# button-wall.net
KiCad netlist of a schematic drawn in EAGLE
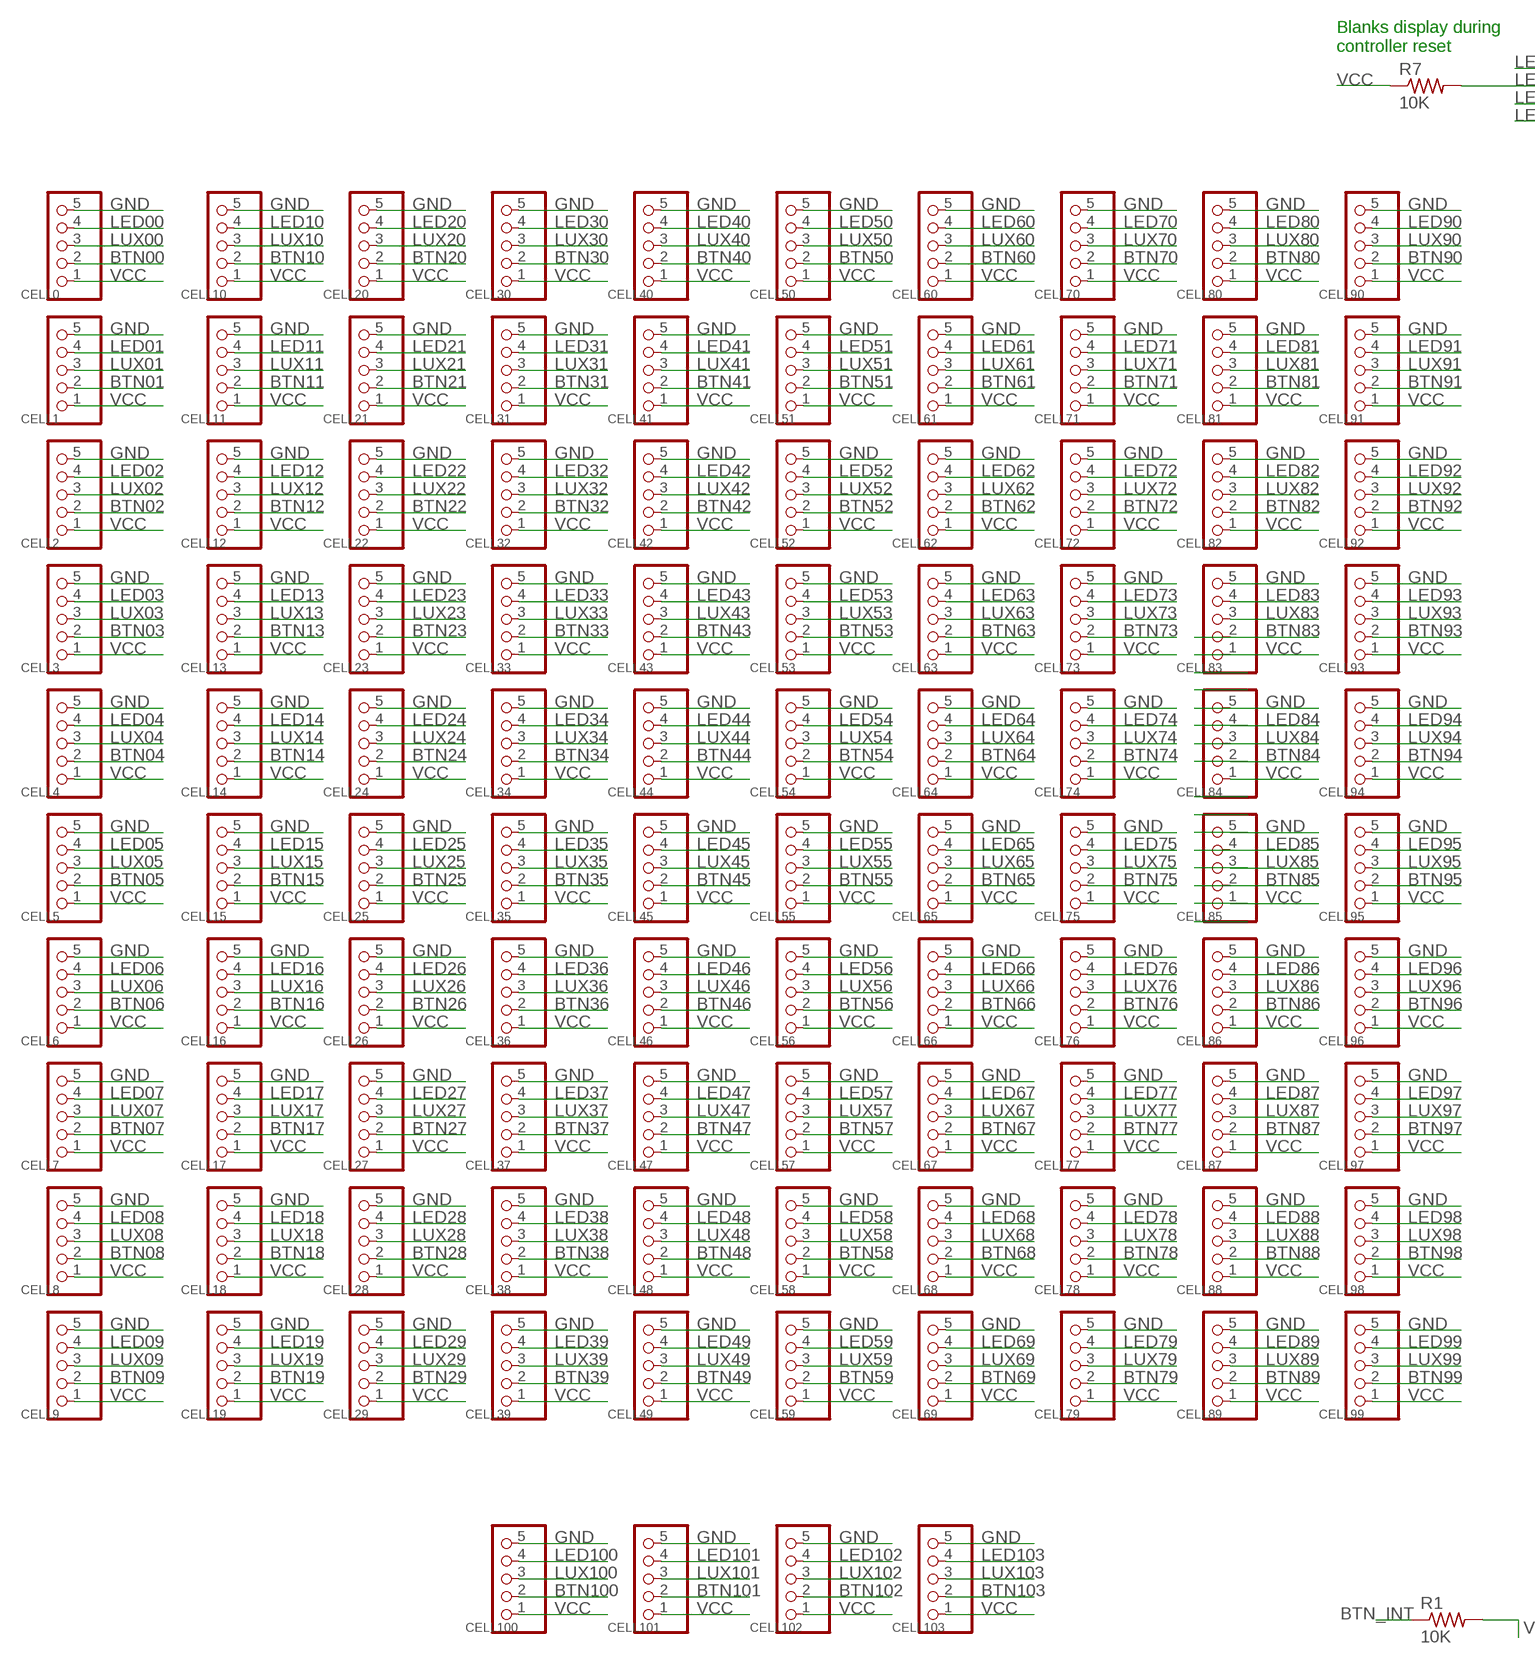
[diagram p0: schematic, sheet 1, part 1 of 2]
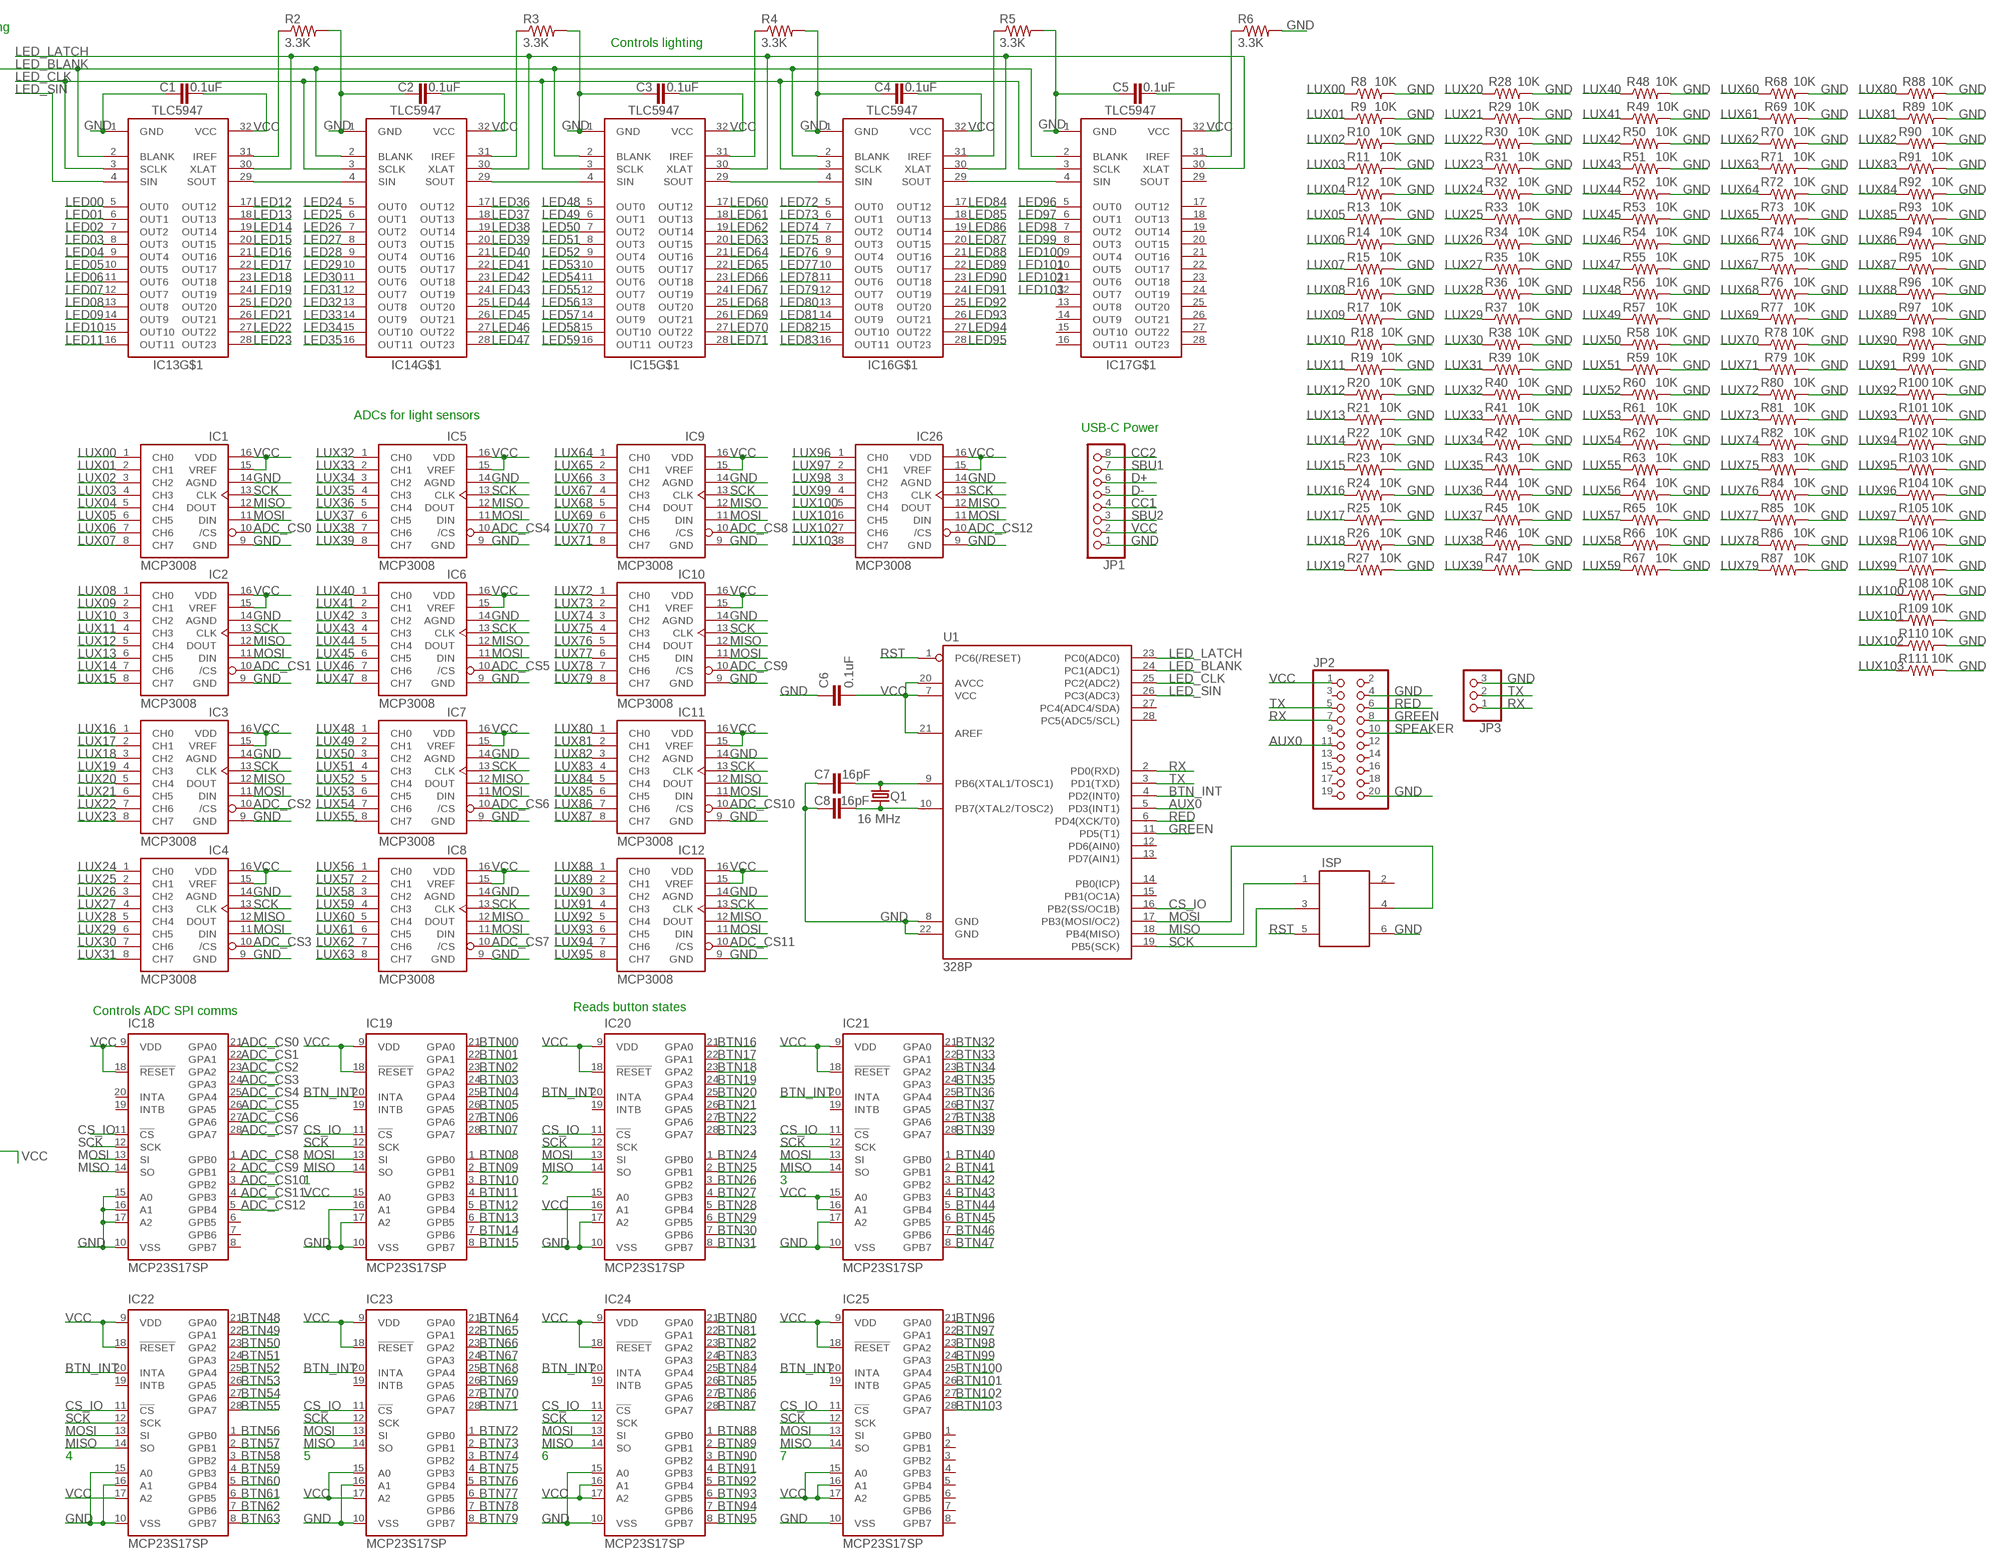
[diagram p1: schematic, sheet 1, part 2 of 2]

(export (version "E")
  (design (tool "Eeschema 10.0.6"))
  (components
    (comp (ref "C1")
      (value "0.1uF")
      (footprint "eagle-import:C1206")
      (libsource (lib "eagle-import") (part "C-EUC1206"))
    )
    (comp (ref "C2")
      (value "0.1uF")
      (footprint "eagle-import:C1206")
      (libsource (lib "eagle-import") (part "C-EUC1206"))
    )
    (comp (ref "C3")
      (value "0.1uF")
      (footprint "eagle-import:C1206")
      (libsource (lib "eagle-import") (part "C-EUC1206"))
    )
    (comp (ref "C4")
      (value "0.1uF")
      (footprint "eagle-import:C1206")
      (libsource (lib "eagle-import") (part "C-EUC1206"))
    )
    (comp (ref "C5")
      (value "0.1uF")
      (footprint "eagle-import:C1206")
      (libsource (lib "eagle-import") (part "C-EUC1206"))
    )
    (comp (ref "C6")
      (value "0.1uF")
      (footprint "eagle-import:C1206")
      (libsource (lib "eagle-import") (part "C-EUC1206"))
    )
    (comp (ref "C7")
      (value "16pF")
      (footprint "eagle-import:C0805")
      (libsource (lib "eagle-import") (part "C-EUC0805"))
    )
    (comp (ref "C8")
      (value "16pF")
      (footprint "eagle-import:C0805")
      (libsource (lib "eagle-import") (part "C-EUC0805"))
    )
    (comp (ref "CELL0")
      (value "PINHD-1X55X2MM")
      (footprint "eagle-import:1_05X2MM")
      (libsource (lib "eagle-import") (part "PINHD-1X55X2MM"))
    )
    (comp (ref "CELL1")
      (value "PINHD-1X55X2MM")
      (footprint "eagle-import:1_05X2MM")
      (libsource (lib "eagle-import") (part "PINHD-1X55X2MM"))
    )
    (comp (ref "CELL2")
      (value "PINHD-1X55X2MM")
      (footprint "eagle-import:1_05X2MM")
      (libsource (lib "eagle-import") (part "PINHD-1X55X2MM"))
    )
    (comp (ref "CELL3")
      (value "PINHD-1X55X2MM")
      (footprint "eagle-import:1_05X2MM")
      (libsource (lib "eagle-import") (part "PINHD-1X55X2MM"))
    )
    (comp (ref "CELL4")
      (value "PINHD-1X55X2MM")
      (footprint "eagle-import:1_05X2MM")
      (libsource (lib "eagle-import") (part "PINHD-1X55X2MM"))
    )
    (comp (ref "CELL5")
      (value "PINHD-1X55X2MM")
      (footprint "eagle-import:1_05X2MM")
      (libsource (lib "eagle-import") (part "PINHD-1X55X2MM"))
    )
    (comp (ref "CELL6")
      (value "PINHD-1X55X2MM")
      (footprint "eagle-import:1_05X2MM")
      (libsource (lib "eagle-import") (part "PINHD-1X55X2MM"))
    )
    (comp (ref "CELL7")
      (value "PINHD-1X55X2MM")
      (footprint "eagle-import:1_05X2MM")
      (libsource (lib "eagle-import") (part "PINHD-1X55X2MM"))
    )
    (comp (ref "CELL8")
      (value "PINHD-1X55X2MM")
      (footprint "eagle-import:1_05X2MM")
      (libsource (lib "eagle-import") (part "PINHD-1X55X2MM"))
    )
    (comp (ref "CELL9")
      (value "PINHD-1X55X2MM")
      (footprint "eagle-import:1_05X2MM")
      (libsource (lib "eagle-import") (part "PINHD-1X55X2MM"))
    )
    (comp (ref "CELL10")
      (value "PINHD-1X55X2MM")
      (footprint "eagle-import:1_05X2MM")
      (libsource (lib "eagle-import") (part "PINHD-1X55X2MM"))
    )
    (comp (ref "CELL11")
      (value "PINHD-1X55X2MM")
      (footprint "eagle-import:1_05X2MM")
      (libsource (lib "eagle-import") (part "PINHD-1X55X2MM"))
    )
    (comp (ref "CELL12")
      (value "PINHD-1X55X2MM")
      (footprint "eagle-import:1_05X2MM")
      (libsource (lib "eagle-import") (part "PINHD-1X55X2MM"))
    )
    (comp (ref "CELL13")
      (value "PINHD-1X55X2MM")
      (footprint "eagle-import:1_05X2MM")
      (libsource (lib "eagle-import") (part "PINHD-1X55X2MM"))
    )
    (comp (ref "CELL14")
      (value "PINHD-1X55X2MM")
      (footprint "eagle-import:1_05X2MM")
      (libsource (lib "eagle-import") (part "PINHD-1X55X2MM"))
    )
    (comp (ref "CELL15")
      (value "PINHD-1X55X2MM")
      (footprint "eagle-import:1_05X2MM")
      (libsource (lib "eagle-import") (part "PINHD-1X55X2MM"))
    )
    (comp (ref "CELL16")
      (value "PINHD-1X55X2MM")
      (footprint "eagle-import:1_05X2MM")
      (libsource (lib "eagle-import") (part "PINHD-1X55X2MM"))
    )
    (comp (ref "CELL17")
      (value "PINHD-1X55X2MM")
      (footprint "eagle-import:1_05X2MM")
      (libsource (lib "eagle-import") (part "PINHD-1X55X2MM"))
    )
    (comp (ref "CELL18")
      (value "PINHD-1X55X2MM")
      (footprint "eagle-import:1_05X2MM")
      (libsource (lib "eagle-import") (part "PINHD-1X55X2MM"))
    )
    (comp (ref "CELL19")
      (value "PINHD-1X55X2MM")
      (footprint "eagle-import:1_05X2MM")
      (libsource (lib "eagle-import") (part "PINHD-1X55X2MM"))
    )
    (comp (ref "CELL20")
      (value "PINHD-1X55X2MM")
      (footprint "eagle-import:1_05X2MM")
      (libsource (lib "eagle-import") (part "PINHD-1X55X2MM"))
    )
    (comp (ref "CELL21")
      (value "PINHD-1X55X2MM")
      (footprint "eagle-import:1_05X2MM")
      (libsource (lib "eagle-import") (part "PINHD-1X55X2MM"))
    )
    (comp (ref "CELL22")
      (value "PINHD-1X55X2MM")
      (footprint "eagle-import:1_05X2MM")
      (libsource (lib "eagle-import") (part "PINHD-1X55X2MM"))
    )
    (comp (ref "CELL23")
      (value "PINHD-1X55X2MM")
      (footprint "eagle-import:1_05X2MM")
      (libsource (lib "eagle-import") (part "PINHD-1X55X2MM"))
    )
    (comp (ref "CELL24")
      (value "PINHD-1X55X2MM")
      (footprint "eagle-import:1_05X2MM")
      (libsource (lib "eagle-import") (part "PINHD-1X55X2MM"))
    )
    (comp (ref "CELL25")
      (value "PINHD-1X55X2MM")
      (footprint "eagle-import:1_05X2MM")
      (libsource (lib "eagle-import") (part "PINHD-1X55X2MM"))
    )
    (comp (ref "CELL26")
      (value "PINHD-1X55X2MM")
      (footprint "eagle-import:1_05X2MM")
      (libsource (lib "eagle-import") (part "PINHD-1X55X2MM"))
    )
    (comp (ref "CELL27")
      (value "PINHD-1X55X2MM")
      (footprint "eagle-import:1_05X2MM")
      (libsource (lib "eagle-import") (part "PINHD-1X55X2MM"))
    )
    (comp (ref "CELL28")
      (value "PINHD-1X55X2MM")
      (footprint "eagle-import:1_05X2MM")
      (libsource (lib "eagle-import") (part "PINHD-1X55X2MM"))
    )
    (comp (ref "CELL29")
      (value "PINHD-1X55X2MM")
      (footprint "eagle-import:1_05X2MM")
      (libsource (lib "eagle-import") (part "PINHD-1X55X2MM"))
    )
    (comp (ref "CELL30")
      (value "PINHD-1X55X2MM")
      (footprint "eagle-import:1_05X2MM")
      (libsource (lib "eagle-import") (part "PINHD-1X55X2MM"))
    )
    (comp (ref "CELL31")
      (value "PINHD-1X55X2MM")
      (footprint "eagle-import:1_05X2MM")
      (libsource (lib "eagle-import") (part "PINHD-1X55X2MM"))
    )
    (comp (ref "CELL32")
      (value "PINHD-1X55X2MM")
      (footprint "eagle-import:1_05X2MM")
      (libsource (lib "eagle-import") (part "PINHD-1X55X2MM"))
    )
    (comp (ref "CELL33")
      (value "PINHD-1X55X2MM")
      (footprint "eagle-import:1_05X2MM")
      (libsource (lib "eagle-import") (part "PINHD-1X55X2MM"))
    )
    (comp (ref "CELL34")
      (value "PINHD-1X55X2MM")
      (footprint "eagle-import:1_05X2MM")
      (libsource (lib "eagle-import") (part "PINHD-1X55X2MM"))
    )
    (comp (ref "CELL35")
      (value "PINHD-1X55X2MM")
      (footprint "eagle-import:1_05X2MM")
      (libsource (lib "eagle-import") (part "PINHD-1X55X2MM"))
    )
    (comp (ref "CELL36")
      (value "PINHD-1X55X2MM")
      (footprint "eagle-import:1_05X2MM")
      (libsource (lib "eagle-import") (part "PINHD-1X55X2MM"))
    )
    (comp (ref "CELL37")
      (value "PINHD-1X55X2MM")
      (footprint "eagle-import:1_05X2MM")
      (libsource (lib "eagle-import") (part "PINHD-1X55X2MM"))
    )
    (comp (ref "CELL38")
      (value "PINHD-1X55X2MM")
      (footprint "eagle-import:1_05X2MM")
      (libsource (lib "eagle-import") (part "PINHD-1X55X2MM"))
    )
    (comp (ref "CELL39")
      (value "PINHD-1X55X2MM")
      (footprint "eagle-import:1_05X2MM")
      (libsource (lib "eagle-import") (part "PINHD-1X55X2MM"))
    )
    (comp (ref "CELL40")
      (value "PINHD-1X55X2MM")
      (footprint "eagle-import:1_05X2MM")
      (libsource (lib "eagle-import") (part "PINHD-1X55X2MM"))
    )
    (comp (ref "CELL41")
      (value "PINHD-1X55X2MM")
      (footprint "eagle-import:1_05X2MM")
      (libsource (lib "eagle-import") (part "PINHD-1X55X2MM"))
    )
    (comp (ref "CELL42")
      (value "PINHD-1X55X2MM")
      (footprint "eagle-import:1_05X2MM")
      (libsource (lib "eagle-import") (part "PINHD-1X55X2MM"))
    )
    (comp (ref "CELL43")
      (value "PINHD-1X55X2MM")
      (footprint "eagle-import:1_05X2MM")
      (libsource (lib "eagle-import") (part "PINHD-1X55X2MM"))
    )
    (comp (ref "CELL44")
      (value "PINHD-1X55X2MM")
      (footprint "eagle-import:1_05X2MM")
      (libsource (lib "eagle-import") (part "PINHD-1X55X2MM"))
    )
    (comp (ref "CELL45")
      (value "PINHD-1X55X2MM")
      (footprint "eagle-import:1_05X2MM")
      (libsource (lib "eagle-import") (part "PINHD-1X55X2MM"))
    )
    (comp (ref "CELL46")
      (value "PINHD-1X55X2MM")
      (footprint "eagle-import:1_05X2MM")
      (libsource (lib "eagle-import") (part "PINHD-1X55X2MM"))
    )
    (comp (ref "CELL47")
      (value "PINHD-1X55X2MM")
      (footprint "eagle-import:1_05X2MM")
      (libsource (lib "eagle-import") (part "PINHD-1X55X2MM"))
    )
    (comp (ref "CELL48")
      (value "PINHD-1X55X2MM")
      (footprint "eagle-import:1_05X2MM")
      (libsource (lib "eagle-import") (part "PINHD-1X55X2MM"))
    )
    (comp (ref "CELL49")
      (value "PINHD-1X55X2MM")
      (footprint "eagle-import:1_05X2MM")
      (libsource (lib "eagle-import") (part "PINHD-1X55X2MM"))
    )
    (comp (ref "CELL50")
      (value "PINHD-1X55X2MM")
      (footprint "eagle-import:1_05X2MM")
      (libsource (lib "eagle-import") (part "PINHD-1X55X2MM"))
    )
    (comp (ref "CELL51")
      (value "PINHD-1X55X2MM")
      (footprint "eagle-import:1_05X2MM")
      (libsource (lib "eagle-import") (part "PINHD-1X55X2MM"))
    )
    (comp (ref "CELL52")
      (value "PINHD-1X55X2MM")
      (footprint "eagle-import:1_05X2MM")
      (libsource (lib "eagle-import") (part "PINHD-1X55X2MM"))
    )
    (comp (ref "CELL53")
      (value "PINHD-1X55X2MM")
      (footprint "eagle-import:1_05X2MM")
      (libsource (lib "eagle-import") (part "PINHD-1X55X2MM"))
    )
    (comp (ref "CELL54")
      (value "PINHD-1X55X2MM")
      (footprint "eagle-import:1_05X2MM")
      (libsource (lib "eagle-import") (part "PINHD-1X55X2MM"))
    )
    (comp (ref "CELL55")
      (value "PINHD-1X55X2MM")
      (footprint "eagle-import:1_05X2MM")
      (libsource (lib "eagle-import") (part "PINHD-1X55X2MM"))
    )
    (comp (ref "CELL56")
      (value "PINHD-1X55X2MM")
      (footprint "eagle-import:1_05X2MM")
      (libsource (lib "eagle-import") (part "PINHD-1X55X2MM"))
    )
    (comp (ref "CELL57")
      (value "PINHD-1X55X2MM")
      (footprint "eagle-import:1_05X2MM")
      (libsource (lib "eagle-import") (part "PINHD-1X55X2MM"))
    )
    (comp (ref "CELL58")
      (value "PINHD-1X55X2MM")
      (footprint "eagle-import:1_05X2MM")
      (libsource (lib "eagle-import") (part "PINHD-1X55X2MM"))
    )
    (comp (ref "CELL59")
      (value "PINHD-1X55X2MM")
      (footprint "eagle-import:1_05X2MM")
      (libsource (lib "eagle-import") (part "PINHD-1X55X2MM"))
    )
    (comp (ref "CELL60")
      (value "PINHD-1X55X2MM")
      (footprint "eagle-import:1_05X2MM")
      (libsource (lib "eagle-import") (part "PINHD-1X55X2MM"))
    )
    (comp (ref "CELL61")
      (value "PINHD-1X55X2MM")
      (footprint "eagle-import:1_05X2MM")
      (libsource (lib "eagle-import") (part "PINHD-1X55X2MM"))
    )
    (comp (ref "CELL62")
      (value "PINHD-1X55X2MM")
      (footprint "eagle-import:1_05X2MM")
      (libsource (lib "eagle-import") (part "PINHD-1X55X2MM"))
    )
    (comp (ref "CELL63")
      (value "PINHD-1X55X2MM")
      (footprint "eagle-import:1_05X2MM")
      (libsource (lib "eagle-import") (part "PINHD-1X55X2MM"))
    )
    (comp (ref "CELL64")
      (value "PINHD-1X55X2MM")
      (footprint "eagle-import:1_05X2MM")
      (libsource (lib "eagle-import") (part "PINHD-1X55X2MM"))
    )
    (comp (ref "CELL65")
      (value "PINHD-1X55X2MM")
      (footprint "eagle-import:1_05X2MM")
      (libsource (lib "eagle-import") (part "PINHD-1X55X2MM"))
    )
    (comp (ref "CELL66")
      (value "PINHD-1X55X2MM")
      (footprint "eagle-import:1_05X2MM")
      (libsource (lib "eagle-import") (part "PINHD-1X55X2MM"))
    )
    (comp (ref "CELL67")
      (value "PINHD-1X55X2MM")
      (footprint "eagle-import:1_05X2MM")
      (libsource (lib "eagle-import") (part "PINHD-1X55X2MM"))
    )
    (comp (ref "CELL68")
      (value "PINHD-1X55X2MM")
      (footprint "eagle-import:1_05X2MM")
      (libsource (lib "eagle-import") (part "PINHD-1X55X2MM"))
    )
    (comp (ref "CELL69")
      (value "PINHD-1X55X2MM")
      (footprint "eagle-import:1_05X2MM")
      (libsource (lib "eagle-import") (part "PINHD-1X55X2MM"))
    )
    (comp (ref "CELL70")
      (value "PINHD-1X55X2MM")
      (footprint "eagle-import:1_05X2MM")
      (libsource (lib "eagle-import") (part "PINHD-1X55X2MM"))
    )
    (comp (ref "CELL71")
      (value "PINHD-1X55X2MM")
      (footprint "eagle-import:1_05X2MM")
      (libsource (lib "eagle-import") (part "PINHD-1X55X2MM"))
    )
    (comp (ref "CELL72")
      (value "PINHD-1X55X2MM")
      (footprint "eagle-import:1_05X2MM")
      (libsource (lib "eagle-import") (part "PINHD-1X55X2MM"))
    )
    (comp (ref "CELL73")
      (value "PINHD-1X55X2MM")
      (footprint "eagle-import:1_05X2MM")
      (libsource (lib "eagle-import") (part "PINHD-1X55X2MM"))
    )
    (comp (ref "CELL74")
      (value "PINHD-1X55X2MM")
      (footprint "eagle-import:1_05X2MM")
      (libsource (lib "eagle-import") (part "PINHD-1X55X2MM"))
    )
    (comp (ref "CELL75")
      (value "PINHD-1X55X2MM")
      (footprint "eagle-import:1_05X2MM")
      (libsource (lib "eagle-import") (part "PINHD-1X55X2MM"))
    )
    (comp (ref "CELL76")
      (value "PINHD-1X55X2MM")
      (footprint "eagle-import:1_05X2MM")
      (libsource (lib "eagle-import") (part "PINHD-1X55X2MM"))
    )
    (comp (ref "CELL77")
      (value "PINHD-1X55X2MM")
      (footprint "eagle-import:1_05X2MM")
      (libsource (lib "eagle-import") (part "PINHD-1X55X2MM"))
    )
    (comp (ref "CELL78")
      (value "PINHD-1X55X2MM")
      (footprint "eagle-import:1_05X2MM")
      (libsource (lib "eagle-import") (part "PINHD-1X55X2MM"))
    )
    (comp (ref "CELL79")
      (value "PINHD-1X55X2MM")
      (footprint "eagle-import:1_05X2MM")
      (libsource (lib "eagle-import") (part "PINHD-1X55X2MM"))
    )
    (comp (ref "CELL80")
      (value "PINHD-1X55X2MM")
      (footprint "eagle-import:1_05X2MM")
      (libsource (lib "eagle-import") (part "PINHD-1X55X2MM"))
    )
    (comp (ref "CELL81")
      (value "PINHD-1X55X2MM")
      (footprint "eagle-import:1_05X2MM")
      (libsource (lib "eagle-import") (part "PINHD-1X55X2MM"))
    )
    (comp (ref "CELL82")
      (value "PINHD-1X55X2MM")
      (footprint "eagle-import:1_05X2MM")
      (libsource (lib "eagle-import") (part "PINHD-1X55X2MM"))
    )
    (comp (ref "CELL83")
      (value "PINHD-1X55X2MM")
      (footprint "eagle-import:1_05X2MM")
      (libsource (lib "eagle-import") (part "PINHD-1X55X2MM"))
    )
    (comp (ref "CELL84")
      (value "PINHD-1X55X2MM")
      (footprint "eagle-import:1_05X2MM")
      (libsource (lib "eagle-import") (part "PINHD-1X55X2MM"))
    )
    (comp (ref "CELL85")
      (value "PINHD-1X55X2MM")
      (footprint "eagle-import:1_05X2MM")
      (libsource (lib "eagle-import") (part "PINHD-1X55X2MM"))
    )
    (comp (ref "CELL86")
      (value "PINHD-1X55X2MM")
      (footprint "eagle-import:1_05X2MM")
      (libsource (lib "eagle-import") (part "PINHD-1X55X2MM"))
    )
    (comp (ref "CELL87")
      (value "PINHD-1X55X2MM")
      (footprint "eagle-import:1_05X2MM")
      (libsource (lib "eagle-import") (part "PINHD-1X55X2MM"))
    )
    (comp (ref "CELL88")
      (value "PINHD-1X55X2MM")
      (footprint "eagle-import:1_05X2MM")
      (libsource (lib "eagle-import") (part "PINHD-1X55X2MM"))
    )
    (comp (ref "CELL89")
      (value "PINHD-1X55X2MM")
      (footprint "eagle-import:1_05X2MM")
      (libsource (lib "eagle-import") (part "PINHD-1X55X2MM"))
    )
    (comp (ref "CELL90")
      (value "PINHD-1X55X2MM")
      (footprint "eagle-import:1_05X2MM")
      (libsource (lib "eagle-import") (part "PINHD-1X55X2MM"))
    )
    (comp (ref "CELL91")
      (value "PINHD-1X55X2MM")
      (footprint "eagle-import:1_05X2MM")
      (libsource (lib "eagle-import") (part "PINHD-1X55X2MM"))
    )
    (comp (ref "CELL92")
      (value "PINHD-1X55X2MM")
      (footprint "eagle-import:1_05X2MM")
      (libsource (lib "eagle-import") (part "PINHD-1X55X2MM"))
    )
    (comp (ref "CELL93")
      (value "PINHD-1X55X2MM")
      (footprint "eagle-import:1_05X2MM")
      (libsource (lib "eagle-import") (part "PINHD-1X55X2MM"))
    )
    (comp (ref "CELL94")
      (value "PINHD-1X55X2MM")
      (footprint "eagle-import:1_05X2MM")
      (libsource (lib "eagle-import") (part "PINHD-1X55X2MM"))
    )
    (comp (ref "CELL95")
      (value "PINHD-1X55X2MM")
      (footprint "eagle-import:1_05X2MM")
      (libsource (lib "eagle-import") (part "PINHD-1X55X2MM"))
    )
    (comp (ref "CELL96")
      (value "PINHD-1X55X2MM")
      (footprint "eagle-import:1_05X2MM")
      (libsource (lib "eagle-import") (part "PINHD-1X55X2MM"))
    )
    (comp (ref "CELL97")
      (value "PINHD-1X55X2MM")
      (footprint "eagle-import:1_05X2MM")
      (libsource (lib "eagle-import") (part "PINHD-1X55X2MM"))
    )
    (comp (ref "CELL98")
      (value "PINHD-1X55X2MM")
      (footprint "eagle-import:1_05X2MM")
      (libsource (lib "eagle-import") (part "PINHD-1X55X2MM"))
    )
    (comp (ref "CELL99")
      (value "PINHD-1X55X2MM")
      (footprint "eagle-import:1_05X2MM")
      (libsource (lib "eagle-import") (part "PINHD-1X55X2MM"))
    )
    (comp (ref "CELL100")
      (value "PINHD-1X55X2MM")
      (footprint "eagle-import:1_05X2MM")
      (libsource (lib "eagle-import") (part "PINHD-1X55X2MM"))
    )
    (comp (ref "CELL101")
      (value "PINHD-1X55X2MM")
      (footprint "eagle-import:1_05X2MM")
      (libsource (lib "eagle-import") (part "PINHD-1X55X2MM"))
    )
    (comp (ref "CELL102")
      (value "PINHD-1X55X2MM")
      (footprint "eagle-import:1_05X2MM")
      (libsource (lib "eagle-import") (part "PINHD-1X55X2MM"))
    )
    (comp (ref "CELL103")
      (value "PINHD-1X55X2MM")
      (footprint "eagle-import:1_05X2MM")
      (libsource (lib "eagle-import") (part "PINHD-1X55X2MM"))
    )
    (comp (ref "IC1")
      (value "MCP3008")
      (footprint "eagle-import:DIL16")
      (libsource (lib "eagle-import") (part "MCP3008"))
    )
    (comp (ref "IC2")
      (value "MCP3008")
      (footprint "eagle-import:DIL16")
      (libsource (lib "eagle-import") (part "MCP3008"))
    )
    (comp (ref "IC3")
      (value "MCP3008")
      (footprint "eagle-import:DIL16")
      (libsource (lib "eagle-import") (part "MCP3008"))
    )
    (comp (ref "IC4")
      (value "MCP3008")
      (footprint "eagle-import:DIL16")
      (libsource (lib "eagle-import") (part "MCP3008"))
    )
    (comp (ref "IC5")
      (value "MCP3008")
      (footprint "eagle-import:DIL16")
      (libsource (lib "eagle-import") (part "MCP3008"))
    )
    (comp (ref "IC6")
      (value "MCP3008")
      (footprint "eagle-import:DIL16")
      (libsource (lib "eagle-import") (part "MCP3008"))
    )
    (comp (ref "IC7")
      (value "MCP3008")
      (footprint "eagle-import:DIL16")
      (libsource (lib "eagle-import") (part "MCP3008"))
    )
    (comp (ref "IC8")
      (value "MCP3008")
      (footprint "eagle-import:DIL16")
      (libsource (lib "eagle-import") (part "MCP3008"))
    )
    (comp (ref "IC9")
      (value "MCP3008")
      (footprint "eagle-import:DIL16")
      (libsource (lib "eagle-import") (part "MCP3008"))
    )
    (comp (ref "IC10")
      (value "MCP3008")
      (footprint "eagle-import:DIL16")
      (libsource (lib "eagle-import") (part "MCP3008"))
    )
    (comp (ref "IC11")
      (value "MCP3008")
      (footprint "eagle-import:DIL16")
      (libsource (lib "eagle-import") (part "MCP3008"))
    )
    (comp (ref "IC12")
      (value "MCP3008")
      (footprint "eagle-import:DIL16")
      (libsource (lib "eagle-import") (part "MCP3008"))
    )
    (comp (ref "IC13")
      (value "TLC5947-DAP")
      (footprint "eagle-import:HTSSOP32DAP")
      (libsource (lib "eagle-import") (part "TLC5947-DAP"))
    )
    (comp (ref "IC14")
      (value "TLC5947-DAP")
      (footprint "eagle-import:HTSSOP32DAP")
      (libsource (lib "eagle-import") (part "TLC5947-DAP"))
    )
    (comp (ref "IC15")
      (value "TLC5947-DAP")
      (footprint "eagle-import:HTSSOP32DAP")
      (libsource (lib "eagle-import") (part "TLC5947-DAP"))
    )
    (comp (ref "IC16")
      (value "TLC5947-DAP")
      (footprint "eagle-import:HTSSOP32DAP")
      (libsource (lib "eagle-import") (part "TLC5947-DAP"))
    )
    (comp (ref "IC17")
      (value "TLC5947-DAP")
      (footprint "eagle-import:HTSSOP32DAP")
      (libsource (lib "eagle-import") (part "TLC5947-DAP"))
    )
    (comp (ref "IC18")
      (value "MCP23S17SP")
      (footprint "eagle-import:DIL28-3")
      (fields (field (name "MF") "MICROCHIP") (field (name "MPN") "MCP23S17-E/SP"))
      (libsource (lib "eagle-import") (part "MCP23S17SP"))
    )
    (comp (ref "IC19")
      (value "MCP23S17SP")
      (footprint "eagle-import:DIL28-3")
      (fields (field (name "MF") "MICROCHIP") (field (name "MPN") "MCP23S17-E/SP"))
      (libsource (lib "eagle-import") (part "MCP23S17SP"))
    )
    (comp (ref "IC20")
      (value "MCP23S17SP")
      (footprint "eagle-import:DIL28-3")
      (fields (field (name "MF") "MICROCHIP") (field (name "MPN") "MCP23S17-E/SP"))
      (libsource (lib "eagle-import") (part "MCP23S17SP"))
    )
    (comp (ref "IC21")
      (value "MCP23S17SP")
      (footprint "eagle-import:DIL28-3")
      (fields (field (name "MF") "MICROCHIP") (field (name "MPN") "MCP23S17-E/SP"))
      (libsource (lib "eagle-import") (part "MCP23S17SP"))
    )
    (comp (ref "IC22")
      (value "MCP23S17SP")
      (footprint "eagle-import:DIL28-3")
      (fields (field (name "MF") "MICROCHIP") (field (name "MPN") "MCP23S17-E/SP"))
      (libsource (lib "eagle-import") (part "MCP23S17SP"))
    )
    (comp (ref "IC23")
      (value "MCP23S17SP")
      (footprint "eagle-import:DIL28-3")
      (fields (field (name "MF") "MICROCHIP") (field (name "MPN") "MCP23S17-E/SP"))
      (libsource (lib "eagle-import") (part "MCP23S17SP"))
    )
    (comp (ref "IC24")
      (value "MCP23S17SP")
      (footprint "eagle-import:DIL28-3")
      (fields (field (name "MF") "MICROCHIP") (field (name "MPN") "MCP23S17-E/SP"))
      (libsource (lib "eagle-import") (part "MCP23S17SP"))
    )
    (comp (ref "IC25")
      (value "MCP23S17SP")
      (footprint "eagle-import:DIL28-3")
      (fields (field (name "MF") "MICROCHIP") (field (name "MPN") "MCP23S17-E/SP"))
      (libsource (lib "eagle-import") (part "MCP23S17SP"))
    )
    (comp (ref "IC26")
      (value "MCP3008")
      (footprint "eagle-import:DIL16")
      (libsource (lib "eagle-import") (part "MCP3008"))
    )
    (comp (ref "ISP")
      (value "61200621621")
      (footprint "eagle-import:61200621621")
      (libsource (lib "eagle-import") (part "61200621621"))
    )
    (comp (ref "JP1")
      (value "PINHD-1X8CLEANBIG")
      (footprint "eagle-import:1X08-CLEANBIG")
      (libsource (lib "eagle-import") (part "PINHD-1X8CLEANBIG"))
    )
    (comp (ref "JP2")
      (value "PINHD-2X10")
      (footprint "eagle-import:2X10")
      (libsource (lib "eagle-import") (part "PINHD-2X10"))
    )
    (comp (ref "JP3")
      (value "PINHD-1X3")
      (footprint "eagle-import:1X03")
      (libsource (lib "eagle-import") (part "PINHD-1X3"))
    )
    (comp (ref "Q1")
      (value "16 MHz")
      (footprint "eagle-import:HC49_S")
      (libsource (lib "eagle-import") (part "CRYSTALHC49S"))
    )
    (comp (ref "R1")
      (value "10K")
      (footprint "eagle-import:R1206")
      (libsource (lib "eagle-import") (part "R-US_R1206"))
    )
    (comp (ref "R2")
      (value "3.3K")
      (footprint "eagle-import:R1206")
      (libsource (lib "eagle-import") (part "R-US_R1206"))
    )
    (comp (ref "R3")
      (value "3.3K")
      (footprint "eagle-import:R1206")
      (libsource (lib "eagle-import") (part "R-US_R1206"))
    )
    (comp (ref "R4")
      (value "3.3K")
      (footprint "eagle-import:R1206")
      (libsource (lib "eagle-import") (part "R-US_R1206"))
    )
    (comp (ref "R5")
      (value "3.3K")
      (footprint "eagle-import:R1206")
      (libsource (lib "eagle-import") (part "R-US_R1206"))
    )
    (comp (ref "R6")
      (value "3.3K")
      (footprint "eagle-import:R1206")
      (libsource (lib "eagle-import") (part "R-US_R1206"))
    )
    (comp (ref "R7")
      (value "10K")
      (footprint "eagle-import:R1206")
      (libsource (lib "eagle-import") (part "R-US_R1206"))
    )
    (comp (ref "R8")
      (value "10K")
      (footprint "eagle-import:R0805")
      (libsource (lib "eagle-import") (part "R-US_R0805"))
    )
    (comp (ref "R9")
      (value "10K")
      (footprint "eagle-import:R0805")
      (libsource (lib "eagle-import") (part "R-US_R0805"))
    )
    (comp (ref "R10")
      (value "10K")
      (footprint "eagle-import:R0805")
      (libsource (lib "eagle-import") (part "R-US_R0805"))
    )
    (comp (ref "R11")
      (value "10K")
      (footprint "eagle-import:R0805")
      (libsource (lib "eagle-import") (part "R-US_R0805"))
    )
    (comp (ref "R12")
      (value "10K")
      (footprint "eagle-import:R0805")
      (libsource (lib "eagle-import") (part "R-US_R0805"))
    )
    (comp (ref "R13")
      (value "10K")
      (footprint "eagle-import:R0805")
      (libsource (lib "eagle-import") (part "R-US_R0805"))
    )
    (comp (ref "R14")
      (value "10K")
      (footprint "eagle-import:R0805")
      (libsource (lib "eagle-import") (part "R-US_R0805"))
    )
    (comp (ref "R15")
      (value "10K")
      (footprint "eagle-import:R0805")
      (libsource (lib "eagle-import") (part "R-US_R0805"))
    )
    (comp (ref "R16")
      (value "10K")
      (footprint "eagle-import:R0805")
      (libsource (lib "eagle-import") (part "R-US_R0805"))
    )
    (comp (ref "R17")
      (value "10K")
      (footprint "eagle-import:R0805")
      (libsource (lib "eagle-import") (part "R-US_R0805"))
    )
    (comp (ref "R18")
      (value "10K")
      (footprint "eagle-import:R0805")
      (libsource (lib "eagle-import") (part "R-US_R0805"))
    )
    (comp (ref "R19")
      (value "10K")
      (footprint "eagle-import:R0805")
      (libsource (lib "eagle-import") (part "R-US_R0805"))
    )
    (comp (ref "R20")
      (value "10K")
      (footprint "eagle-import:R0805")
      (libsource (lib "eagle-import") (part "R-US_R0805"))
    )
    (comp (ref "R21")
      (value "10K")
      (footprint "eagle-import:R0805")
      (libsource (lib "eagle-import") (part "R-US_R0805"))
    )
    (comp (ref "R22")
      (value "10K")
      (footprint "eagle-import:R0805")
      (libsource (lib "eagle-import") (part "R-US_R0805"))
    )
    (comp (ref "R23")
      (value "10K")
      (footprint "eagle-import:R0805")
      (libsource (lib "eagle-import") (part "R-US_R0805"))
    )
    (comp (ref "R24")
      (value "10K")
      (footprint "eagle-import:R0805")
      (libsource (lib "eagle-import") (part "R-US_R0805"))
    )
    (comp (ref "R25")
      (value "10K")
      (footprint "eagle-import:R0805")
      (libsource (lib "eagle-import") (part "R-US_R0805"))
    )
    (comp (ref "R26")
      (value "10K")
      (footprint "eagle-import:R0805")
      (libsource (lib "eagle-import") (part "R-US_R0805"))
    )
    (comp (ref "R27")
      (value "10K")
      (footprint "eagle-import:R0805")
      (libsource (lib "eagle-import") (part "R-US_R0805"))
    )
    (comp (ref "R28")
      (value "10K")
      (footprint "eagle-import:R0805")
      (libsource (lib "eagle-import") (part "R-US_R0805"))
    )
    (comp (ref "R29")
      (value "10K")
      (footprint "eagle-import:R0805")
      (libsource (lib "eagle-import") (part "R-US_R0805"))
    )
    (comp (ref "R30")
      (value "10K")
      (footprint "eagle-import:R0805")
      (libsource (lib "eagle-import") (part "R-US_R0805"))
    )
    (comp (ref "R31")
      (value "10K")
      (footprint "eagle-import:R0805")
      (libsource (lib "eagle-import") (part "R-US_R0805"))
    )
    (comp (ref "R32")
      (value "10K")
      (footprint "eagle-import:R0805")
      (libsource (lib "eagle-import") (part "R-US_R0805"))
    )
    (comp (ref "R33")
      (value "10K")
      (footprint "eagle-import:R0805")
      (libsource (lib "eagle-import") (part "R-US_R0805"))
    )
    (comp (ref "R34")
      (value "10K")
      (footprint "eagle-import:R0805")
      (libsource (lib "eagle-import") (part "R-US_R0805"))
    )
    (comp (ref "R35")
      (value "10K")
      (footprint "eagle-import:R0805")
      (libsource (lib "eagle-import") (part "R-US_R0805"))
    )
    (comp (ref "R36")
      (value "10K")
      (footprint "eagle-import:R0805")
      (libsource (lib "eagle-import") (part "R-US_R0805"))
    )
    (comp (ref "R37")
      (value "10K")
      (footprint "eagle-import:R0805")
      (libsource (lib "eagle-import") (part "R-US_R0805"))
    )
    (comp (ref "R38")
      (value "10K")
      (footprint "eagle-import:R0805")
      (libsource (lib "eagle-import") (part "R-US_R0805"))
    )
    (comp (ref "R39")
      (value "10K")
      (footprint "eagle-import:R0805")
      (libsource (lib "eagle-import") (part "R-US_R0805"))
    )
    (comp (ref "R40")
      (value "10K")
      (footprint "eagle-import:R0805")
      (libsource (lib "eagle-import") (part "R-US_R0805"))
    )
    (comp (ref "R41")
      (value "10K")
      (footprint "eagle-import:R0805")
      (libsource (lib "eagle-import") (part "R-US_R0805"))
    )
    (comp (ref "R42")
      (value "10K")
      (footprint "eagle-import:R0805")
      (libsource (lib "eagle-import") (part "R-US_R0805"))
    )
    (comp (ref "R43")
      (value "10K")
      (footprint "eagle-import:R0805")
      (libsource (lib "eagle-import") (part "R-US_R0805"))
    )
    (comp (ref "R44")
      (value "10K")
      (footprint "eagle-import:R0805")
      (libsource (lib "eagle-import") (part "R-US_R0805"))
    )
    (comp (ref "R45")
      (value "10K")
      (footprint "eagle-import:R0805")
      (libsource (lib "eagle-import") (part "R-US_R0805"))
    )
    (comp (ref "R46")
      (value "10K")
      (footprint "eagle-import:R0805")
      (libsource (lib "eagle-import") (part "R-US_R0805"))
    )
    (comp (ref "R47")
      (value "10K")
      (footprint "eagle-import:R0805")
      (libsource (lib "eagle-import") (part "R-US_R0805"))
    )
    (comp (ref "R48")
      (value "10K")
      (footprint "eagle-import:R0805")
      (libsource (lib "eagle-import") (part "R-US_R0805"))
    )
    (comp (ref "R49")
      (value "10K")
      (footprint "eagle-import:R0805")
      (libsource (lib "eagle-import") (part "R-US_R0805"))
    )
    (comp (ref "R50")
      (value "10K")
      (footprint "eagle-import:R0805")
      (libsource (lib "eagle-import") (part "R-US_R0805"))
    )
    (comp (ref "R51")
      (value "10K")
      (footprint "eagle-import:R0805")
      (libsource (lib "eagle-import") (part "R-US_R0805"))
    )
    (comp (ref "R52")
      (value "10K")
      (footprint "eagle-import:R0805")
      (libsource (lib "eagle-import") (part "R-US_R0805"))
    )
    (comp (ref "R53")
      (value "10K")
      (footprint "eagle-import:R0805")
      (libsource (lib "eagle-import") (part "R-US_R0805"))
    )
    (comp (ref "R54")
      (value "10K")
      (footprint "eagle-import:R0805")
      (libsource (lib "eagle-import") (part "R-US_R0805"))
    )
    (comp (ref "R55")
      (value "10K")
      (footprint "eagle-import:R0805")
      (libsource (lib "eagle-import") (part "R-US_R0805"))
    )
    (comp (ref "R56")
      (value "10K")
      (footprint "eagle-import:R0805")
      (libsource (lib "eagle-import") (part "R-US_R0805"))
    )
    (comp (ref "R57")
      (value "10K")
      (footprint "eagle-import:R0805")
      (libsource (lib "eagle-import") (part "R-US_R0805"))
    )
    (comp (ref "R58")
      (value "10K")
      (footprint "eagle-import:R0805")
      (libsource (lib "eagle-import") (part "R-US_R0805"))
    )
    (comp (ref "R59")
      (value "10K")
      (footprint "eagle-import:R0805")
      (libsource (lib "eagle-import") (part "R-US_R0805"))
    )
    (comp (ref "R60")
      (value "10K")
      (footprint "eagle-import:R0805")
      (libsource (lib "eagle-import") (part "R-US_R0805"))
    )
    (comp (ref "R61")
      (value "10K")
      (footprint "eagle-import:R0805")
      (libsource (lib "eagle-import") (part "R-US_R0805"))
    )
    (comp (ref "R62")
      (value "10K")
      (footprint "eagle-import:R0805")
      (libsource (lib "eagle-import") (part "R-US_R0805"))
    )
    (comp (ref "R63")
      (value "10K")
      (footprint "eagle-import:R0805")
      (libsource (lib "eagle-import") (part "R-US_R0805"))
    )
    (comp (ref "R64")
      (value "10K")
      (footprint "eagle-import:R0805")
      (libsource (lib "eagle-import") (part "R-US_R0805"))
    )
    (comp (ref "R65")
      (value "10K")
      (footprint "eagle-import:R0805")
      (libsource (lib "eagle-import") (part "R-US_R0805"))
    )
    (comp (ref "R66")
      (value "10K")
      (footprint "eagle-import:R0805")
      (libsource (lib "eagle-import") (part "R-US_R0805"))
    )
    (comp (ref "R67")
      (value "10K")
      (footprint "eagle-import:R0805")
      (libsource (lib "eagle-import") (part "R-US_R0805"))
    )
    (comp (ref "R68")
      (value "10K")
      (footprint "eagle-import:R0805")
      (libsource (lib "eagle-import") (part "R-US_R0805"))
    )
    (comp (ref "R69")
      (value "10K")
      (footprint "eagle-import:R0805")
      (libsource (lib "eagle-import") (part "R-US_R0805"))
    )
    (comp (ref "R70")
      (value "10K")
      (footprint "eagle-import:R0805")
      (libsource (lib "eagle-import") (part "R-US_R0805"))
    )
    (comp (ref "R71")
      (value "10K")
      (footprint "eagle-import:R0805")
      (libsource (lib "eagle-import") (part "R-US_R0805"))
    )
    (comp (ref "R72")
      (value "10K")
      (footprint "eagle-import:R0805")
      (libsource (lib "eagle-import") (part "R-US_R0805"))
    )
    (comp (ref "R73")
      (value "10K")
      (footprint "eagle-import:R0805")
      (libsource (lib "eagle-import") (part "R-US_R0805"))
    )
    (comp (ref "R74")
      (value "10K")
      (footprint "eagle-import:R0805")
      (libsource (lib "eagle-import") (part "R-US_R0805"))
    )
    (comp (ref "R75")
      (value "10K")
      (footprint "eagle-import:R0805")
      (libsource (lib "eagle-import") (part "R-US_R0805"))
    )
    (comp (ref "R76")
      (value "10K")
      (footprint "eagle-import:R0805")
      (libsource (lib "eagle-import") (part "R-US_R0805"))
    )
    (comp (ref "R77")
      (value "10K")
      (footprint "eagle-import:R0805")
      (libsource (lib "eagle-import") (part "R-US_R0805"))
    )
    (comp (ref "R78")
      (value "10K")
      (footprint "eagle-import:R0805")
      (libsource (lib "eagle-import") (part "R-US_R0805"))
    )
    (comp (ref "R79")
      (value "10K")
      (footprint "eagle-import:R0805")
      (libsource (lib "eagle-import") (part "R-US_R0805"))
    )
    (comp (ref "R80")
      (value "10K")
      (footprint "eagle-import:R0805")
      (libsource (lib "eagle-import") (part "R-US_R0805"))
    )
    (comp (ref "R81")
      (value "10K")
      (footprint "eagle-import:R0805")
      (libsource (lib "eagle-import") (part "R-US_R0805"))
    )
    (comp (ref "R82")
      (value "10K")
      (footprint "eagle-import:R0805")
      (libsource (lib "eagle-import") (part "R-US_R0805"))
    )
    (comp (ref "R83")
      (value "10K")
      (footprint "eagle-import:R0805")
      (libsource (lib "eagle-import") (part "R-US_R0805"))
    )
    (comp (ref "R84")
      (value "10K")
      (footprint "eagle-import:R0805")
      (libsource (lib "eagle-import") (part "R-US_R0805"))
    )
    (comp (ref "R85")
      (value "10K")
      (footprint "eagle-import:R0805")
      (libsource (lib "eagle-import") (part "R-US_R0805"))
    )
    (comp (ref "R86")
      (value "10K")
      (footprint "eagle-import:R0805")
      (libsource (lib "eagle-import") (part "R-US_R0805"))
    )
    (comp (ref "R87")
      (value "10K")
      (footprint "eagle-import:R0805")
      (libsource (lib "eagle-import") (part "R-US_R0805"))
    )
    (comp (ref "R88")
      (value "10K")
      (footprint "eagle-import:R0805")
      (libsource (lib "eagle-import") (part "R-US_R0805"))
    )
    (comp (ref "R89")
      (value "10K")
      (footprint "eagle-import:R0805")
      (libsource (lib "eagle-import") (part "R-US_R0805"))
    )
    (comp (ref "R90")
      (value "10K")
      (footprint "eagle-import:R0805")
      (libsource (lib "eagle-import") (part "R-US_R0805"))
    )
    (comp (ref "R91")
      (value "10K")
      (footprint "eagle-import:R0805")
      (libsource (lib "eagle-import") (part "R-US_R0805"))
    )
    (comp (ref "R92")
      (value "10K")
      (footprint "eagle-import:R0805")
      (libsource (lib "eagle-import") (part "R-US_R0805"))
    )
    (comp (ref "R93")
      (value "10K")
      (footprint "eagle-import:R0805")
      (libsource (lib "eagle-import") (part "R-US_R0805"))
    )
    (comp (ref "R94")
      (value "10K")
      (footprint "eagle-import:R0805")
      (libsource (lib "eagle-import") (part "R-US_R0805"))
    )
    (comp (ref "R95")
      (value "10K")
      (footprint "eagle-import:R0805")
      (libsource (lib "eagle-import") (part "R-US_R0805"))
    )
    (comp (ref "R96")
      (value "10K")
      (footprint "eagle-import:R0805")
      (libsource (lib "eagle-import") (part "R-US_R0805"))
    )
    (comp (ref "R97")
      (value "10K")
      (footprint "eagle-import:R0805")
      (libsource (lib "eagle-import") (part "R-US_R0805"))
    )
    (comp (ref "R98")
      (value "10K")
      (footprint "eagle-import:R0805")
      (libsource (lib "eagle-import") (part "R-US_R0805"))
    )
    (comp (ref "R99")
      (value "10K")
      (footprint "eagle-import:R0805")
      (libsource (lib "eagle-import") (part "R-US_R0805"))
    )
    (comp (ref "R100")
      (value "10K")
      (footprint "eagle-import:R0805")
      (libsource (lib "eagle-import") (part "R-US_R0805"))
    )
    (comp (ref "R101")
      (value "10K")
      (footprint "eagle-import:R0805")
      (libsource (lib "eagle-import") (part "R-US_R0805"))
    )
    (comp (ref "R102")
      (value "10K")
      (footprint "eagle-import:R0805")
      (libsource (lib "eagle-import") (part "R-US_R0805"))
    )
    (comp (ref "R103")
      (value "10K")
      (footprint "eagle-import:R0805")
      (libsource (lib "eagle-import") (part "R-US_R0805"))
    )
    (comp (ref "R104")
      (value "10K")
      (footprint "eagle-import:R0805")
      (libsource (lib "eagle-import") (part "R-US_R0805"))
    )
    (comp (ref "R105")
      (value "10K")
      (footprint "eagle-import:R0805")
      (libsource (lib "eagle-import") (part "R-US_R0805"))
    )
    (comp (ref "R106")
      (value "10K")
      (footprint "eagle-import:R0805")
      (libsource (lib "eagle-import") (part "R-US_R0805"))
    )
    (comp (ref "R107")
      (value "10K")
      (footprint "eagle-import:R0805")
      (libsource (lib "eagle-import") (part "R-US_R0805"))
    )
    (comp (ref "R108")
      (value "10K")
      (footprint "eagle-import:R0805")
      (libsource (lib "eagle-import") (part "R-US_R0805"))
    )
    (comp (ref "R109")
      (value "10K")
      (footprint "eagle-import:R0805")
      (libsource (lib "eagle-import") (part "R-US_R0805"))
    )
    (comp (ref "R110")
      (value "10K")
      (footprint "eagle-import:R0805")
      (libsource (lib "eagle-import") (part "R-US_R0805"))
    )
    (comp (ref "R111")
      (value "10K")
      (footprint "eagle-import:R0805")
      (libsource (lib "eagle-import") (part "R-US_R0805"))
    )
    (comp (ref "U1")
      (value "328P")
      (footprint "eagle-import:DIP28")
      (libsource (lib "eagle-import") (part "ATMEGA328P_PDIP"))
    )
  )
  (nets
    (net (code "1") (name "/ADC_CS0") (class "Default")
      (node (ref "IC1") (pin "10") (pinfunction "/CS_10") (pintype "input"))
      (node (ref "IC18") (pin "21") (pinfunction "GPA0_21") (pintype "bidirectional"))
    )
    (net (code "2") (name "/ADC_CS1") (class "Default")
      (node (ref "IC18") (pin "22") (pinfunction "GPA1_22") (pintype "bidirectional"))
      (node (ref "IC2") (pin "10") (pinfunction "/CS_10") (pintype "input"))
    )
    (net (code "3") (name "/ADC_CS2") (class "Default")
      (node (ref "IC18") (pin "23") (pinfunction "GPA2_23") (pintype "bidirectional"))
      (node (ref "IC3") (pin "10") (pinfunction "/CS_10") (pintype "input"))
    )
    (net (code "4") (name "/ADC_CS3") (class "Default")
      (node (ref "IC18") (pin "24") (pinfunction "GPA3_24") (pintype "bidirectional"))
      (node (ref "IC4") (pin "10") (pinfunction "/CS_10") (pintype "input"))
    )
    (net (code "5") (name "/ADC_CS4") (class "Default")
      (node (ref "IC18") (pin "25") (pinfunction "GPA4_25") (pintype "bidirectional"))
      (node (ref "IC5") (pin "10") (pinfunction "/CS_10") (pintype "input"))
    )
    (net (code "6") (name "/ADC_CS5") (class "Default")
      (node (ref "IC18") (pin "26") (pinfunction "GPA5_26") (pintype "bidirectional"))
      (node (ref "IC6") (pin "10") (pinfunction "/CS_10") (pintype "input"))
    )
    (net (code "7") (name "/ADC_CS6") (class "Default")
      (node (ref "IC18") (pin "27") (pinfunction "GPA6_27") (pintype "bidirectional"))
      (node (ref "IC7") (pin "10") (pinfunction "/CS_10") (pintype "input"))
    )
    (net (code "8") (name "/ADC_CS7") (class "Default")
      (node (ref "IC18") (pin "28") (pinfunction "GPA7_28") (pintype "bidirectional"))
      (node (ref "IC8") (pin "10") (pinfunction "/CS_10") (pintype "input"))
    )
    (net (code "9") (name "/ADC_CS8") (class "Default")
      (node (ref "IC18") (pin "1") (pinfunction "GPB0_1") (pintype "bidirectional"))
      (node (ref "IC9") (pin "10") (pinfunction "/CS_10") (pintype "input"))
    )
    (net (code "10") (name "/ADC_CS9") (class "Default")
      (node (ref "IC10") (pin "10") (pinfunction "/CS_10") (pintype "input"))
      (node (ref "IC18") (pin "2") (pinfunction "GPB1_2") (pintype "bidirectional"))
    )
    (net (code "11") (name "/ADC_CS10") (class "Default")
      (node (ref "IC11") (pin "10") (pinfunction "/CS_10") (pintype "input"))
      (node (ref "IC18") (pin "3") (pinfunction "GPB2_3") (pintype "bidirectional"))
    )
    (net (code "12") (name "/ADC_CS11") (class "Default")
      (node (ref "IC12") (pin "10") (pinfunction "/CS_10") (pintype "input"))
      (node (ref "IC18") (pin "4") (pinfunction "GPB3_4") (pintype "bidirectional"))
    )
    (net (code "13") (name "/ADC_CS12") (class "Default")
      (node (ref "IC18") (pin "5") (pinfunction "GPB4_5") (pintype "bidirectional"))
      (node (ref "IC26") (pin "10") (pinfunction "/CS_10") (pintype "input"))
    )
    (net (code "14") (name "/AUX0") (class "Default")
      (node (ref "JP2") (pin "11") (pinfunction "11_11") (pintype "passive"))
      (node (ref "U1") (pin "5") (pinfunction "PD3(INT1)_5") (pintype "bidirectional"))
    )
    (net (code "15") (name "/BTN00") (class "Default")
      (node (ref "CELL0") (pin "2") (pinfunction "2_2") (pintype "passive"))
      (node (ref "IC19") (pin "21") (pinfunction "GPA0_21") (pintype "bidirectional"))
    )
    (net (code "16") (name "/BTN01") (class "Default")
      (node (ref "CELL1") (pin "2") (pinfunction "2_2") (pintype "passive"))
      (node (ref "IC19") (pin "22") (pinfunction "GPA1_22") (pintype "bidirectional"))
    )
    (net (code "17") (name "/BTN02") (class "Default")
      (node (ref "CELL2") (pin "2") (pinfunction "2_2") (pintype "passive"))
      (node (ref "IC19") (pin "23") (pinfunction "GPA2_23") (pintype "bidirectional"))
    )
    (net (code "18") (name "/BTN03") (class "Default")
      (node (ref "CELL3") (pin "2") (pinfunction "2_2") (pintype "passive"))
      (node (ref "IC19") (pin "24") (pinfunction "GPA3_24") (pintype "bidirectional"))
    )
    (net (code "19") (name "/BTN04") (class "Default")
      (node (ref "CELL4") (pin "2") (pinfunction "2_2") (pintype "passive"))
      (node (ref "IC19") (pin "25") (pinfunction "GPA4_25") (pintype "bidirectional"))
    )
    (net (code "20") (name "/BTN05") (class "Default")
      (node (ref "CELL5") (pin "2") (pinfunction "2_2") (pintype "passive"))
      (node (ref "IC19") (pin "26") (pinfunction "GPA5_26") (pintype "bidirectional"))
    )
    (net (code "21") (name "/BTN06") (class "Default")
      (node (ref "CELL6") (pin "2") (pinfunction "2_2") (pintype "passive"))
      (node (ref "IC19") (pin "27") (pinfunction "GPA6_27") (pintype "bidirectional"))
    )
    (net (code "22") (name "/BTN07") (class "Default")
      (node (ref "CELL7") (pin "2") (pinfunction "2_2") (pintype "passive"))
      (node (ref "IC19") (pin "28") (pinfunction "GPA7_28") (pintype "bidirectional"))
    )
    (net (code "23") (name "/BTN08") (class "Default")
      (node (ref "CELL8") (pin "2") (pinfunction "2_2") (pintype "passive"))
      (node (ref "IC19") (pin "1") (pinfunction "GPB0_1") (pintype "bidirectional"))
    )
    (net (code "24") (name "/BTN09") (class "Default")
      (node (ref "CELL9") (pin "2") (pinfunction "2_2") (pintype "passive"))
      (node (ref "IC19") (pin "2") (pinfunction "GPB1_2") (pintype "bidirectional"))
    )
    (net (code "25") (name "/BTN10") (class "Default")
      (node (ref "CELL10") (pin "2") (pinfunction "2_2") (pintype "passive"))
      (node (ref "IC19") (pin "3") (pinfunction "GPB2_3") (pintype "bidirectional"))
    )
    (net (code "26") (name "/BTN11") (class "Default")
      (node (ref "CELL11") (pin "2") (pinfunction "2_2") (pintype "passive"))
      (node (ref "IC19") (pin "4") (pinfunction "GPB3_4") (pintype "bidirectional"))
    )
    (net (code "27") (name "/BTN12") (class "Default")
      (node (ref "CELL12") (pin "2") (pinfunction "2_2") (pintype "passive"))
      (node (ref "IC19") (pin "5") (pinfunction "GPB4_5") (pintype "bidirectional"))
    )
    (net (code "28") (name "/BTN13") (class "Default")
      (node (ref "CELL13") (pin "2") (pinfunction "2_2") (pintype "passive"))
      (node (ref "IC19") (pin "6") (pinfunction "GPB5_6") (pintype "bidirectional"))
    )
    (net (code "29") (name "/BTN14") (class "Default")
      (node (ref "CELL14") (pin "2") (pinfunction "2_2") (pintype "passive"))
      (node (ref "IC19") (pin "7") (pinfunction "GPB6_7") (pintype "bidirectional"))
    )
    (net (code "30") (name "/BTN15") (class "Default")
      (node (ref "CELL15") (pin "2") (pinfunction "2_2") (pintype "passive"))
      (node (ref "IC19") (pin "8") (pinfunction "GPB7_8") (pintype "bidirectional"))
    )
    (net (code "31") (name "/BTN16") (class "Default")
      (node (ref "CELL16") (pin "2") (pinfunction "2_2") (pintype "passive"))
      (node (ref "IC20") (pin "21") (pinfunction "GPA0_21") (pintype "bidirectional"))
    )
    (net (code "32") (name "/BTN17") (class "Default")
      (node (ref "CELL17") (pin "2") (pinfunction "2_2") (pintype "passive"))
      (node (ref "IC20") (pin "22") (pinfunction "GPA1_22") (pintype "bidirectional"))
    )
    (net (code "33") (name "/BTN18") (class "Default")
      (node (ref "CELL18") (pin "2") (pinfunction "2_2") (pintype "passive"))
      (node (ref "IC20") (pin "23") (pinfunction "GPA2_23") (pintype "bidirectional"))
    )
    (net (code "34") (name "/BTN19") (class "Default")
      (node (ref "CELL19") (pin "2") (pinfunction "2_2") (pintype "passive"))
      (node (ref "IC20") (pin "24") (pinfunction "GPA3_24") (pintype "bidirectional"))
    )
    (net (code "35") (name "/BTN20") (class "Default")
      (node (ref "CELL20") (pin "2") (pinfunction "2_2") (pintype "passive"))
      (node (ref "IC20") (pin "25") (pinfunction "GPA4_25") (pintype "bidirectional"))
    )
    (net (code "36") (name "/BTN21") (class "Default")
      (node (ref "CELL21") (pin "2") (pinfunction "2_2") (pintype "passive"))
      (node (ref "IC20") (pin "26") (pinfunction "GPA5_26") (pintype "bidirectional"))
    )
    (net (code "37") (name "/BTN22") (class "Default")
      (node (ref "CELL22") (pin "2") (pinfunction "2_2") (pintype "passive"))
      (node (ref "IC20") (pin "27") (pinfunction "GPA6_27") (pintype "bidirectional"))
    )
    (net (code "38") (name "/BTN23") (class "Default")
      (node (ref "CELL23") (pin "2") (pinfunction "2_2") (pintype "passive"))
      (node (ref "IC20") (pin "28") (pinfunction "GPA7_28") (pintype "bidirectional"))
    )
    (net (code "39") (name "/BTN24") (class "Default")
      (node (ref "CELL24") (pin "2") (pinfunction "2_2") (pintype "passive"))
      (node (ref "IC20") (pin "1") (pinfunction "GPB0_1") (pintype "bidirectional"))
    )
    (net (code "40") (name "/BTN25") (class "Default")
      (node (ref "CELL25") (pin "2") (pinfunction "2_2") (pintype "passive"))
      (node (ref "IC20") (pin "2") (pinfunction "GPB1_2") (pintype "bidirectional"))
    )
    (net (code "41") (name "/BTN26") (class "Default")
      (node (ref "CELL26") (pin "2") (pinfunction "2_2") (pintype "passive"))
      (node (ref "IC20") (pin "3") (pinfunction "GPB2_3") (pintype "bidirectional"))
    )
    (net (code "42") (name "/BTN27") (class "Default")
      (node (ref "CELL27") (pin "2") (pinfunction "2_2") (pintype "passive"))
      (node (ref "IC20") (pin "4") (pinfunction "GPB3_4") (pintype "bidirectional"))
    )
    (net (code "43") (name "/BTN28") (class "Default")
      (node (ref "CELL28") (pin "2") (pinfunction "2_2") (pintype "passive"))
      (node (ref "IC20") (pin "5") (pinfunction "GPB4_5") (pintype "bidirectional"))
    )
    (net (code "44") (name "/BTN29") (class "Default")
      (node (ref "CELL29") (pin "2") (pinfunction "2_2") (pintype "passive"))
      (node (ref "IC20") (pin "6") (pinfunction "GPB5_6") (pintype "bidirectional"))
    )
    (net (code "45") (name "/BTN30") (class "Default")
      (node (ref "CELL30") (pin "2") (pinfunction "2_2") (pintype "passive"))
      (node (ref "IC20") (pin "7") (pinfunction "GPB6_7") (pintype "bidirectional"))
    )
    (net (code "46") (name "/BTN31") (class "Default")
      (node (ref "CELL31") (pin "2") (pinfunction "2_2") (pintype "passive"))
      (node (ref "IC20") (pin "8") (pinfunction "GPB7_8") (pintype "bidirectional"))
    )
    (net (code "47") (name "/BTN32") (class "Default")
      (node (ref "CELL32") (pin "2") (pinfunction "2_2") (pintype "passive"))
      (node (ref "IC21") (pin "21") (pinfunction "GPA0_21") (pintype "bidirectional"))
    )
    (net (code "48") (name "/BTN33") (class "Default")
      (node (ref "CELL33") (pin "2") (pinfunction "2_2") (pintype "passive"))
      (node (ref "IC21") (pin "22") (pinfunction "GPA1_22") (pintype "bidirectional"))
    )
    (net (code "49") (name "/BTN34") (class "Default")
      (node (ref "CELL34") (pin "2") (pinfunction "2_2") (pintype "passive"))
      (node (ref "IC21") (pin "23") (pinfunction "GPA2_23") (pintype "bidirectional"))
    )
    (net (code "50") (name "/BTN35") (class "Default")
      (node (ref "CELL35") (pin "2") (pinfunction "2_2") (pintype "passive"))
      (node (ref "IC21") (pin "24") (pinfunction "GPA3_24") (pintype "bidirectional"))
    )
    (net (code "51") (name "/BTN36") (class "Default")
      (node (ref "CELL36") (pin "2") (pinfunction "2_2") (pintype "passive"))
      (node (ref "IC21") (pin "25") (pinfunction "GPA4_25") (pintype "bidirectional"))
    )
    (net (code "52") (name "/BTN37") (class "Default")
      (node (ref "CELL37") (pin "2") (pinfunction "2_2") (pintype "passive"))
      (node (ref "IC21") (pin "26") (pinfunction "GPA5_26") (pintype "bidirectional"))
    )
    (net (code "53") (name "/BTN38") (class "Default")
      (node (ref "CELL38") (pin "2") (pinfunction "2_2") (pintype "passive"))
      (node (ref "IC21") (pin "27") (pinfunction "GPA6_27") (pintype "bidirectional"))
    )
    (net (code "54") (name "/BTN39") (class "Default")
      (node (ref "CELL39") (pin "2") (pinfunction "2_2") (pintype "passive"))
      (node (ref "IC21") (pin "28") (pinfunction "GPA7_28") (pintype "bidirectional"))
    )
    (net (code "55") (name "/BTN40") (class "Default")
      (node (ref "CELL40") (pin "2") (pinfunction "2_2") (pintype "passive"))
      (node (ref "IC21") (pin "1") (pinfunction "GPB0_1") (pintype "bidirectional"))
    )
    (net (code "56") (name "/BTN41") (class "Default")
      (node (ref "CELL41") (pin "2") (pinfunction "2_2") (pintype "passive"))
      (node (ref "IC21") (pin "2") (pinfunction "GPB1_2") (pintype "bidirectional"))
    )
    (net (code "57") (name "/BTN42") (class "Default")
      (node (ref "CELL42") (pin "2") (pinfunction "2_2") (pintype "passive"))
      (node (ref "IC21") (pin "3") (pinfunction "GPB2_3") (pintype "bidirectional"))
    )
    (net (code "58") (name "/BTN43") (class "Default")
      (node (ref "CELL43") (pin "2") (pinfunction "2_2") (pintype "passive"))
      (node (ref "IC21") (pin "4") (pinfunction "GPB3_4") (pintype "bidirectional"))
    )
    (net (code "59") (name "/BTN44") (class "Default")
      (node (ref "CELL44") (pin "2") (pinfunction "2_2") (pintype "passive"))
      (node (ref "IC21") (pin "5") (pinfunction "GPB4_5") (pintype "bidirectional"))
    )
    (net (code "60") (name "/BTN45") (class "Default")
      (node (ref "CELL45") (pin "2") (pinfunction "2_2") (pintype "passive"))
      (node (ref "IC21") (pin "6") (pinfunction "GPB5_6") (pintype "bidirectional"))
    )
    (net (code "61") (name "/BTN46") (class "Default")
      (node (ref "CELL46") (pin "2") (pinfunction "2_2") (pintype "passive"))
      (node (ref "IC21") (pin "7") (pinfunction "GPB6_7") (pintype "bidirectional"))
    )
    (net (code "62") (name "/BTN47") (class "Default")
      (node (ref "CELL47") (pin "2") (pinfunction "2_2") (pintype "passive"))
      (node (ref "IC21") (pin "8") (pinfunction "GPB7_8") (pintype "bidirectional"))
    )
    (net (code "63") (name "/BTN48") (class "Default")
      (node (ref "CELL48") (pin "2") (pinfunction "2_2") (pintype "passive"))
      (node (ref "IC22") (pin "21") (pinfunction "GPA0_21") (pintype "bidirectional"))
    )
    (net (code "64") (name "/BTN49") (class "Default")
      (node (ref "CELL49") (pin "2") (pinfunction "2_2") (pintype "passive"))
      (node (ref "IC22") (pin "22") (pinfunction "GPA1_22") (pintype "bidirectional"))
    )
    (net (code "65") (name "/BTN50") (class "Default")
      (node (ref "CELL50") (pin "2") (pinfunction "2_2") (pintype "passive"))
      (node (ref "IC22") (pin "23") (pinfunction "GPA2_23") (pintype "bidirectional"))
    )
    (net (code "66") (name "/BTN51") (class "Default")
      (node (ref "CELL51") (pin "2") (pinfunction "2_2") (pintype "passive"))
      (node (ref "IC22") (pin "24") (pinfunction "GPA3_24") (pintype "bidirectional"))
    )
    (net (code "67") (name "/BTN52") (class "Default")
      (node (ref "CELL52") (pin "2") (pinfunction "2_2") (pintype "passive"))
      (node (ref "IC22") (pin "25") (pinfunction "GPA4_25") (pintype "bidirectional"))
    )
    (net (code "68") (name "/BTN53") (class "Default")
      (node (ref "CELL53") (pin "2") (pinfunction "2_2") (pintype "passive"))
      (node (ref "IC22") (pin "26") (pinfunction "GPA5_26") (pintype "bidirectional"))
    )
    (net (code "69") (name "/BTN54") (class "Default")
      (node (ref "CELL54") (pin "2") (pinfunction "2_2") (pintype "passive"))
      (node (ref "IC22") (pin "27") (pinfunction "GPA6_27") (pintype "bidirectional"))
    )
    (net (code "70") (name "/BTN55") (class "Default")
      (node (ref "CELL55") (pin "2") (pinfunction "2_2") (pintype "passive"))
      (node (ref "IC22") (pin "28") (pinfunction "GPA7_28") (pintype "bidirectional"))
    )
    (net (code "71") (name "/BTN56") (class "Default")
      (node (ref "CELL56") (pin "2") (pinfunction "2_2") (pintype "passive"))
      (node (ref "IC22") (pin "1") (pinfunction "GPB0_1") (pintype "bidirectional"))
    )
    (net (code "72") (name "/BTN57") (class "Default")
      (node (ref "CELL57") (pin "2") (pinfunction "2_2") (pintype "passive"))
      (node (ref "IC22") (pin "2") (pinfunction "GPB1_2") (pintype "bidirectional"))
    )
    (net (code "73") (name "/BTN58") (class "Default")
      (node (ref "CELL58") (pin "2") (pinfunction "2_2") (pintype "passive"))
      (node (ref "IC22") (pin "3") (pinfunction "GPB2_3") (pintype "bidirectional"))
    )
    (net (code "74") (name "/BTN59") (class "Default")
      (node (ref "CELL59") (pin "2") (pinfunction "2_2") (pintype "passive"))
      (node (ref "IC22") (pin "4") (pinfunction "GPB3_4") (pintype "bidirectional"))
    )
    (net (code "75") (name "/BTN60") (class "Default")
      (node (ref "CELL60") (pin "2") (pinfunction "2_2") (pintype "passive"))
      (node (ref "IC22") (pin "5") (pinfunction "GPB4_5") (pintype "bidirectional"))
    )
    (net (code "76") (name "/BTN61") (class "Default")
      (node (ref "CELL61") (pin "2") (pinfunction "2_2") (pintype "passive"))
      (node (ref "IC22") (pin "6") (pinfunction "GPB5_6") (pintype "bidirectional"))
    )
    (net (code "77") (name "/BTN62") (class "Default")
      (node (ref "CELL62") (pin "2") (pinfunction "2_2") (pintype "passive"))
      (node (ref "IC22") (pin "7") (pinfunction "GPB6_7") (pintype "bidirectional"))
    )
    (net (code "78") (name "/BTN63") (class "Default")
      (node (ref "CELL63") (pin "2") (pinfunction "2_2") (pintype "passive"))
      (node (ref "IC22") (pin "8") (pinfunction "GPB7_8") (pintype "bidirectional"))
    )
    (net (code "79") (name "/BTN64") (class "Default")
      (node (ref "CELL64") (pin "2") (pinfunction "2_2") (pintype "passive"))
      (node (ref "IC23") (pin "21") (pinfunction "GPA0_21") (pintype "bidirectional"))
    )
    (net (code "80") (name "/BTN65") (class "Default")
      (node (ref "CELL65") (pin "2") (pinfunction "2_2") (pintype "passive"))
      (node (ref "IC23") (pin "22") (pinfunction "GPA1_22") (pintype "bidirectional"))
    )
    (net (code "81") (name "/BTN66") (class "Default")
      (node (ref "CELL66") (pin "2") (pinfunction "2_2") (pintype "passive"))
      (node (ref "IC23") (pin "23") (pinfunction "GPA2_23") (pintype "bidirectional"))
    )
    (net (code "82") (name "/BTN67") (class "Default")
      (node (ref "CELL67") (pin "2") (pinfunction "2_2") (pintype "passive"))
      (node (ref "IC23") (pin "24") (pinfunction "GPA3_24") (pintype "bidirectional"))
    )
    (net (code "83") (name "/BTN68") (class "Default")
      (node (ref "CELL68") (pin "2") (pinfunction "2_2") (pintype "passive"))
      (node (ref "IC23") (pin "25") (pinfunction "GPA4_25") (pintype "bidirectional"))
    )
    (net (code "84") (name "/BTN69") (class "Default")
      (node (ref "CELL69") (pin "2") (pinfunction "2_2") (pintype "passive"))
      (node (ref "IC23") (pin "26") (pinfunction "GPA5_26") (pintype "bidirectional"))
    )
    (net (code "85") (name "/BTN70") (class "Default")
      (node (ref "CELL70") (pin "2") (pinfunction "2_2") (pintype "passive"))
      (node (ref "IC23") (pin "27") (pinfunction "GPA6_27") (pintype "bidirectional"))
    )
    (net (code "86") (name "/BTN71") (class "Default")
      (node (ref "CELL71") (pin "2") (pinfunction "2_2") (pintype "passive"))
      (node (ref "IC23") (pin "28") (pinfunction "GPA7_28") (pintype "bidirectional"))
    )
    (net (code "87") (name "/BTN72") (class "Default")
      (node (ref "CELL72") (pin "2") (pinfunction "2_2") (pintype "passive"))
      (node (ref "IC23") (pin "1") (pinfunction "GPB0_1") (pintype "bidirectional"))
    )
    (net (code "88") (name "/BTN73") (class "Default")
      (node (ref "CELL73") (pin "2") (pinfunction "2_2") (pintype "passive"))
      (node (ref "IC23") (pin "2") (pinfunction "GPB1_2") (pintype "bidirectional"))
    )
    (net (code "89") (name "/BTN74") (class "Default")
      (node (ref "CELL74") (pin "2") (pinfunction "2_2") (pintype "passive"))
      (node (ref "IC23") (pin "3") (pinfunction "GPB2_3") (pintype "bidirectional"))
    )
    (net (code "90") (name "/BTN75") (class "Default")
      (node (ref "CELL75") (pin "2") (pinfunction "2_2") (pintype "passive"))
      (node (ref "IC23") (pin "4") (pinfunction "GPB3_4") (pintype "bidirectional"))
    )
    (net (code "91") (name "/BTN76") (class "Default")
      (node (ref "CELL76") (pin "2") (pinfunction "2_2") (pintype "passive"))
      (node (ref "IC23") (pin "5") (pinfunction "GPB4_5") (pintype "bidirectional"))
    )
    (net (code "92") (name "/BTN77") (class "Default")
      (node (ref "CELL77") (pin "2") (pinfunction "2_2") (pintype "passive"))
      (node (ref "IC23") (pin "6") (pinfunction "GPB5_6") (pintype "bidirectional"))
    )
    (net (code "93") (name "/BTN78") (class "Default")
      (node (ref "CELL78") (pin "2") (pinfunction "2_2") (pintype "passive"))
      (node (ref "IC23") (pin "7") (pinfunction "GPB6_7") (pintype "bidirectional"))
    )
    (net (code "94") (name "/BTN79") (class "Default")
      (node (ref "CELL79") (pin "2") (pinfunction "2_2") (pintype "passive"))
      (node (ref "IC23") (pin "8") (pinfunction "GPB7_8") (pintype "bidirectional"))
    )
    (net (code "95") (name "/BTN80") (class "Default")
      (node (ref "CELL80") (pin "2") (pinfunction "2_2") (pintype "passive"))
      (node (ref "IC24") (pin "21") (pinfunction "GPA0_21") (pintype "bidirectional"))
    )
    (net (code "96") (name "/BTN81") (class "Default")
      (node (ref "CELL81") (pin "2") (pinfunction "2_2") (pintype "passive"))
      (node (ref "IC24") (pin "22") (pinfunction "GPA1_22") (pintype "bidirectional"))
    )
    (net (code "97") (name "/BTN82") (class "Default")
      (node (ref "CELL82") (pin "2") (pinfunction "2_2") (pintype "passive"))
      (node (ref "IC24") (pin "23") (pinfunction "GPA2_23") (pintype "bidirectional"))
    )
    (net (code "98") (name "/BTN83") (class "Default")
      (node (ref "CELL83") (pin "2") (pinfunction "2_2") (pintype "passive"))
      (node (ref "IC24") (pin "24") (pinfunction "GPA3_24") (pintype "bidirectional"))
    )
    (net (code "99") (name "/BTN84") (class "Default")
      (node (ref "CELL84") (pin "2") (pinfunction "2_2") (pintype "passive"))
      (node (ref "IC24") (pin "25") (pinfunction "GPA4_25") (pintype "bidirectional"))
    )
    (net (code "100") (name "/BTN85") (class "Default")
      (node (ref "CELL85") (pin "2") (pinfunction "2_2") (pintype "passive"))
      (node (ref "IC24") (pin "26") (pinfunction "GPA5_26") (pintype "bidirectional"))
    )
    (net (code "101") (name "/BTN86") (class "Default")
      (node (ref "CELL86") (pin "2") (pinfunction "2_2") (pintype "passive"))
      (node (ref "IC24") (pin "27") (pinfunction "GPA6_27") (pintype "bidirectional"))
    )
    (net (code "102") (name "/BTN87") (class "Default")
      (node (ref "CELL87") (pin "2") (pinfunction "2_2") (pintype "passive"))
      (node (ref "IC24") (pin "28") (pinfunction "GPA7_28") (pintype "bidirectional"))
    )
    (net (code "103") (name "/BTN88") (class "Default")
      (node (ref "CELL88") (pin "2") (pinfunction "2_2") (pintype "passive"))
      (node (ref "IC24") (pin "1") (pinfunction "GPB0_1") (pintype "bidirectional"))
    )
    (net (code "104") (name "/BTN89") (class "Default")
      (node (ref "CELL89") (pin "2") (pinfunction "2_2") (pintype "passive"))
      (node (ref "IC24") (pin "2") (pinfunction "GPB1_2") (pintype "bidirectional"))
    )
    (net (code "105") (name "/BTN90") (class "Default")
      (node (ref "CELL90") (pin "2") (pinfunction "2_2") (pintype "passive"))
      (node (ref "IC24") (pin "3") (pinfunction "GPB2_3") (pintype "bidirectional"))
    )
    (net (code "106") (name "/BTN91") (class "Default")
      (node (ref "CELL91") (pin "2") (pinfunction "2_2") (pintype "passive"))
      (node (ref "IC24") (pin "4") (pinfunction "GPB3_4") (pintype "bidirectional"))
    )
    (net (code "107") (name "/BTN92") (class "Default")
      (node (ref "CELL92") (pin "2") (pinfunction "2_2") (pintype "passive"))
      (node (ref "IC24") (pin "5") (pinfunction "GPB4_5") (pintype "bidirectional"))
    )
    (net (code "108") (name "/BTN93") (class "Default")
      (node (ref "CELL93") (pin "2") (pinfunction "2_2") (pintype "passive"))
      (node (ref "IC24") (pin "6") (pinfunction "GPB5_6") (pintype "bidirectional"))
    )
    (net (code "109") (name "/BTN94") (class "Default")
      (node (ref "CELL94") (pin "2") (pinfunction "2_2") (pintype "passive"))
      (node (ref "IC24") (pin "7") (pinfunction "GPB6_7") (pintype "bidirectional"))
    )
    (net (code "110") (name "/BTN95") (class "Default")
      (node (ref "CELL95") (pin "2") (pinfunction "2_2") (pintype "passive"))
      (node (ref "IC24") (pin "8") (pinfunction "GPB7_8") (pintype "bidirectional"))
    )
    (net (code "111") (name "/BTN96") (class "Default")
      (node (ref "CELL96") (pin "2") (pinfunction "2_2") (pintype "passive"))
      (node (ref "IC25") (pin "21") (pinfunction "GPA0_21") (pintype "bidirectional"))
    )
    (net (code "112") (name "/BTN97") (class "Default")
      (node (ref "CELL97") (pin "2") (pinfunction "2_2") (pintype "passive"))
      (node (ref "IC25") (pin "22") (pinfunction "GPA1_22") (pintype "bidirectional"))
    )
    (net (code "113") (name "/BTN98") (class "Default")
      (node (ref "CELL98") (pin "2") (pinfunction "2_2") (pintype "passive"))
      (node (ref "IC25") (pin "23") (pinfunction "GPA2_23") (pintype "bidirectional"))
    )
    (net (code "114") (name "/BTN99") (class "Default")
      (node (ref "CELL99") (pin "2") (pinfunction "2_2") (pintype "passive"))
      (node (ref "IC25") (pin "24") (pinfunction "GPA3_24") (pintype "bidirectional"))
    )
    (net (code "115") (name "/BTN100") (class "Default")
      (node (ref "CELL100") (pin "2") (pinfunction "2_2") (pintype "passive"))
      (node (ref "IC25") (pin "25") (pinfunction "GPA4_25") (pintype "bidirectional"))
    )
    (net (code "116") (name "/BTN101") (class "Default")
      (node (ref "CELL101") (pin "2") (pinfunction "2_2") (pintype "passive"))
      (node (ref "IC25") (pin "26") (pinfunction "GPA5_26") (pintype "bidirectional"))
    )
    (net (code "117") (name "/BTN102") (class "Default")
      (node (ref "CELL102") (pin "2") (pinfunction "2_2") (pintype "passive"))
      (node (ref "IC25") (pin "27") (pinfunction "GPA6_27") (pintype "bidirectional"))
    )
    (net (code "118") (name "/BTN103") (class "Default")
      (node (ref "CELL103") (pin "2") (pinfunction "2_2") (pintype "passive"))
      (node (ref "IC25") (pin "28") (pinfunction "GPA7_28") (pintype "bidirectional"))
    )
    (net (code "119") (name "/BTN_INT") (class "Default")
      (node (ref "IC19") (pin "20") (pinfunction "INTA_20") (pintype "output"))
      (node (ref "IC20") (pin "20") (pinfunction "INTA_20") (pintype "output"))
      (node (ref "IC21") (pin "20") (pinfunction "INTA_20") (pintype "output"))
      (node (ref "IC22") (pin "20") (pinfunction "INTA_20") (pintype "output"))
      (node (ref "IC23") (pin "20") (pinfunction "INTA_20") (pintype "output"))
      (node (ref "IC24") (pin "20") (pinfunction "INTA_20") (pintype "output"))
      (node (ref "IC25") (pin "20") (pinfunction "INTA_20") (pintype "output"))
      (node (ref "R1") (pin "1") (pinfunction "1_1") (pintype "passive"))
      (node (ref "U1") (pin "4") (pinfunction "PD2(INT0)_4") (pintype "bidirectional"))
    )
    (net (code "120") (name "/CC1") (class "Default")
      (node (ref "JP1") (pin "4") (pinfunction "4_4") (pintype "passive"))
    )
    (net (code "121") (name "/CC2") (class "Default")
      (node (ref "JP1") (pin "8") (pinfunction "8_8") (pintype "passive"))
    )
    (net (code "122") (name "/CS_IO") (class "Default")
      (node (ref "IC18") (pin "11") (pinfunction "~{CS}_11") (pintype "input"))
      (node (ref "IC19") (pin "11") (pinfunction "~{CS}_11") (pintype "input"))
      (node (ref "IC20") (pin "11") (pinfunction "~{CS}_11") (pintype "input"))
      (node (ref "IC21") (pin "11") (pinfunction "~{CS}_11") (pintype "input"))
      (node (ref "IC22") (pin "11") (pinfunction "~{CS}_11") (pintype "input"))
      (node (ref "IC23") (pin "11") (pinfunction "~{CS}_11") (pintype "input"))
      (node (ref "IC24") (pin "11") (pinfunction "~{CS}_11") (pintype "input"))
      (node (ref "IC25") (pin "11") (pinfunction "~{CS}_11") (pintype "input"))
      (node (ref "U1") (pin "16") (pinfunction "PB2(SS/OC1B)_16") (pintype "bidirectional"))
    )
    (net (code "123") (name "/D+") (class "Default")
      (node (ref "JP1") (pin "6") (pinfunction "6_6") (pintype "passive"))
    )
    (net (code "124") (name "/D-") (class "Default")
      (node (ref "JP1") (pin "5") (pinfunction "5_5") (pintype "passive"))
    )
    (net (code "125") (name "/GND") (class "Default")
      (node (ref "C1") (pin "1") (pinfunction "1_1") (pintype "passive"))
      (node (ref "C2") (pin "1") (pinfunction "1_1") (pintype "passive"))
      (node (ref "C3") (pin "1") (pinfunction "1_1") (pintype "passive"))
      (node (ref "C4") (pin "1") (pinfunction "1_1") (pintype "passive"))
      (node (ref "C5") (pin "1") (pinfunction "1_1") (pintype "passive"))
      (node (ref "C6") (pin "1") (pinfunction "1_1") (pintype "passive"))
      (node (ref "C7") (pin "1") (pinfunction "1_1") (pintype "passive"))
      (node (ref "C8") (pin "1") (pinfunction "1_1") (pintype "passive"))
      (node (ref "CELL0") (pin "5") (pinfunction "5_5") (pintype "passive"))
      (node (ref "CELL1") (pin "5") (pinfunction "5_5") (pintype "passive"))
      (node (ref "CELL10") (pin "5") (pinfunction "5_5") (pintype "passive"))
      (node (ref "CELL100") (pin "5") (pinfunction "5_5") (pintype "passive"))
      (node (ref "CELL101") (pin "5") (pinfunction "5_5") (pintype "passive"))
      (node (ref "CELL102") (pin "5") (pinfunction "5_5") (pintype "passive"))
      (node (ref "CELL103") (pin "5") (pinfunction "5_5") (pintype "passive"))
      (node (ref "CELL11") (pin "5") (pinfunction "5_5") (pintype "passive"))
      (node (ref "CELL12") (pin "5") (pinfunction "5_5") (pintype "passive"))
      (node (ref "CELL13") (pin "5") (pinfunction "5_5") (pintype "passive"))
      (node (ref "CELL14") (pin "5") (pinfunction "5_5") (pintype "passive"))
      (node (ref "CELL15") (pin "5") (pinfunction "5_5") (pintype "passive"))
      (node (ref "CELL16") (pin "5") (pinfunction "5_5") (pintype "passive"))
      (node (ref "CELL17") (pin "5") (pinfunction "5_5") (pintype "passive"))
      (node (ref "CELL18") (pin "5") (pinfunction "5_5") (pintype "passive"))
      (node (ref "CELL19") (pin "5") (pinfunction "5_5") (pintype "passive"))
      (node (ref "CELL2") (pin "5") (pinfunction "5_5") (pintype "passive"))
      (node (ref "CELL20") (pin "5") (pinfunction "5_5") (pintype "passive"))
      (node (ref "CELL21") (pin "5") (pinfunction "5_5") (pintype "passive"))
      (node (ref "CELL22") (pin "5") (pinfunction "5_5") (pintype "passive"))
      (node (ref "CELL23") (pin "5") (pinfunction "5_5") (pintype "passive"))
      (node (ref "CELL24") (pin "5") (pinfunction "5_5") (pintype "passive"))
      (node (ref "CELL25") (pin "5") (pinfunction "5_5") (pintype "passive"))
      (node (ref "CELL26") (pin "5") (pinfunction "5_5") (pintype "passive"))
      (node (ref "CELL27") (pin "5") (pinfunction "5_5") (pintype "passive"))
      (node (ref "CELL28") (pin "5") (pinfunction "5_5") (pintype "passive"))
      (node (ref "CELL29") (pin "5") (pinfunction "5_5") (pintype "passive"))
      (node (ref "CELL3") (pin "5") (pinfunction "5_5") (pintype "passive"))
      (node (ref "CELL30") (pin "5") (pinfunction "5_5") (pintype "passive"))
      (node (ref "CELL31") (pin "5") (pinfunction "5_5") (pintype "passive"))
      (node (ref "CELL32") (pin "5") (pinfunction "5_5") (pintype "passive"))
      (node (ref "CELL33") (pin "5") (pinfunction "5_5") (pintype "passive"))
      (node (ref "CELL34") (pin "5") (pinfunction "5_5") (pintype "passive"))
      (node (ref "CELL35") (pin "5") (pinfunction "5_5") (pintype "passive"))
      (node (ref "CELL36") (pin "5") (pinfunction "5_5") (pintype "passive"))
      (node (ref "CELL37") (pin "5") (pinfunction "5_5") (pintype "passive"))
      (node (ref "CELL38") (pin "5") (pinfunction "5_5") (pintype "passive"))
      (node (ref "CELL39") (pin "5") (pinfunction "5_5") (pintype "passive"))
      (node (ref "CELL4") (pin "5") (pinfunction "5_5") (pintype "passive"))
      (node (ref "CELL40") (pin "5") (pinfunction "5_5") (pintype "passive"))
      (node (ref "CELL41") (pin "5") (pinfunction "5_5") (pintype "passive"))
      (node (ref "CELL42") (pin "5") (pinfunction "5_5") (pintype "passive"))
      (node (ref "CELL43") (pin "5") (pinfunction "5_5") (pintype "passive"))
      (node (ref "CELL44") (pin "5") (pinfunction "5_5") (pintype "passive"))
      (node (ref "CELL45") (pin "5") (pinfunction "5_5") (pintype "passive"))
      (node (ref "CELL46") (pin "5") (pinfunction "5_5") (pintype "passive"))
      (node (ref "CELL47") (pin "5") (pinfunction "5_5") (pintype "passive"))
      (node (ref "CELL48") (pin "5") (pinfunction "5_5") (pintype "passive"))
      (node (ref "CELL49") (pin "5") (pinfunction "5_5") (pintype "passive"))
      (node (ref "CELL5") (pin "5") (pinfunction "5_5") (pintype "passive"))
      (node (ref "CELL50") (pin "5") (pinfunction "5_5") (pintype "passive"))
      (node (ref "CELL51") (pin "5") (pinfunction "5_5") (pintype "passive"))
      (node (ref "CELL52") (pin "5") (pinfunction "5_5") (pintype "passive"))
      (node (ref "CELL53") (pin "5") (pinfunction "5_5") (pintype "passive"))
      (node (ref "CELL54") (pin "5") (pinfunction "5_5") (pintype "passive"))
      (node (ref "CELL55") (pin "5") (pinfunction "5_5") (pintype "passive"))
      (node (ref "CELL56") (pin "5") (pinfunction "5_5") (pintype "passive"))
      (node (ref "CELL57") (pin "5") (pinfunction "5_5") (pintype "passive"))
      (node (ref "CELL58") (pin "5") (pinfunction "5_5") (pintype "passive"))
      (node (ref "CELL59") (pin "5") (pinfunction "5_5") (pintype "passive"))
      (node (ref "CELL6") (pin "5") (pinfunction "5_5") (pintype "passive"))
      (node (ref "CELL60") (pin "5") (pinfunction "5_5") (pintype "passive"))
      (node (ref "CELL61") (pin "5") (pinfunction "5_5") (pintype "passive"))
      (node (ref "CELL62") (pin "5") (pinfunction "5_5") (pintype "passive"))
      (node (ref "CELL63") (pin "5") (pinfunction "5_5") (pintype "passive"))
      (node (ref "CELL64") (pin "5") (pinfunction "5_5") (pintype "passive"))
      (node (ref "CELL65") (pin "5") (pinfunction "5_5") (pintype "passive"))
      (node (ref "CELL66") (pin "5") (pinfunction "5_5") (pintype "passive"))
      (node (ref "CELL67") (pin "5") (pinfunction "5_5") (pintype "passive"))
      (node (ref "CELL68") (pin "5") (pinfunction "5_5") (pintype "passive"))
      (node (ref "CELL69") (pin "5") (pinfunction "5_5") (pintype "passive"))
      (node (ref "CELL7") (pin "5") (pinfunction "5_5") (pintype "passive"))
      (node (ref "CELL70") (pin "5") (pinfunction "5_5") (pintype "passive"))
      (node (ref "CELL71") (pin "5") (pinfunction "5_5") (pintype "passive"))
      (node (ref "CELL72") (pin "5") (pinfunction "5_5") (pintype "passive"))
      (node (ref "CELL73") (pin "5") (pinfunction "5_5") (pintype "passive"))
      (node (ref "CELL74") (pin "5") (pinfunction "5_5") (pintype "passive"))
      (node (ref "CELL75") (pin "5") (pinfunction "5_5") (pintype "passive"))
      (node (ref "CELL76") (pin "5") (pinfunction "5_5") (pintype "passive"))
      (node (ref "CELL77") (pin "5") (pinfunction "5_5") (pintype "passive"))
      (node (ref "CELL78") (pin "5") (pinfunction "5_5") (pintype "passive"))
      (node (ref "CELL79") (pin "5") (pinfunction "5_5") (pintype "passive"))
      (node (ref "CELL8") (pin "5") (pinfunction "5_5") (pintype "passive"))
      (node (ref "CELL80") (pin "5") (pinfunction "5_5") (pintype "passive"))
      (node (ref "CELL81") (pin "5") (pinfunction "5_5") (pintype "passive"))
      (node (ref "CELL82") (pin "5") (pinfunction "5_5") (pintype "passive"))
      (node (ref "CELL83") (pin "5") (pinfunction "5_5") (pintype "passive"))
      (node (ref "CELL84") (pin "5") (pinfunction "5_5") (pintype "passive"))
      (node (ref "CELL85") (pin "5") (pinfunction "5_5") (pintype "passive"))
      (node (ref "CELL86") (pin "5") (pinfunction "5_5") (pintype "passive"))
      (node (ref "CELL87") (pin "5") (pinfunction "5_5") (pintype "passive"))
      (node (ref "CELL88") (pin "5") (pinfunction "5_5") (pintype "passive"))
      (node (ref "CELL89") (pin "5") (pinfunction "5_5") (pintype "passive"))
      (node (ref "CELL9") (pin "5") (pinfunction "5_5") (pintype "passive"))
      (node (ref "CELL90") (pin "5") (pinfunction "5_5") (pintype "passive"))
      (node (ref "CELL91") (pin "5") (pinfunction "5_5") (pintype "passive"))
      (node (ref "CELL92") (pin "5") (pinfunction "5_5") (pintype "passive"))
      (node (ref "CELL93") (pin "5") (pinfunction "5_5") (pintype "passive"))
      (node (ref "CELL94") (pin "5") (pinfunction "5_5") (pintype "passive"))
      (node (ref "CELL95") (pin "5") (pinfunction "5_5") (pintype "passive"))
      (node (ref "CELL96") (pin "5") (pinfunction "5_5") (pintype "passive"))
      (node (ref "CELL97") (pin "5") (pinfunction "5_5") (pintype "passive"))
      (node (ref "CELL98") (pin "5") (pinfunction "5_5") (pintype "passive"))
      (node (ref "CELL99") (pin "5") (pinfunction "5_5") (pintype "passive"))
      (node (ref "IC1") (pin "14") (pinfunction "AGND_14") (pintype "power_in"))
      (node (ref "IC1") (pin "9") (pinfunction "GND_9") (pintype "power_in"))
      (node (ref "IC10") (pin "14") (pinfunction "AGND_14") (pintype "power_in"))
      (node (ref "IC10") (pin "9") (pinfunction "GND_9") (pintype "power_in"))
      (node (ref "IC11") (pin "14") (pinfunction "AGND_14") (pintype "power_in"))
      (node (ref "IC11") (pin "9") (pinfunction "GND_9") (pintype "power_in"))
      (node (ref "IC12") (pin "14") (pinfunction "AGND_14") (pintype "power_in"))
      (node (ref "IC12") (pin "9") (pinfunction "GND_9") (pintype "power_in"))
      (node (ref "IC13") (pin "1") (pinfunction "GND_1") (pintype "power_in"))
      (node (ref "IC14") (pin "1") (pinfunction "GND_1") (pintype "power_in"))
      (node (ref "IC15") (pin "1") (pinfunction "GND_1") (pintype "power_in"))
      (node (ref "IC16") (pin "1") (pinfunction "GND_1") (pintype "power_in"))
      (node (ref "IC17") (pin "1") (pinfunction "GND_1") (pintype "power_in"))
      (node (ref "IC18") (pin "10") (pinfunction "VSS_10") (pintype "power_in"))
      (node (ref "IC18") (pin "15") (pinfunction "A0_15") (pintype "input"))
      (node (ref "IC18") (pin "16") (pinfunction "A1_16") (pintype "input"))
      (node (ref "IC18") (pin "17") (pinfunction "A2_17") (pintype "input"))
      (node (ref "IC19") (pin "10") (pinfunction "VSS_10") (pintype "power_in"))
      (node (ref "IC19") (pin "16") (pinfunction "A1_16") (pintype "input"))
      (node (ref "IC19") (pin "17") (pinfunction "A2_17") (pintype "input"))
      (node (ref "IC2") (pin "14") (pinfunction "AGND_14") (pintype "power_in"))
      (node (ref "IC2") (pin "9") (pinfunction "GND_9") (pintype "power_in"))
      (node (ref "IC20") (pin "10") (pinfunction "VSS_10") (pintype "power_in"))
      (node (ref "IC20") (pin "15") (pinfunction "A0_15") (pintype "input"))
      (node (ref "IC20") (pin "17") (pinfunction "A2_17") (pintype "input"))
      (node (ref "IC21") (pin "10") (pinfunction "VSS_10") (pintype "power_in"))
      (node (ref "IC21") (pin "17") (pinfunction "A2_17") (pintype "input"))
      (node (ref "IC22") (pin "10") (pinfunction "VSS_10") (pintype "power_in"))
      (node (ref "IC22") (pin "15") (pinfunction "A0_15") (pintype "input"))
      (node (ref "IC22") (pin "16") (pinfunction "A1_16") (pintype "input"))
      (node (ref "IC23") (pin "10") (pinfunction "VSS_10") (pintype "power_in"))
      (node (ref "IC23") (pin "16") (pinfunction "A1_16") (pintype "input"))
      (node (ref "IC24") (pin "10") (pinfunction "VSS_10") (pintype "power_in"))
      (node (ref "IC24") (pin "15") (pinfunction "A0_15") (pintype "input"))
      (node (ref "IC25") (pin "10") (pinfunction "VSS_10") (pintype "power_in"))
      (node (ref "IC26") (pin "14") (pinfunction "AGND_14") (pintype "power_in"))
      (node (ref "IC26") (pin "9") (pinfunction "GND_9") (pintype "power_in"))
      (node (ref "IC3") (pin "14") (pinfunction "AGND_14") (pintype "power_in"))
      (node (ref "IC3") (pin "9") (pinfunction "GND_9") (pintype "power_in"))
      (node (ref "IC4") (pin "14") (pinfunction "AGND_14") (pintype "power_in"))
      (node (ref "IC4") (pin "9") (pinfunction "GND_9") (pintype "power_in"))
      (node (ref "IC5") (pin "14") (pinfunction "AGND_14") (pintype "power_in"))
      (node (ref "IC5") (pin "9") (pinfunction "GND_9") (pintype "power_in"))
      (node (ref "IC6") (pin "14") (pinfunction "AGND_14") (pintype "power_in"))
      (node (ref "IC6") (pin "9") (pinfunction "GND_9") (pintype "power_in"))
      (node (ref "IC7") (pin "14") (pinfunction "AGND_14") (pintype "power_in"))
      (node (ref "IC7") (pin "9") (pinfunction "GND_9") (pintype "power_in"))
      (node (ref "IC8") (pin "14") (pinfunction "AGND_14") (pintype "power_in"))
      (node (ref "IC8") (pin "9") (pinfunction "GND_9") (pintype "power_in"))
      (node (ref "IC9") (pin "14") (pinfunction "AGND_14") (pintype "power_in"))
      (node (ref "IC9") (pin "9") (pinfunction "GND_9") (pintype "power_in"))
      (node (ref "ISP") (pin "6") (pinfunction "6_6") (pintype "passive"))
      (node (ref "JP1") (pin "1") (pinfunction "1_1") (pintype "passive"))
      (node (ref "JP2") (pin "20") (pinfunction "20_20") (pintype "passive"))
      (node (ref "JP2") (pin "4") (pinfunction "4_4") (pintype "passive"))
      (node (ref "JP3") (pin "3") (pinfunction "3_3") (pintype "passive"))
      (node (ref "R10") (pin "2") (pinfunction "2_2") (pintype "passive"))
      (node (ref "R100") (pin "2") (pinfunction "2_2") (pintype "passive"))
      (node (ref "R101") (pin "2") (pinfunction "2_2") (pintype "passive"))
      (node (ref "R102") (pin "2") (pinfunction "2_2") (pintype "passive"))
      (node (ref "R103") (pin "2") (pinfunction "2_2") (pintype "passive"))
      (node (ref "R104") (pin "2") (pinfunction "2_2") (pintype "passive"))
      (node (ref "R105") (pin "2") (pinfunction "2_2") (pintype "passive"))
      (node (ref "R106") (pin "2") (pinfunction "2_2") (pintype "passive"))
      (node (ref "R107") (pin "2") (pinfunction "2_2") (pintype "passive"))
      (node (ref "R108") (pin "2") (pinfunction "2_2") (pintype "passive"))
      (node (ref "R109") (pin "2") (pinfunction "2_2") (pintype "passive"))
      (node (ref "R11") (pin "2") (pinfunction "2_2") (pintype "passive"))
      (node (ref "R110") (pin "2") (pinfunction "2_2") (pintype "passive"))
      (node (ref "R111") (pin "2") (pinfunction "2_2") (pintype "passive"))
      (node (ref "R12") (pin "2") (pinfunction "2_2") (pintype "passive"))
      (node (ref "R13") (pin "2") (pinfunction "2_2") (pintype "passive"))
      (node (ref "R14") (pin "2") (pinfunction "2_2") (pintype "passive"))
      (node (ref "R15") (pin "2") (pinfunction "2_2") (pintype "passive"))
      (node (ref "R16") (pin "2") (pinfunction "2_2") (pintype "passive"))
      (node (ref "R17") (pin "2") (pinfunction "2_2") (pintype "passive"))
      (node (ref "R18") (pin "2") (pinfunction "2_2") (pintype "passive"))
      (node (ref "R19") (pin "2") (pinfunction "2_2") (pintype "passive"))
      (node (ref "R2") (pin "2") (pinfunction "2_2") (pintype "passive"))
      (node (ref "R20") (pin "2") (pinfunction "2_2") (pintype "passive"))
      (node (ref "R21") (pin "2") (pinfunction "2_2") (pintype "passive"))
      (node (ref "R22") (pin "2") (pinfunction "2_2") (pintype "passive"))
      (node (ref "R23") (pin "2") (pinfunction "2_2") (pintype "passive"))
      (node (ref "R24") (pin "2") (pinfunction "2_2") (pintype "passive"))
      (node (ref "R25") (pin "2") (pinfunction "2_2") (pintype "passive"))
      (node (ref "R26") (pin "2") (pinfunction "2_2") (pintype "passive"))
      (node (ref "R27") (pin "2") (pinfunction "2_2") (pintype "passive"))
      (node (ref "R28") (pin "2") (pinfunction "2_2") (pintype "passive"))
      (node (ref "R29") (pin "2") (pinfunction "2_2") (pintype "passive"))
      (node (ref "R3") (pin "2") (pinfunction "2_2") (pintype "passive"))
      (node (ref "R30") (pin "2") (pinfunction "2_2") (pintype "passive"))
      (node (ref "R31") (pin "2") (pinfunction "2_2") (pintype "passive"))
      (node (ref "R32") (pin "2") (pinfunction "2_2") (pintype "passive"))
      (node (ref "R33") (pin "2") (pinfunction "2_2") (pintype "passive"))
      (node (ref "R34") (pin "2") (pinfunction "2_2") (pintype "passive"))
      (node (ref "R35") (pin "2") (pinfunction "2_2") (pintype "passive"))
      (node (ref "R36") (pin "2") (pinfunction "2_2") (pintype "passive"))
      (node (ref "R37") (pin "2") (pinfunction "2_2") (pintype "passive"))
      (node (ref "R38") (pin "2") (pinfunction "2_2") (pintype "passive"))
      (node (ref "R39") (pin "2") (pinfunction "2_2") (pintype "passive"))
      (node (ref "R4") (pin "2") (pinfunction "2_2") (pintype "passive"))
      (node (ref "R40") (pin "2") (pinfunction "2_2") (pintype "passive"))
      (node (ref "R41") (pin "2") (pinfunction "2_2") (pintype "passive"))
      (node (ref "R42") (pin "2") (pinfunction "2_2") (pintype "passive"))
      (node (ref "R43") (pin "2") (pinfunction "2_2") (pintype "passive"))
      (node (ref "R44") (pin "2") (pinfunction "2_2") (pintype "passive"))
      (node (ref "R45") (pin "2") (pinfunction "2_2") (pintype "passive"))
      (node (ref "R46") (pin "2") (pinfunction "2_2") (pintype "passive"))
      (node (ref "R47") (pin "2") (pinfunction "2_2") (pintype "passive"))
      (node (ref "R48") (pin "2") (pinfunction "2_2") (pintype "passive"))
      (node (ref "R49") (pin "2") (pinfunction "2_2") (pintype "passive"))
      (node (ref "R5") (pin "2") (pinfunction "2_2") (pintype "passive"))
      (node (ref "R50") (pin "2") (pinfunction "2_2") (pintype "passive"))
      (node (ref "R51") (pin "2") (pinfunction "2_2") (pintype "passive"))
      (node (ref "R52") (pin "2") (pinfunction "2_2") (pintype "passive"))
      (node (ref "R53") (pin "2") (pinfunction "2_2") (pintype "passive"))
      (node (ref "R54") (pin "2") (pinfunction "2_2") (pintype "passive"))
      (node (ref "R55") (pin "2") (pinfunction "2_2") (pintype "passive"))
      (node (ref "R56") (pin "2") (pinfunction "2_2") (pintype "passive"))
      (node (ref "R57") (pin "2") (pinfunction "2_2") (pintype "passive"))
      (node (ref "R58") (pin "2") (pinfunction "2_2") (pintype "passive"))
      (node (ref "R59") (pin "2") (pinfunction "2_2") (pintype "passive"))
      (node (ref "R6") (pin "2") (pinfunction "2_2") (pintype "passive"))
      (node (ref "R60") (pin "2") (pinfunction "2_2") (pintype "passive"))
      (node (ref "R61") (pin "2") (pinfunction "2_2") (pintype "passive"))
      (node (ref "R62") (pin "2") (pinfunction "2_2") (pintype "passive"))
      (node (ref "R63") (pin "2") (pinfunction "2_2") (pintype "passive"))
      (node (ref "R64") (pin "2") (pinfunction "2_2") (pintype "passive"))
      (node (ref "R65") (pin "2") (pinfunction "2_2") (pintype "passive"))
      (node (ref "R66") (pin "2") (pinfunction "2_2") (pintype "passive"))
      (node (ref "R67") (pin "2") (pinfunction "2_2") (pintype "passive"))
      (node (ref "R68") (pin "2") (pinfunction "2_2") (pintype "passive"))
      (node (ref "R69") (pin "2") (pinfunction "2_2") (pintype "passive"))
      (node (ref "R70") (pin "2") (pinfunction "2_2") (pintype "passive"))
      (node (ref "R71") (pin "2") (pinfunction "2_2") (pintype "passive"))
      (node (ref "R72") (pin "2") (pinfunction "2_2") (pintype "passive"))
      (node (ref "R73") (pin "2") (pinfunction "2_2") (pintype "passive"))
      (node (ref "R74") (pin "2") (pinfunction "2_2") (pintype "passive"))
      (node (ref "R75") (pin "2") (pinfunction "2_2") (pintype "passive"))
      (node (ref "R76") (pin "2") (pinfunction "2_2") (pintype "passive"))
      (node (ref "R77") (pin "2") (pinfunction "2_2") (pintype "passive"))
      (node (ref "R78") (pin "2") (pinfunction "2_2") (pintype "passive"))
      (node (ref "R79") (pin "2") (pinfunction "2_2") (pintype "passive"))
      (node (ref "R8") (pin "2") (pinfunction "2_2") (pintype "passive"))
      (node (ref "R80") (pin "2") (pinfunction "2_2") (pintype "passive"))
      (node (ref "R81") (pin "2") (pinfunction "2_2") (pintype "passive"))
      (node (ref "R82") (pin "2") (pinfunction "2_2") (pintype "passive"))
      (node (ref "R83") (pin "2") (pinfunction "2_2") (pintype "passive"))
      (node (ref "R84") (pin "2") (pinfunction "2_2") (pintype "passive"))
      (node (ref "R85") (pin "2") (pinfunction "2_2") (pintype "passive"))
      (node (ref "R86") (pin "2") (pinfunction "2_2") (pintype "passive"))
      (node (ref "R87") (pin "2") (pinfunction "2_2") (pintype "passive"))
      (node (ref "R88") (pin "2") (pinfunction "2_2") (pintype "passive"))
      (node (ref "R89") (pin "2") (pinfunction "2_2") (pintype "passive"))
      (node (ref "R9") (pin "2") (pinfunction "2_2") (pintype "passive"))
      (node (ref "R90") (pin "2") (pinfunction "2_2") (pintype "passive"))
      (node (ref "R91") (pin "2") (pinfunction "2_2") (pintype "passive"))
      (node (ref "R92") (pin "2") (pinfunction "2_2") (pintype "passive"))
      (node (ref "R93") (pin "2") (pinfunction "2_2") (pintype "passive"))
      (node (ref "R94") (pin "2") (pinfunction "2_2") (pintype "passive"))
      (node (ref "R95") (pin "2") (pinfunction "2_2") (pintype "passive"))
      (node (ref "R96") (pin "2") (pinfunction "2_2") (pintype "passive"))
      (node (ref "R97") (pin "2") (pinfunction "2_2") (pintype "passive"))
      (node (ref "R98") (pin "2") (pinfunction "2_2") (pintype "passive"))
      (node (ref "R99") (pin "2") (pinfunction "2_2") (pintype "passive"))
      (node (ref "U1") (pin "22") (pinfunction "GND_22") (pintype "bidirectional"))
      (node (ref "U1") (pin "8") (pinfunction "GND_8") (pintype "bidirectional"))
    )
    (net (code "126") (name "/GREEN") (class "Default")
      (node (ref "JP2") (pin "8") (pinfunction "8_8") (pintype "passive"))
      (node (ref "U1") (pin "11") (pinfunction "PD5(T1)_11") (pintype "bidirectional"))
    )
    (net (code "127") (name "/LED00") (class "Default")
      (node (ref "CELL0") (pin "4") (pinfunction "4_4") (pintype "passive"))
      (node (ref "IC13") (pin "5") (pinfunction "OUT0_5") (pintype "open_collector"))
    )
    (net (code "128") (name "/LED01") (class "Default")
      (node (ref "CELL1") (pin "4") (pinfunction "4_4") (pintype "passive"))
      (node (ref "IC13") (pin "6") (pinfunction "OUT1_6") (pintype "open_collector"))
    )
    (net (code "129") (name "/LED02") (class "Default")
      (node (ref "CELL2") (pin "4") (pinfunction "4_4") (pintype "passive"))
      (node (ref "IC13") (pin "7") (pinfunction "OUT2_7") (pintype "open_collector"))
    )
    (net (code "130") (name "/LED03") (class "Default")
      (node (ref "CELL3") (pin "4") (pinfunction "4_4") (pintype "passive"))
      (node (ref "IC13") (pin "8") (pinfunction "OUT3_8") (pintype "open_collector"))
    )
    (net (code "131") (name "/LED04") (class "Default")
      (node (ref "CELL4") (pin "4") (pinfunction "4_4") (pintype "passive"))
      (node (ref "IC13") (pin "9") (pinfunction "OUT4_9") (pintype "open_collector"))
    )
    (net (code "132") (name "/LED05") (class "Default")
      (node (ref "CELL5") (pin "4") (pinfunction "4_4") (pintype "passive"))
      (node (ref "IC13") (pin "10") (pinfunction "OUT5_10") (pintype "open_collector"))
    )
    (net (code "133") (name "/LED06") (class "Default")
      (node (ref "CELL6") (pin "4") (pinfunction "4_4") (pintype "passive"))
      (node (ref "IC13") (pin "11") (pinfunction "OUT6_11") (pintype "open_collector"))
    )
    (net (code "134") (name "/LED07") (class "Default")
      (node (ref "CELL7") (pin "4") (pinfunction "4_4") (pintype "passive"))
      (node (ref "IC13") (pin "12") (pinfunction "OUT7_12") (pintype "open_collector"))
    )
    (net (code "135") (name "/LED08") (class "Default")
      (node (ref "CELL8") (pin "4") (pinfunction "4_4") (pintype "passive"))
      (node (ref "IC13") (pin "13") (pinfunction "OUT8_13") (pintype "open_collector"))
    )
    (net (code "136") (name "/LED09") (class "Default")
      (node (ref "CELL9") (pin "4") (pinfunction "4_4") (pintype "passive"))
      (node (ref "IC13") (pin "14") (pinfunction "OUT9_14") (pintype "open_collector"))
    )
    (net (code "137") (name "/LED10") (class "Default")
      (node (ref "CELL10") (pin "4") (pinfunction "4_4") (pintype "passive"))
      (node (ref "IC13") (pin "15") (pinfunction "OUT10_15") (pintype "open_collector"))
    )
    (net (code "138") (name "/LED11") (class "Default")
      (node (ref "CELL11") (pin "4") (pinfunction "4_4") (pintype "passive"))
      (node (ref "IC13") (pin "16") (pinfunction "OUT11_16") (pintype "open_collector"))
    )
    (net (code "139") (name "/LED12") (class "Default")
      (node (ref "CELL12") (pin "4") (pinfunction "4_4") (pintype "passive"))
      (node (ref "IC13") (pin "17") (pinfunction "OUT12_17") (pintype "open_collector"))
    )
    (net (code "140") (name "/LED13") (class "Default")
      (node (ref "CELL13") (pin "4") (pinfunction "4_4") (pintype "passive"))
      (node (ref "IC13") (pin "18") (pinfunction "OUT13_18") (pintype "open_collector"))
    )
    (net (code "141") (name "/LED14") (class "Default")
      (node (ref "CELL14") (pin "4") (pinfunction "4_4") (pintype "passive"))
      (node (ref "IC13") (pin "19") (pinfunction "OUT14_19") (pintype "open_collector"))
    )
    (net (code "142") (name "/LED15") (class "Default")
      (node (ref "CELL15") (pin "4") (pinfunction "4_4") (pintype "passive"))
      (node (ref "IC13") (pin "20") (pinfunction "OUT15_20") (pintype "open_collector"))
    )
    (net (code "143") (name "/LED16") (class "Default")
      (node (ref "CELL16") (pin "4") (pinfunction "4_4") (pintype "passive"))
      (node (ref "IC13") (pin "21") (pinfunction "OUT16_21") (pintype "open_collector"))
    )
    (net (code "144") (name "/LED17") (class "Default")
      (node (ref "CELL17") (pin "4") (pinfunction "4_4") (pintype "passive"))
      (node (ref "IC13") (pin "22") (pinfunction "OUT17_22") (pintype "open_collector"))
    )
    (net (code "145") (name "/LED18") (class "Default")
      (node (ref "CELL18") (pin "4") (pinfunction "4_4") (pintype "passive"))
      (node (ref "IC13") (pin "23") (pinfunction "OUT18_23") (pintype "open_collector"))
    )
    (net (code "146") (name "/LED19") (class "Default")
      (node (ref "CELL19") (pin "4") (pinfunction "4_4") (pintype "passive"))
      (node (ref "IC13") (pin "24") (pinfunction "OUT19_24") (pintype "open_collector"))
    )
    (net (code "147") (name "/LED20") (class "Default")
      (node (ref "CELL20") (pin "4") (pinfunction "4_4") (pintype "passive"))
      (node (ref "IC13") (pin "25") (pinfunction "OUT20_25") (pintype "open_collector"))
    )
    (net (code "148") (name "/LED21") (class "Default")
      (node (ref "CELL21") (pin "4") (pinfunction "4_4") (pintype "passive"))
      (node (ref "IC13") (pin "26") (pinfunction "OUT21_26") (pintype "open_collector"))
    )
    (net (code "149") (name "/LED22") (class "Default")
      (node (ref "CELL22") (pin "4") (pinfunction "4_4") (pintype "passive"))
      (node (ref "IC13") (pin "27") (pinfunction "OUT22_27") (pintype "open_collector"))
    )
    (net (code "150") (name "/LED23") (class "Default")
      (node (ref "CELL23") (pin "4") (pinfunction "4_4") (pintype "passive"))
      (node (ref "IC13") (pin "28") (pinfunction "OUT23_28") (pintype "open_collector"))
    )
    (net (code "151") (name "/LED24") (class "Default")
      (node (ref "CELL24") (pin "4") (pinfunction "4_4") (pintype "passive"))
      (node (ref "IC14") (pin "5") (pinfunction "OUT0_5") (pintype "open_collector"))
    )
    (net (code "152") (name "/LED25") (class "Default")
      (node (ref "CELL25") (pin "4") (pinfunction "4_4") (pintype "passive"))
      (node (ref "IC14") (pin "6") (pinfunction "OUT1_6") (pintype "open_collector"))
    )
    (net (code "153") (name "/LED26") (class "Default")
      (node (ref "CELL26") (pin "4") (pinfunction "4_4") (pintype "passive"))
      (node (ref "IC14") (pin "7") (pinfunction "OUT2_7") (pintype "open_collector"))
    )
    (net (code "154") (name "/LED27") (class "Default")
      (node (ref "CELL27") (pin "4") (pinfunction "4_4") (pintype "passive"))
      (node (ref "IC14") (pin "8") (pinfunction "OUT3_8") (pintype "open_collector"))
    )
    (net (code "155") (name "/LED28") (class "Default")
      (node (ref "CELL28") (pin "4") (pinfunction "4_4") (pintype "passive"))
      (node (ref "IC14") (pin "9") (pinfunction "OUT4_9") (pintype "open_collector"))
    )
    (net (code "156") (name "/LED29") (class "Default")
      (node (ref "CELL29") (pin "4") (pinfunction "4_4") (pintype "passive"))
      (node (ref "IC14") (pin "10") (pinfunction "OUT5_10") (pintype "open_collector"))
    )
    (net (code "157") (name "/LED30") (class "Default")
      (node (ref "CELL30") (pin "4") (pinfunction "4_4") (pintype "passive"))
      (node (ref "IC14") (pin "11") (pinfunction "OUT6_11") (pintype "open_collector"))
    )
    (net (code "158") (name "/LED31") (class "Default")
      (node (ref "CELL31") (pin "4") (pinfunction "4_4") (pintype "passive"))
      (node (ref "IC14") (pin "12") (pinfunction "OUT7_12") (pintype "open_collector"))
    )
    (net (code "159") (name "/LED32") (class "Default")
      (node (ref "CELL32") (pin "4") (pinfunction "4_4") (pintype "passive"))
      (node (ref "IC14") (pin "13") (pinfunction "OUT8_13") (pintype "open_collector"))
    )
    (net (code "160") (name "/LED33") (class "Default")
      (node (ref "CELL33") (pin "4") (pinfunction "4_4") (pintype "passive"))
      (node (ref "IC14") (pin "14") (pinfunction "OUT9_14") (pintype "open_collector"))
    )
    (net (code "161") (name "/LED34") (class "Default")
      (node (ref "CELL34") (pin "4") (pinfunction "4_4") (pintype "passive"))
      (node (ref "IC14") (pin "15") (pinfunction "OUT10_15") (pintype "open_collector"))
    )
    (net (code "162") (name "/LED35") (class "Default")
      (node (ref "CELL35") (pin "4") (pinfunction "4_4") (pintype "passive"))
      (node (ref "IC14") (pin "16") (pinfunction "OUT11_16") (pintype "open_collector"))
    )
    (net (code "163") (name "/LED36") (class "Default")
      (node (ref "CELL36") (pin "4") (pinfunction "4_4") (pintype "passive"))
      (node (ref "IC14") (pin "17") (pinfunction "OUT12_17") (pintype "open_collector"))
    )
    (net (code "164") (name "/LED37") (class "Default")
      (node (ref "CELL37") (pin "4") (pinfunction "4_4") (pintype "passive"))
      (node (ref "IC14") (pin "18") (pinfunction "OUT13_18") (pintype "open_collector"))
    )
    (net (code "165") (name "/LED38") (class "Default")
      (node (ref "CELL38") (pin "4") (pinfunction "4_4") (pintype "passive"))
      (node (ref "IC14") (pin "19") (pinfunction "OUT14_19") (pintype "open_collector"))
    )
    (net (code "166") (name "/LED39") (class "Default")
      (node (ref "CELL39") (pin "4") (pinfunction "4_4") (pintype "passive"))
      (node (ref "IC14") (pin "20") (pinfunction "OUT15_20") (pintype "open_collector"))
    )
    (net (code "167") (name "/LED40") (class "Default")
      (node (ref "CELL40") (pin "4") (pinfunction "4_4") (pintype "passive"))
      (node (ref "IC14") (pin "21") (pinfunction "OUT16_21") (pintype "open_collector"))
    )
    (net (code "168") (name "/LED41") (class "Default")
      (node (ref "CELL41") (pin "4") (pinfunction "4_4") (pintype "passive"))
      (node (ref "IC14") (pin "22") (pinfunction "OUT17_22") (pintype "open_collector"))
    )
    (net (code "169") (name "/LED42") (class "Default")
      (node (ref "CELL42") (pin "4") (pinfunction "4_4") (pintype "passive"))
      (node (ref "IC14") (pin "23") (pinfunction "OUT18_23") (pintype "open_collector"))
    )
    (net (code "170") (name "/LED43") (class "Default")
      (node (ref "CELL43") (pin "4") (pinfunction "4_4") (pintype "passive"))
      (node (ref "IC14") (pin "24") (pinfunction "OUT19_24") (pintype "open_collector"))
    )
    (net (code "171") (name "/LED44") (class "Default")
      (node (ref "CELL44") (pin "4") (pinfunction "4_4") (pintype "passive"))
      (node (ref "IC14") (pin "25") (pinfunction "OUT20_25") (pintype "open_collector"))
    )
    (net (code "172") (name "/LED45") (class "Default")
      (node (ref "CELL45") (pin "4") (pinfunction "4_4") (pintype "passive"))
      (node (ref "IC14") (pin "26") (pinfunction "OUT21_26") (pintype "open_collector"))
    )
    (net (code "173") (name "/LED46") (class "Default")
      (node (ref "CELL46") (pin "4") (pinfunction "4_4") (pintype "passive"))
      (node (ref "IC14") (pin "27") (pinfunction "OUT22_27") (pintype "open_collector"))
    )
    (net (code "174") (name "/LED47") (class "Default")
      (node (ref "CELL47") (pin "4") (pinfunction "4_4") (pintype "passive"))
      (node (ref "IC14") (pin "28") (pinfunction "OUT23_28") (pintype "open_collector"))
    )
    (net (code "175") (name "/LED48") (class "Default")
      (node (ref "CELL48") (pin "4") (pinfunction "4_4") (pintype "passive"))
      (node (ref "IC15") (pin "5") (pinfunction "OUT0_5") (pintype "open_collector"))
    )
    (net (code "176") (name "/LED49") (class "Default")
      (node (ref "CELL49") (pin "4") (pinfunction "4_4") (pintype "passive"))
      (node (ref "IC15") (pin "6") (pinfunction "OUT1_6") (pintype "open_collector"))
    )
    (net (code "177") (name "/LED50") (class "Default")
      (node (ref "CELL50") (pin "4") (pinfunction "4_4") (pintype "passive"))
      (node (ref "IC15") (pin "7") (pinfunction "OUT2_7") (pintype "open_collector"))
    )
    (net (code "178") (name "/LED51") (class "Default")
      (node (ref "CELL51") (pin "4") (pinfunction "4_4") (pintype "passive"))
      (node (ref "IC15") (pin "8") (pinfunction "OUT3_8") (pintype "open_collector"))
    )
    (net (code "179") (name "/LED52") (class "Default")
      (node (ref "CELL52") (pin "4") (pinfunction "4_4") (pintype "passive"))
      (node (ref "IC15") (pin "9") (pinfunction "OUT4_9") (pintype "open_collector"))
    )
    (net (code "180") (name "/LED53") (class "Default")
      (node (ref "CELL53") (pin "4") (pinfunction "4_4") (pintype "passive"))
      (node (ref "IC15") (pin "10") (pinfunction "OUT5_10") (pintype "open_collector"))
    )
    (net (code "181") (name "/LED54") (class "Default")
      (node (ref "CELL54") (pin "4") (pinfunction "4_4") (pintype "passive"))
      (node (ref "IC15") (pin "11") (pinfunction "OUT6_11") (pintype "open_collector"))
    )
    (net (code "182") (name "/LED55") (class "Default")
      (node (ref "CELL55") (pin "4") (pinfunction "4_4") (pintype "passive"))
      (node (ref "IC15") (pin "12") (pinfunction "OUT7_12") (pintype "open_collector"))
    )
    (net (code "183") (name "/LED56") (class "Default")
      (node (ref "CELL56") (pin "4") (pinfunction "4_4") (pintype "passive"))
      (node (ref "IC15") (pin "13") (pinfunction "OUT8_13") (pintype "open_collector"))
    )
    (net (code "184") (name "/LED57") (class "Default")
      (node (ref "CELL57") (pin "4") (pinfunction "4_4") (pintype "passive"))
      (node (ref "IC15") (pin "14") (pinfunction "OUT9_14") (pintype "open_collector"))
    )
    (net (code "185") (name "/LED58") (class "Default")
      (node (ref "CELL58") (pin "4") (pinfunction "4_4") (pintype "passive"))
      (node (ref "IC15") (pin "15") (pinfunction "OUT10_15") (pintype "open_collector"))
    )
    (net (code "186") (name "/LED59") (class "Default")
      (node (ref "CELL59") (pin "4") (pinfunction "4_4") (pintype "passive"))
      (node (ref "IC15") (pin "16") (pinfunction "OUT11_16") (pintype "open_collector"))
    )
    (net (code "187") (name "/LED60") (class "Default")
      (node (ref "CELL60") (pin "4") (pinfunction "4_4") (pintype "passive"))
      (node (ref "IC15") (pin "17") (pinfunction "OUT12_17") (pintype "open_collector"))
    )
    (net (code "188") (name "/LED61") (class "Default")
      (node (ref "CELL61") (pin "4") (pinfunction "4_4") (pintype "passive"))
      (node (ref "IC15") (pin "18") (pinfunction "OUT13_18") (pintype "open_collector"))
    )
    (net (code "189") (name "/LED62") (class "Default")
      (node (ref "CELL62") (pin "4") (pinfunction "4_4") (pintype "passive"))
      (node (ref "IC15") (pin "19") (pinfunction "OUT14_19") (pintype "open_collector"))
    )
    (net (code "190") (name "/LED63") (class "Default")
      (node (ref "CELL63") (pin "4") (pinfunction "4_4") (pintype "passive"))
      (node (ref "IC15") (pin "20") (pinfunction "OUT15_20") (pintype "open_collector"))
    )
    (net (code "191") (name "/LED64") (class "Default")
      (node (ref "CELL64") (pin "4") (pinfunction "4_4") (pintype "passive"))
      (node (ref "IC15") (pin "21") (pinfunction "OUT16_21") (pintype "open_collector"))
    )
    (net (code "192") (name "/LED65") (class "Default")
      (node (ref "CELL65") (pin "4") (pinfunction "4_4") (pintype "passive"))
      (node (ref "IC15") (pin "22") (pinfunction "OUT17_22") (pintype "open_collector"))
    )
    (net (code "193") (name "/LED66") (class "Default")
      (node (ref "CELL66") (pin "4") (pinfunction "4_4") (pintype "passive"))
      (node (ref "IC15") (pin "23") (pinfunction "OUT18_23") (pintype "open_collector"))
    )
    (net (code "194") (name "/LED67") (class "Default")
      (node (ref "CELL67") (pin "4") (pinfunction "4_4") (pintype "passive"))
      (node (ref "IC15") (pin "24") (pinfunction "OUT19_24") (pintype "open_collector"))
    )
    (net (code "195") (name "/LED68") (class "Default")
      (node (ref "CELL68") (pin "4") (pinfunction "4_4") (pintype "passive"))
      (node (ref "IC15") (pin "25") (pinfunction "OUT20_25") (pintype "open_collector"))
    )
    (net (code "196") (name "/LED69") (class "Default")
      (node (ref "CELL69") (pin "4") (pinfunction "4_4") (pintype "passive"))
      (node (ref "IC15") (pin "26") (pinfunction "OUT21_26") (pintype "open_collector"))
    )
    (net (code "197") (name "/LED70") (class "Default")
      (node (ref "CELL70") (pin "4") (pinfunction "4_4") (pintype "passive"))
      (node (ref "IC15") (pin "27") (pinfunction "OUT22_27") (pintype "open_collector"))
    )
    (net (code "198") (name "/LED71") (class "Default")
      (node (ref "CELL71") (pin "4") (pinfunction "4_4") (pintype "passive"))
      (node (ref "IC15") (pin "28") (pinfunction "OUT23_28") (pintype "open_collector"))
    )
    (net (code "199") (name "/LED72") (class "Default")
      (node (ref "CELL72") (pin "4") (pinfunction "4_4") (pintype "passive"))
      (node (ref "IC16") (pin "5") (pinfunction "OUT0_5") (pintype "open_collector"))
    )
    (net (code "200") (name "/LED73") (class "Default")
      (node (ref "CELL73") (pin "4") (pinfunction "4_4") (pintype "passive"))
      (node (ref "IC16") (pin "6") (pinfunction "OUT1_6") (pintype "open_collector"))
    )
    (net (code "201") (name "/LED74") (class "Default")
      (node (ref "CELL74") (pin "4") (pinfunction "4_4") (pintype "passive"))
      (node (ref "IC16") (pin "7") (pinfunction "OUT2_7") (pintype "open_collector"))
    )
    (net (code "202") (name "/LED75") (class "Default")
      (node (ref "CELL75") (pin "4") (pinfunction "4_4") (pintype "passive"))
      (node (ref "IC16") (pin "8") (pinfunction "OUT3_8") (pintype "open_collector"))
    )
    (net (code "203") (name "/LED76") (class "Default")
      (node (ref "CELL76") (pin "4") (pinfunction "4_4") (pintype "passive"))
      (node (ref "IC16") (pin "9") (pinfunction "OUT4_9") (pintype "open_collector"))
    )
    (net (code "204") (name "/LED77") (class "Default")
      (node (ref "CELL77") (pin "4") (pinfunction "4_4") (pintype "passive"))
      (node (ref "IC16") (pin "10") (pinfunction "OUT5_10") (pintype "open_collector"))
    )
    (net (code "205") (name "/LED78") (class "Default")
      (node (ref "CELL78") (pin "4") (pinfunction "4_4") (pintype "passive"))
      (node (ref "IC16") (pin "11") (pinfunction "OUT6_11") (pintype "open_collector"))
    )
    (net (code "206") (name "/LED79") (class "Default")
      (node (ref "CELL79") (pin "4") (pinfunction "4_4") (pintype "passive"))
      (node (ref "IC16") (pin "12") (pinfunction "OUT7_12") (pintype "open_collector"))
    )
    (net (code "207") (name "/LED80") (class "Default")
      (node (ref "CELL80") (pin "4") (pinfunction "4_4") (pintype "passive"))
      (node (ref "IC16") (pin "13") (pinfunction "OUT8_13") (pintype "open_collector"))
    )
    (net (code "208") (name "/LED81") (class "Default")
      (node (ref "CELL81") (pin "4") (pinfunction "4_4") (pintype "passive"))
      (node (ref "IC16") (pin "14") (pinfunction "OUT9_14") (pintype "open_collector"))
    )
    (net (code "209") (name "/LED82") (class "Default")
      (node (ref "CELL82") (pin "4") (pinfunction "4_4") (pintype "passive"))
      (node (ref "IC16") (pin "15") (pinfunction "OUT10_15") (pintype "open_collector"))
    )
    (net (code "210") (name "/LED83") (class "Default")
      (node (ref "CELL83") (pin "4") (pinfunction "4_4") (pintype "passive"))
      (node (ref "IC16") (pin "16") (pinfunction "OUT11_16") (pintype "open_collector"))
    )
    (net (code "211") (name "/LED84") (class "Default")
      (node (ref "CELL84") (pin "4") (pinfunction "4_4") (pintype "passive"))
      (node (ref "IC16") (pin "17") (pinfunction "OUT12_17") (pintype "open_collector"))
    )
    (net (code "212") (name "/LED85") (class "Default")
      (node (ref "CELL85") (pin "4") (pinfunction "4_4") (pintype "passive"))
      (node (ref "IC16") (pin "18") (pinfunction "OUT13_18") (pintype "open_collector"))
    )
    (net (code "213") (name "/LED86") (class "Default")
      (node (ref "CELL86") (pin "4") (pinfunction "4_4") (pintype "passive"))
      (node (ref "IC16") (pin "19") (pinfunction "OUT14_19") (pintype "open_collector"))
    )
    (net (code "214") (name "/LED87") (class "Default")
      (node (ref "CELL87") (pin "4") (pinfunction "4_4") (pintype "passive"))
      (node (ref "IC16") (pin "20") (pinfunction "OUT15_20") (pintype "open_collector"))
    )
    (net (code "215") (name "/LED88") (class "Default")
      (node (ref "CELL88") (pin "4") (pinfunction "4_4") (pintype "passive"))
      (node (ref "IC16") (pin "21") (pinfunction "OUT16_21") (pintype "open_collector"))
    )
    (net (code "216") (name "/LED89") (class "Default")
      (node (ref "CELL89") (pin "4") (pinfunction "4_4") (pintype "passive"))
      (node (ref "IC16") (pin "22") (pinfunction "OUT17_22") (pintype "open_collector"))
    )
    (net (code "217") (name "/LED90") (class "Default")
      (node (ref "CELL90") (pin "4") (pinfunction "4_4") (pintype "passive"))
      (node (ref "IC16") (pin "23") (pinfunction "OUT18_23") (pintype "open_collector"))
    )
    (net (code "218") (name "/LED91") (class "Default")
      (node (ref "CELL91") (pin "4") (pinfunction "4_4") (pintype "passive"))
      (node (ref "IC16") (pin "24") (pinfunction "OUT19_24") (pintype "open_collector"))
    )
    (net (code "219") (name "/LED92") (class "Default")
      (node (ref "CELL92") (pin "4") (pinfunction "4_4") (pintype "passive"))
      (node (ref "IC16") (pin "25") (pinfunction "OUT20_25") (pintype "open_collector"))
    )
    (net (code "220") (name "/LED93") (class "Default")
      (node (ref "CELL93") (pin "4") (pinfunction "4_4") (pintype "passive"))
      (node (ref "IC16") (pin "26") (pinfunction "OUT21_26") (pintype "open_collector"))
    )
    (net (code "221") (name "/LED94") (class "Default")
      (node (ref "CELL94") (pin "4") (pinfunction "4_4") (pintype "passive"))
      (node (ref "IC16") (pin "27") (pinfunction "OUT22_27") (pintype "open_collector"))
    )
    (net (code "222") (name "/LED95") (class "Default")
      (node (ref "CELL95") (pin "4") (pinfunction "4_4") (pintype "passive"))
      (node (ref "IC16") (pin "28") (pinfunction "OUT23_28") (pintype "open_collector"))
    )
    (net (code "223") (name "/LED96") (class "Default")
      (node (ref "CELL96") (pin "4") (pinfunction "4_4") (pintype "passive"))
      (node (ref "IC17") (pin "5") (pinfunction "OUT0_5") (pintype "open_collector"))
    )
    (net (code "224") (name "/LED97") (class "Default")
      (node (ref "CELL97") (pin "4") (pinfunction "4_4") (pintype "passive"))
      (node (ref "IC17") (pin "6") (pinfunction "OUT1_6") (pintype "open_collector"))
    )
    (net (code "225") (name "/LED98") (class "Default")
      (node (ref "CELL98") (pin "4") (pinfunction "4_4") (pintype "passive"))
      (node (ref "IC17") (pin "7") (pinfunction "OUT2_7") (pintype "open_collector"))
    )
    (net (code "226") (name "/LED99") (class "Default")
      (node (ref "CELL99") (pin "4") (pinfunction "4_4") (pintype "passive"))
      (node (ref "IC17") (pin "8") (pinfunction "OUT3_8") (pintype "open_collector"))
    )
    (net (code "227") (name "/LED100") (class "Default")
      (node (ref "CELL100") (pin "4") (pinfunction "4_4") (pintype "passive"))
      (node (ref "IC17") (pin "9") (pinfunction "OUT4_9") (pintype "open_collector"))
    )
    (net (code "228") (name "/LED101") (class "Default")
      (node (ref "CELL101") (pin "4") (pinfunction "4_4") (pintype "passive"))
      (node (ref "IC17") (pin "10") (pinfunction "OUT5_10") (pintype "open_collector"))
    )
    (net (code "229") (name "/LED102") (class "Default")
      (node (ref "CELL102") (pin "4") (pinfunction "4_4") (pintype "passive"))
      (node (ref "IC17") (pin "11") (pinfunction "OUT6_11") (pintype "open_collector"))
    )
    (net (code "230") (name "/LED103") (class "Default")
      (node (ref "CELL103") (pin "4") (pinfunction "4_4") (pintype "passive"))
      (node (ref "IC17") (pin "12") (pinfunction "OUT7_12") (pintype "open_collector"))
    )
    (net (code "231") (name "/LED_BLANK") (class "Default")
      (node (ref "IC13") (pin "2") (pinfunction "BLANK_2") (pintype "input"))
      (node (ref "IC14") (pin "2") (pinfunction "BLANK_2") (pintype "input"))
      (node (ref "IC15") (pin "2") (pinfunction "BLANK_2") (pintype "input"))
      (node (ref "IC16") (pin "2") (pinfunction "BLANK_2") (pintype "input"))
      (node (ref "IC17") (pin "2") (pinfunction "BLANK_2") (pintype "input"))
      (node (ref "R7") (pin "2") (pinfunction "2_2") (pintype "passive"))
      (node (ref "U1") (pin "24") (pinfunction "PC1(ADC1)_24") (pintype "bidirectional"))
    )
    (net (code "232") (name "/LED_CLK") (class "Default")
      (node (ref "IC13") (pin "3") (pinfunction "SCLK_3") (pintype "input"))
      (node (ref "IC14") (pin "3") (pinfunction "SCLK_3") (pintype "input"))
      (node (ref "IC15") (pin "3") (pinfunction "SCLK_3") (pintype "input"))
      (node (ref "IC16") (pin "3") (pinfunction "SCLK_3") (pintype "input"))
      (node (ref "IC17") (pin "3") (pinfunction "SCLK_3") (pintype "input"))
      (node (ref "U1") (pin "25") (pinfunction "PC2(ADC2)_25") (pintype "bidirectional"))
    )
    (net (code "233") (name "/LED_LATCH") (class "Default")
      (node (ref "IC13") (pin "30") (pinfunction "XLAT_30") (pintype "input"))
      (node (ref "IC14") (pin "30") (pinfunction "XLAT_30") (pintype "input"))
      (node (ref "IC15") (pin "30") (pinfunction "XLAT_30") (pintype "input"))
      (node (ref "IC16") (pin "30") (pinfunction "XLAT_30") (pintype "input"))
      (node (ref "IC17") (pin "30") (pinfunction "XLAT_30") (pintype "input"))
      (node (ref "U1") (pin "23") (pinfunction "PC0(ADC0)_23") (pintype "bidirectional"))
    )
    (net (code "234") (name "/LED_SIN") (class "Default")
      (node (ref "IC13") (pin "4") (pinfunction "SIN_4") (pintype "input"))
      (node (ref "U1") (pin "26") (pinfunction "PC3(ADC3)_26") (pintype "bidirectional"))
    )
    (net (code "235") (name "/LUX00") (class "Default")
      (node (ref "CELL0") (pin "3") (pinfunction "3_3") (pintype "passive"))
      (node (ref "IC1") (pin "1") (pinfunction "CH0_1") (pintype "input"))
      (node (ref "R8") (pin "1") (pinfunction "1_1") (pintype "passive"))
    )
    (net (code "236") (name "/LUX01") (class "Default")
      (node (ref "CELL1") (pin "3") (pinfunction "3_3") (pintype "passive"))
      (node (ref "IC1") (pin "2") (pinfunction "CH1_2") (pintype "input"))
      (node (ref "R9") (pin "1") (pinfunction "1_1") (pintype "passive"))
    )
    (net (code "237") (name "/LUX02") (class "Default")
      (node (ref "CELL2") (pin "3") (pinfunction "3_3") (pintype "passive"))
      (node (ref "IC1") (pin "3") (pinfunction "CH2_3") (pintype "input"))
      (node (ref "R10") (pin "1") (pinfunction "1_1") (pintype "passive"))
    )
    (net (code "238") (name "/LUX03") (class "Default")
      (node (ref "CELL3") (pin "3") (pinfunction "3_3") (pintype "passive"))
      (node (ref "IC1") (pin "4") (pinfunction "CH3_4") (pintype "input"))
      (node (ref "R11") (pin "1") (pinfunction "1_1") (pintype "passive"))
    )
    (net (code "239") (name "/LUX04") (class "Default")
      (node (ref "CELL4") (pin "3") (pinfunction "3_3") (pintype "passive"))
      (node (ref "IC1") (pin "5") (pinfunction "CH4_5") (pintype "input"))
      (node (ref "R12") (pin "1") (pinfunction "1_1") (pintype "passive"))
    )
    (net (code "240") (name "/LUX05") (class "Default")
      (node (ref "CELL5") (pin "3") (pinfunction "3_3") (pintype "passive"))
      (node (ref "IC1") (pin "6") (pinfunction "CH5_6") (pintype "input"))
      (node (ref "R13") (pin "1") (pinfunction "1_1") (pintype "passive"))
    )
    (net (code "241") (name "/LUX06") (class "Default")
      (node (ref "CELL6") (pin "3") (pinfunction "3_3") (pintype "passive"))
      (node (ref "IC1") (pin "7") (pinfunction "CH6_7") (pintype "input"))
      (node (ref "R14") (pin "1") (pinfunction "1_1") (pintype "passive"))
    )
    (net (code "242") (name "/LUX07") (class "Default")
      (node (ref "CELL7") (pin "3") (pinfunction "3_3") (pintype "passive"))
      (node (ref "IC1") (pin "8") (pinfunction "CH7_8") (pintype "input"))
      (node (ref "R15") (pin "1") (pinfunction "1_1") (pintype "passive"))
    )
    (net (code "243") (name "/LUX08") (class "Default")
      (node (ref "CELL8") (pin "3") (pinfunction "3_3") (pintype "passive"))
      (node (ref "IC2") (pin "1") (pinfunction "CH0_1") (pintype "input"))
      (node (ref "R16") (pin "1") (pinfunction "1_1") (pintype "passive"))
    )
    (net (code "244") (name "/LUX09") (class "Default")
      (node (ref "CELL9") (pin "3") (pinfunction "3_3") (pintype "passive"))
      (node (ref "IC2") (pin "2") (pinfunction "CH1_2") (pintype "input"))
      (node (ref "R17") (pin "1") (pinfunction "1_1") (pintype "passive"))
    )
    (net (code "245") (name "/LUX10") (class "Default")
      (node (ref "CELL10") (pin "3") (pinfunction "3_3") (pintype "passive"))
      (node (ref "IC2") (pin "3") (pinfunction "CH2_3") (pintype "input"))
      (node (ref "R18") (pin "1") (pinfunction "1_1") (pintype "passive"))
    )
    (net (code "246") (name "/LUX11") (class "Default")
      (node (ref "CELL11") (pin "3") (pinfunction "3_3") (pintype "passive"))
      (node (ref "IC2") (pin "4") (pinfunction "CH3_4") (pintype "input"))
      (node (ref "R19") (pin "1") (pinfunction "1_1") (pintype "passive"))
    )
    (net (code "247") (name "/LUX12") (class "Default")
      (node (ref "CELL12") (pin "3") (pinfunction "3_3") (pintype "passive"))
      (node (ref "IC2") (pin "5") (pinfunction "CH4_5") (pintype "input"))
      (node (ref "R20") (pin "1") (pinfunction "1_1") (pintype "passive"))
    )
    (net (code "248") (name "/LUX13") (class "Default")
      (node (ref "CELL13") (pin "3") (pinfunction "3_3") (pintype "passive"))
      (node (ref "IC2") (pin "6") (pinfunction "CH5_6") (pintype "input"))
      (node (ref "R21") (pin "1") (pinfunction "1_1") (pintype "passive"))
    )
    (net (code "249") (name "/LUX14") (class "Default")
      (node (ref "CELL14") (pin "3") (pinfunction "3_3") (pintype "passive"))
      (node (ref "IC2") (pin "7") (pinfunction "CH6_7") (pintype "input"))
      (node (ref "R22") (pin "1") (pinfunction "1_1") (pintype "passive"))
    )
    (net (code "250") (name "/LUX15") (class "Default")
      (node (ref "CELL15") (pin "3") (pinfunction "3_3") (pintype "passive"))
      (node (ref "IC2") (pin "8") (pinfunction "CH7_8") (pintype "input"))
      (node (ref "R23") (pin "1") (pinfunction "1_1") (pintype "passive"))
    )
    (net (code "251") (name "/LUX16") (class "Default")
      (node (ref "CELL16") (pin "3") (pinfunction "3_3") (pintype "passive"))
      (node (ref "IC3") (pin "1") (pinfunction "CH0_1") (pintype "input"))
      (node (ref "R24") (pin "1") (pinfunction "1_1") (pintype "passive"))
    )
    (net (code "252") (name "/LUX17") (class "Default")
      (node (ref "CELL17") (pin "3") (pinfunction "3_3") (pintype "passive"))
      (node (ref "IC3") (pin "2") (pinfunction "CH1_2") (pintype "input"))
      (node (ref "R25") (pin "1") (pinfunction "1_1") (pintype "passive"))
    )
    (net (code "253") (name "/LUX18") (class "Default")
      (node (ref "CELL18") (pin "3") (pinfunction "3_3") (pintype "passive"))
      (node (ref "IC3") (pin "3") (pinfunction "CH2_3") (pintype "input"))
      (node (ref "R26") (pin "1") (pinfunction "1_1") (pintype "passive"))
    )
    (net (code "254") (name "/LUX19") (class "Default")
      (node (ref "CELL19") (pin "3") (pinfunction "3_3") (pintype "passive"))
      (node (ref "IC3") (pin "4") (pinfunction "CH3_4") (pintype "input"))
      (node (ref "R27") (pin "1") (pinfunction "1_1") (pintype "passive"))
    )
    (net (code "255") (name "/LUX20") (class "Default")
      (node (ref "CELL20") (pin "3") (pinfunction "3_3") (pintype "passive"))
      (node (ref "IC3") (pin "5") (pinfunction "CH4_5") (pintype "input"))
      (node (ref "R28") (pin "1") (pinfunction "1_1") (pintype "passive"))
    )
    (net (code "256") (name "/LUX21") (class "Default")
      (node (ref "CELL21") (pin "3") (pinfunction "3_3") (pintype "passive"))
      (node (ref "IC3") (pin "6") (pinfunction "CH5_6") (pintype "input"))
      (node (ref "R29") (pin "1") (pinfunction "1_1") (pintype "passive"))
    )
    (net (code "257") (name "/LUX22") (class "Default")
      (node (ref "CELL22") (pin "3") (pinfunction "3_3") (pintype "passive"))
      (node (ref "IC3") (pin "7") (pinfunction "CH6_7") (pintype "input"))
      (node (ref "R30") (pin "1") (pinfunction "1_1") (pintype "passive"))
    )
    (net (code "258") (name "/LUX23") (class "Default")
      (node (ref "CELL23") (pin "3") (pinfunction "3_3") (pintype "passive"))
      (node (ref "IC3") (pin "8") (pinfunction "CH7_8") (pintype "input"))
      (node (ref "R31") (pin "1") (pinfunction "1_1") (pintype "passive"))
    )
    (net (code "259") (name "/LUX24") (class "Default")
      (node (ref "CELL24") (pin "3") (pinfunction "3_3") (pintype "passive"))
      (node (ref "IC4") (pin "1") (pinfunction "CH0_1") (pintype "input"))
      (node (ref "R32") (pin "1") (pinfunction "1_1") (pintype "passive"))
    )
    (net (code "260") (name "/LUX25") (class "Default")
      (node (ref "CELL25") (pin "3") (pinfunction "3_3") (pintype "passive"))
      (node (ref "IC4") (pin "2") (pinfunction "CH1_2") (pintype "input"))
      (node (ref "R33") (pin "1") (pinfunction "1_1") (pintype "passive"))
    )
    (net (code "261") (name "/LUX26") (class "Default")
      (node (ref "CELL26") (pin "3") (pinfunction "3_3") (pintype "passive"))
      (node (ref "IC4") (pin "3") (pinfunction "CH2_3") (pintype "input"))
      (node (ref "R34") (pin "1") (pinfunction "1_1") (pintype "passive"))
    )
    (net (code "262") (name "/LUX27") (class "Default")
      (node (ref "CELL27") (pin "3") (pinfunction "3_3") (pintype "passive"))
      (node (ref "IC4") (pin "4") (pinfunction "CH3_4") (pintype "input"))
      (node (ref "R35") (pin "1") (pinfunction "1_1") (pintype "passive"))
    )
    (net (code "263") (name "/LUX28") (class "Default")
      (node (ref "CELL28") (pin "3") (pinfunction "3_3") (pintype "passive"))
      (node (ref "IC4") (pin "5") (pinfunction "CH4_5") (pintype "input"))
      (node (ref "R36") (pin "1") (pinfunction "1_1") (pintype "passive"))
    )
    (net (code "264") (name "/LUX29") (class "Default")
      (node (ref "CELL29") (pin "3") (pinfunction "3_3") (pintype "passive"))
      (node (ref "IC4") (pin "6") (pinfunction "CH5_6") (pintype "input"))
      (node (ref "R37") (pin "1") (pinfunction "1_1") (pintype "passive"))
    )
    (net (code "265") (name "/LUX30") (class "Default")
      (node (ref "CELL30") (pin "3") (pinfunction "3_3") (pintype "passive"))
      (node (ref "IC4") (pin "7") (pinfunction "CH6_7") (pintype "input"))
      (node (ref "R38") (pin "1") (pinfunction "1_1") (pintype "passive"))
    )
    (net (code "266") (name "/LUX31") (class "Default")
      (node (ref "CELL31") (pin "3") (pinfunction "3_3") (pintype "passive"))
      (node (ref "IC4") (pin "8") (pinfunction "CH7_8") (pintype "input"))
      (node (ref "R39") (pin "1") (pinfunction "1_1") (pintype "passive"))
    )
    (net (code "267") (name "/LUX32") (class "Default")
      (node (ref "CELL32") (pin "3") (pinfunction "3_3") (pintype "passive"))
      (node (ref "IC5") (pin "1") (pinfunction "CH0_1") (pintype "input"))
      (node (ref "R40") (pin "1") (pinfunction "1_1") (pintype "passive"))
    )
    (net (code "268") (name "/LUX33") (class "Default")
      (node (ref "CELL33") (pin "3") (pinfunction "3_3") (pintype "passive"))
      (node (ref "IC5") (pin "2") (pinfunction "CH1_2") (pintype "input"))
      (node (ref "R41") (pin "1") (pinfunction "1_1") (pintype "passive"))
    )
    (net (code "269") (name "/LUX34") (class "Default")
      (node (ref "CELL34") (pin "3") (pinfunction "3_3") (pintype "passive"))
      (node (ref "IC5") (pin "3") (pinfunction "CH2_3") (pintype "input"))
      (node (ref "R42") (pin "1") (pinfunction "1_1") (pintype "passive"))
    )
    (net (code "270") (name "/LUX35") (class "Default")
      (node (ref "CELL35") (pin "3") (pinfunction "3_3") (pintype "passive"))
      (node (ref "IC5") (pin "4") (pinfunction "CH3_4") (pintype "input"))
      (node (ref "R43") (pin "1") (pinfunction "1_1") (pintype "passive"))
    )
    (net (code "271") (name "/LUX36") (class "Default")
      (node (ref "CELL36") (pin "3") (pinfunction "3_3") (pintype "passive"))
      (node (ref "IC5") (pin "5") (pinfunction "CH4_5") (pintype "input"))
      (node (ref "R44") (pin "1") (pinfunction "1_1") (pintype "passive"))
    )
    (net (code "272") (name "/LUX37") (class "Default")
      (node (ref "CELL37") (pin "3") (pinfunction "3_3") (pintype "passive"))
      (node (ref "IC5") (pin "6") (pinfunction "CH5_6") (pintype "input"))
      (node (ref "R45") (pin "1") (pinfunction "1_1") (pintype "passive"))
    )
    (net (code "273") (name "/LUX38") (class "Default")
      (node (ref "CELL38") (pin "3") (pinfunction "3_3") (pintype "passive"))
      (node (ref "IC5") (pin "7") (pinfunction "CH6_7") (pintype "input"))
      (node (ref "R46") (pin "1") (pinfunction "1_1") (pintype "passive"))
    )
    (net (code "274") (name "/LUX39") (class "Default")
      (node (ref "CELL39") (pin "3") (pinfunction "3_3") (pintype "passive"))
      (node (ref "IC5") (pin "8") (pinfunction "CH7_8") (pintype "input"))
      (node (ref "R47") (pin "1") (pinfunction "1_1") (pintype "passive"))
    )
    (net (code "275") (name "/LUX40") (class "Default")
      (node (ref "CELL40") (pin "3") (pinfunction "3_3") (pintype "passive"))
      (node (ref "IC6") (pin "1") (pinfunction "CH0_1") (pintype "input"))
      (node (ref "R48") (pin "1") (pinfunction "1_1") (pintype "passive"))
    )
    (net (code "276") (name "/LUX41") (class "Default")
      (node (ref "CELL41") (pin "3") (pinfunction "3_3") (pintype "passive"))
      (node (ref "IC6") (pin "2") (pinfunction "CH1_2") (pintype "input"))
      (node (ref "R49") (pin "1") (pinfunction "1_1") (pintype "passive"))
    )
    (net (code "277") (name "/LUX42") (class "Default")
      (node (ref "CELL42") (pin "3") (pinfunction "3_3") (pintype "passive"))
      (node (ref "IC6") (pin "3") (pinfunction "CH2_3") (pintype "input"))
      (node (ref "R50") (pin "1") (pinfunction "1_1") (pintype "passive"))
    )
    (net (code "278") (name "/LUX43") (class "Default")
      (node (ref "CELL43") (pin "3") (pinfunction "3_3") (pintype "passive"))
      (node (ref "IC6") (pin "4") (pinfunction "CH3_4") (pintype "input"))
      (node (ref "R51") (pin "1") (pinfunction "1_1") (pintype "passive"))
    )
    (net (code "279") (name "/LUX44") (class "Default")
      (node (ref "CELL44") (pin "3") (pinfunction "3_3") (pintype "passive"))
      (node (ref "IC6") (pin "5") (pinfunction "CH4_5") (pintype "input"))
      (node (ref "R52") (pin "1") (pinfunction "1_1") (pintype "passive"))
    )
    (net (code "280") (name "/LUX45") (class "Default")
      (node (ref "CELL45") (pin "3") (pinfunction "3_3") (pintype "passive"))
      (node (ref "IC6") (pin "6") (pinfunction "CH5_6") (pintype "input"))
      (node (ref "R53") (pin "1") (pinfunction "1_1") (pintype "passive"))
    )
    (net (code "281") (name "/LUX46") (class "Default")
      (node (ref "CELL46") (pin "3") (pinfunction "3_3") (pintype "passive"))
      (node (ref "IC6") (pin "7") (pinfunction "CH6_7") (pintype "input"))
      (node (ref "R54") (pin "1") (pinfunction "1_1") (pintype "passive"))
    )
    (net (code "282") (name "/LUX47") (class "Default")
      (node (ref "CELL47") (pin "3") (pinfunction "3_3") (pintype "passive"))
      (node (ref "IC6") (pin "8") (pinfunction "CH7_8") (pintype "input"))
      (node (ref "R55") (pin "1") (pinfunction "1_1") (pintype "passive"))
    )
    (net (code "283") (name "/LUX48") (class "Default")
      (node (ref "CELL48") (pin "3") (pinfunction "3_3") (pintype "passive"))
      (node (ref "IC7") (pin "1") (pinfunction "CH0_1") (pintype "input"))
      (node (ref "R56") (pin "1") (pinfunction "1_1") (pintype "passive"))
    )
    (net (code "284") (name "/LUX49") (class "Default")
      (node (ref "CELL49") (pin "3") (pinfunction "3_3") (pintype "passive"))
      (node (ref "IC7") (pin "2") (pinfunction "CH1_2") (pintype "input"))
      (node (ref "R57") (pin "1") (pinfunction "1_1") (pintype "passive"))
    )
    (net (code "285") (name "/LUX50") (class "Default")
      (node (ref "CELL50") (pin "3") (pinfunction "3_3") (pintype "passive"))
      (node (ref "IC7") (pin "3") (pinfunction "CH2_3") (pintype "input"))
      (node (ref "R58") (pin "1") (pinfunction "1_1") (pintype "passive"))
    )
    (net (code "286") (name "/LUX51") (class "Default")
      (node (ref "CELL51") (pin "3") (pinfunction "3_3") (pintype "passive"))
      (node (ref "IC7") (pin "4") (pinfunction "CH3_4") (pintype "input"))
      (node (ref "R59") (pin "1") (pinfunction "1_1") (pintype "passive"))
    )
    (net (code "287") (name "/LUX52") (class "Default")
      (node (ref "CELL52") (pin "3") (pinfunction "3_3") (pintype "passive"))
      (node (ref "IC7") (pin "5") (pinfunction "CH4_5") (pintype "input"))
      (node (ref "R60") (pin "1") (pinfunction "1_1") (pintype "passive"))
    )
    (net (code "288") (name "/LUX53") (class "Default")
      (node (ref "CELL53") (pin "3") (pinfunction "3_3") (pintype "passive"))
      (node (ref "IC7") (pin "6") (pinfunction "CH5_6") (pintype "input"))
      (node (ref "R61") (pin "1") (pinfunction "1_1") (pintype "passive"))
    )
    (net (code "289") (name "/LUX54") (class "Default")
      (node (ref "CELL54") (pin "3") (pinfunction "3_3") (pintype "passive"))
      (node (ref "IC7") (pin "7") (pinfunction "CH6_7") (pintype "input"))
      (node (ref "R62") (pin "1") (pinfunction "1_1") (pintype "passive"))
    )
    (net (code "290") (name "/LUX55") (class "Default")
      (node (ref "CELL55") (pin "3") (pinfunction "3_3") (pintype "passive"))
      (node (ref "R63") (pin "1") (pinfunction "1_1") (pintype "passive"))
    )
    (net (code "291") (name "/LUX55.") (class "Default")
      (node (ref "IC7") (pin "8") (pinfunction "CH7_8") (pintype "input"))
    )
    (net (code "292") (name "/LUX56") (class "Default")
      (node (ref "CELL56") (pin "3") (pinfunction "3_3") (pintype "passive"))
      (node (ref "IC8") (pin "1") (pinfunction "CH0_1") (pintype "input"))
      (node (ref "R64") (pin "1") (pinfunction "1_1") (pintype "passive"))
    )
    (net (code "293") (name "/LUX57") (class "Default")
      (node (ref "CELL57") (pin "3") (pinfunction "3_3") (pintype "passive"))
      (node (ref "IC8") (pin "2") (pinfunction "CH1_2") (pintype "input"))
      (node (ref "R65") (pin "1") (pinfunction "1_1") (pintype "passive"))
    )
    (net (code "294") (name "/LUX58") (class "Default")
      (node (ref "CELL58") (pin "3") (pinfunction "3_3") (pintype "passive"))
      (node (ref "IC8") (pin "3") (pinfunction "CH2_3") (pintype "input"))
      (node (ref "R66") (pin "1") (pinfunction "1_1") (pintype "passive"))
    )
    (net (code "295") (name "/LUX59") (class "Default")
      (node (ref "CELL59") (pin "3") (pinfunction "3_3") (pintype "passive"))
      (node (ref "IC8") (pin "4") (pinfunction "CH3_4") (pintype "input"))
      (node (ref "R67") (pin "1") (pinfunction "1_1") (pintype "passive"))
    )
    (net (code "296") (name "/LUX60") (class "Default")
      (node (ref "CELL60") (pin "3") (pinfunction "3_3") (pintype "passive"))
      (node (ref "IC8") (pin "5") (pinfunction "CH4_5") (pintype "input"))
      (node (ref "R68") (pin "1") (pinfunction "1_1") (pintype "passive"))
    )
    (net (code "297") (name "/LUX61") (class "Default")
      (node (ref "CELL61") (pin "3") (pinfunction "3_3") (pintype "passive"))
      (node (ref "IC8") (pin "6") (pinfunction "CH5_6") (pintype "input"))
      (node (ref "R69") (pin "1") (pinfunction "1_1") (pintype "passive"))
    )
    (net (code "298") (name "/LUX62") (class "Default")
      (node (ref "CELL62") (pin "3") (pinfunction "3_3") (pintype "passive"))
      (node (ref "IC8") (pin "7") (pinfunction "CH6_7") (pintype "input"))
      (node (ref "R70") (pin "1") (pinfunction "1_1") (pintype "passive"))
    )
    (net (code "299") (name "/LUX63") (class "Default")
      (node (ref "CELL63") (pin "3") (pinfunction "3_3") (pintype "passive"))
      (node (ref "IC8") (pin "8") (pinfunction "CH7_8") (pintype "input"))
      (node (ref "R71") (pin "1") (pinfunction "1_1") (pintype "passive"))
    )
    (net (code "300") (name "/LUX64") (class "Default")
      (node (ref "CELL64") (pin "3") (pinfunction "3_3") (pintype "passive"))
      (node (ref "IC9") (pin "1") (pinfunction "CH0_1") (pintype "input"))
      (node (ref "R72") (pin "1") (pinfunction "1_1") (pintype "passive"))
    )
    (net (code "301") (name "/LUX65") (class "Default")
      (node (ref "CELL65") (pin "3") (pinfunction "3_3") (pintype "passive"))
      (node (ref "IC9") (pin "2") (pinfunction "CH1_2") (pintype "input"))
      (node (ref "R73") (pin "1") (pinfunction "1_1") (pintype "passive"))
    )
    (net (code "302") (name "/LUX66") (class "Default")
      (node (ref "CELL66") (pin "3") (pinfunction "3_3") (pintype "passive"))
      (node (ref "IC9") (pin "3") (pinfunction "CH2_3") (pintype "input"))
      (node (ref "R74") (pin "1") (pinfunction "1_1") (pintype "passive"))
    )
    (net (code "303") (name "/LUX67") (class "Default")
      (node (ref "CELL67") (pin "3") (pinfunction "3_3") (pintype "passive"))
      (node (ref "IC9") (pin "4") (pinfunction "CH3_4") (pintype "input"))
      (node (ref "R75") (pin "1") (pinfunction "1_1") (pintype "passive"))
    )
    (net (code "304") (name "/LUX68") (class "Default")
      (node (ref "CELL68") (pin "3") (pinfunction "3_3") (pintype "passive"))
      (node (ref "IC9") (pin "5") (pinfunction "CH4_5") (pintype "input"))
      (node (ref "R76") (pin "1") (pinfunction "1_1") (pintype "passive"))
    )
    (net (code "305") (name "/LUX69") (class "Default")
      (node (ref "CELL69") (pin "3") (pinfunction "3_3") (pintype "passive"))
      (node (ref "IC9") (pin "6") (pinfunction "CH5_6") (pintype "input"))
      (node (ref "R77") (pin "1") (pinfunction "1_1") (pintype "passive"))
    )
    (net (code "306") (name "/LUX70") (class "Default")
      (node (ref "CELL70") (pin "3") (pinfunction "3_3") (pintype "passive"))
      (node (ref "IC9") (pin "7") (pinfunction "CH6_7") (pintype "input"))
      (node (ref "R78") (pin "1") (pinfunction "1_1") (pintype "passive"))
    )
    (net (code "307") (name "/LUX71") (class "Default")
      (node (ref "CELL71") (pin "3") (pinfunction "3_3") (pintype "passive"))
      (node (ref "IC9") (pin "8") (pinfunction "CH7_8") (pintype "input"))
      (node (ref "R79") (pin "1") (pinfunction "1_1") (pintype "passive"))
    )
    (net (code "308") (name "/LUX72") (class "Default")
      (node (ref "CELL72") (pin "3") (pinfunction "3_3") (pintype "passive"))
      (node (ref "IC10") (pin "1") (pinfunction "CH0_1") (pintype "input"))
      (node (ref "R80") (pin "1") (pinfunction "1_1") (pintype "passive"))
    )
    (net (code "309") (name "/LUX73") (class "Default")
      (node (ref "CELL73") (pin "3") (pinfunction "3_3") (pintype "passive"))
      (node (ref "IC10") (pin "2") (pinfunction "CH1_2") (pintype "input"))
      (node (ref "R81") (pin "1") (pinfunction "1_1") (pintype "passive"))
    )
    (net (code "310") (name "/LUX74") (class "Default")
      (node (ref "CELL74") (pin "3") (pinfunction "3_3") (pintype "passive"))
      (node (ref "IC10") (pin "3") (pinfunction "CH2_3") (pintype "input"))
      (node (ref "R82") (pin "1") (pinfunction "1_1") (pintype "passive"))
    )
    (net (code "311") (name "/LUX75") (class "Default")
      (node (ref "CELL75") (pin "3") (pinfunction "3_3") (pintype "passive"))
      (node (ref "IC10") (pin "4") (pinfunction "CH3_4") (pintype "input"))
      (node (ref "R83") (pin "1") (pinfunction "1_1") (pintype "passive"))
    )
    (net (code "312") (name "/LUX76") (class "Default")
      (node (ref "CELL76") (pin "3") (pinfunction "3_3") (pintype "passive"))
      (node (ref "IC10") (pin "5") (pinfunction "CH4_5") (pintype "input"))
      (node (ref "R84") (pin "1") (pinfunction "1_1") (pintype "passive"))
    )
    (net (code "313") (name "/LUX77") (class "Default")
      (node (ref "CELL77") (pin "3") (pinfunction "3_3") (pintype "passive"))
      (node (ref "IC10") (pin "6") (pinfunction "CH5_6") (pintype "input"))
      (node (ref "R85") (pin "1") (pinfunction "1_1") (pintype "passive"))
    )
    (net (code "314") (name "/LUX78") (class "Default")
      (node (ref "CELL78") (pin "3") (pinfunction "3_3") (pintype "passive"))
      (node (ref "IC10") (pin "7") (pinfunction "CH6_7") (pintype "input"))
      (node (ref "R86") (pin "1") (pinfunction "1_1") (pintype "passive"))
    )
    (net (code "315") (name "/LUX79") (class "Default")
      (node (ref "CELL79") (pin "3") (pinfunction "3_3") (pintype "passive"))
      (node (ref "IC10") (pin "8") (pinfunction "CH7_8") (pintype "input"))
      (node (ref "R87") (pin "1") (pinfunction "1_1") (pintype "passive"))
    )
    (net (code "316") (name "/LUX80") (class "Default")
      (node (ref "CELL80") (pin "3") (pinfunction "3_3") (pintype "passive"))
      (node (ref "IC11") (pin "1") (pinfunction "CH0_1") (pintype "input"))
      (node (ref "R88") (pin "1") (pinfunction "1_1") (pintype "passive"))
    )
    (net (code "317") (name "/LUX81") (class "Default")
      (node (ref "CELL81") (pin "3") (pinfunction "3_3") (pintype "passive"))
      (node (ref "IC11") (pin "2") (pinfunction "CH1_2") (pintype "input"))
      (node (ref "R89") (pin "1") (pinfunction "1_1") (pintype "passive"))
    )
    (net (code "318") (name "/LUX82") (class "Default")
      (node (ref "CELL82") (pin "3") (pinfunction "3_3") (pintype "passive"))
      (node (ref "IC11") (pin "3") (pinfunction "CH2_3") (pintype "input"))
      (node (ref "R90") (pin "1") (pinfunction "1_1") (pintype "passive"))
    )
    (net (code "319") (name "/LUX83") (class "Default")
      (node (ref "CELL83") (pin "3") (pinfunction "3_3") (pintype "passive"))
      (node (ref "IC11") (pin "4") (pinfunction "CH3_4") (pintype "input"))
      (node (ref "R91") (pin "1") (pinfunction "1_1") (pintype "passive"))
    )
    (net (code "320") (name "/LUX84") (class "Default")
      (node (ref "CELL84") (pin "3") (pinfunction "3_3") (pintype "passive"))
      (node (ref "IC11") (pin "5") (pinfunction "CH4_5") (pintype "input"))
      (node (ref "R92") (pin "1") (pinfunction "1_1") (pintype "passive"))
    )
    (net (code "321") (name "/LUX85") (class "Default")
      (node (ref "CELL85") (pin "3") (pinfunction "3_3") (pintype "passive"))
      (node (ref "IC11") (pin "6") (pinfunction "CH5_6") (pintype "input"))
      (node (ref "R93") (pin "1") (pinfunction "1_1") (pintype "passive"))
    )
    (net (code "322") (name "/LUX86") (class "Default")
      (node (ref "CELL86") (pin "3") (pinfunction "3_3") (pintype "passive"))
      (node (ref "IC11") (pin "7") (pinfunction "CH6_7") (pintype "input"))
      (node (ref "R94") (pin "1") (pinfunction "1_1") (pintype "passive"))
    )
    (net (code "323") (name "/LUX87") (class "Default")
      (node (ref "CELL87") (pin "3") (pinfunction "3_3") (pintype "passive"))
      (node (ref "IC11") (pin "8") (pinfunction "CH7_8") (pintype "input"))
      (node (ref "R95") (pin "1") (pinfunction "1_1") (pintype "passive"))
    )
    (net (code "324") (name "/LUX88") (class "Default")
      (node (ref "CELL88") (pin "3") (pinfunction "3_3") (pintype "passive"))
      (node (ref "IC12") (pin "1") (pinfunction "CH0_1") (pintype "input"))
      (node (ref "R96") (pin "1") (pinfunction "1_1") (pintype "passive"))
    )
    (net (code "325") (name "/LUX89") (class "Default")
      (node (ref "CELL89") (pin "3") (pinfunction "3_3") (pintype "passive"))
      (node (ref "IC12") (pin "2") (pinfunction "CH1_2") (pintype "input"))
      (node (ref "R97") (pin "1") (pinfunction "1_1") (pintype "passive"))
    )
    (net (code "326") (name "/LUX90") (class "Default")
      (node (ref "CELL90") (pin "3") (pinfunction "3_3") (pintype "passive"))
      (node (ref "IC12") (pin "3") (pinfunction "CH2_3") (pintype "input"))
      (node (ref "R98") (pin "1") (pinfunction "1_1") (pintype "passive"))
    )
    (net (code "327") (name "/LUX91") (class "Default")
      (node (ref "CELL91") (pin "3") (pinfunction "3_3") (pintype "passive"))
      (node (ref "IC12") (pin "4") (pinfunction "CH3_4") (pintype "input"))
      (node (ref "R99") (pin "1") (pinfunction "1_1") (pintype "passive"))
    )
    (net (code "328") (name "/LUX92") (class "Default")
      (node (ref "CELL92") (pin "3") (pinfunction "3_3") (pintype "passive"))
      (node (ref "IC12") (pin "5") (pinfunction "CH4_5") (pintype "input"))
      (node (ref "R100") (pin "1") (pinfunction "1_1") (pintype "passive"))
    )
    (net (code "329") (name "/LUX93") (class "Default")
      (node (ref "CELL93") (pin "3") (pinfunction "3_3") (pintype "passive"))
      (node (ref "IC12") (pin "6") (pinfunction "CH5_6") (pintype "input"))
      (node (ref "R101") (pin "1") (pinfunction "1_1") (pintype "passive"))
    )
    (net (code "330") (name "/LUX94") (class "Default")
      (node (ref "CELL94") (pin "3") (pinfunction "3_3") (pintype "passive"))
      (node (ref "IC12") (pin "7") (pinfunction "CH6_7") (pintype "input"))
      (node (ref "R102") (pin "1") (pinfunction "1_1") (pintype "passive"))
    )
    (net (code "331") (name "/LUX95") (class "Default")
      (node (ref "CELL95") (pin "3") (pinfunction "3_3") (pintype "passive"))
      (node (ref "IC12") (pin "8") (pinfunction "CH7_8") (pintype "input"))
      (node (ref "R103") (pin "1") (pinfunction "1_1") (pintype "passive"))
    )
    (net (code "332") (name "/LUX96") (class "Default")
      (node (ref "CELL96") (pin "3") (pinfunction "3_3") (pintype "passive"))
      (node (ref "IC26") (pin "1") (pinfunction "CH0_1") (pintype "input"))
      (node (ref "R104") (pin "1") (pinfunction "1_1") (pintype "passive"))
    )
    (net (code "333") (name "/LUX97") (class "Default")
      (node (ref "CELL97") (pin "3") (pinfunction "3_3") (pintype "passive"))
      (node (ref "IC26") (pin "2") (pinfunction "CH1_2") (pintype "input"))
      (node (ref "R105") (pin "1") (pinfunction "1_1") (pintype "passive"))
    )
    (net (code "334") (name "/LUX98") (class "Default")
      (node (ref "CELL98") (pin "3") (pinfunction "3_3") (pintype "passive"))
      (node (ref "IC26") (pin "3") (pinfunction "CH2_3") (pintype "input"))
      (node (ref "R106") (pin "1") (pinfunction "1_1") (pintype "passive"))
    )
    (net (code "335") (name "/LUX99") (class "Default")
      (node (ref "CELL99") (pin "3") (pinfunction "3_3") (pintype "passive"))
      (node (ref "IC26") (pin "4") (pinfunction "CH3_4") (pintype "input"))
      (node (ref "R107") (pin "1") (pinfunction "1_1") (pintype "passive"))
    )
    (net (code "336") (name "/LUX100") (class "Default")
      (node (ref "CELL100") (pin "3") (pinfunction "3_3") (pintype "passive"))
      (node (ref "IC26") (pin "5") (pinfunction "CH4_5") (pintype "input"))
      (node (ref "R108") (pin "1") (pinfunction "1_1") (pintype "passive"))
    )
    (net (code "337") (name "/LUX101") (class "Default")
      (node (ref "CELL101") (pin "3") (pinfunction "3_3") (pintype "passive"))
      (node (ref "IC26") (pin "6") (pinfunction "CH5_6") (pintype "input"))
      (node (ref "R109") (pin "1") (pinfunction "1_1") (pintype "passive"))
    )
    (net (code "338") (name "/LUX102") (class "Default")
      (node (ref "CELL102") (pin "3") (pinfunction "3_3") (pintype "passive"))
      (node (ref "IC26") (pin "7") (pinfunction "CH6_7") (pintype "input"))
      (node (ref "R110") (pin "1") (pinfunction "1_1") (pintype "passive"))
    )
    (net (code "339") (name "/LUX103") (class "Default")
      (node (ref "CELL103") (pin "3") (pinfunction "3_3") (pintype "passive"))
      (node (ref "IC26") (pin "8") (pinfunction "CH7_8") (pintype "input"))
      (node (ref "R111") (pin "1") (pinfunction "1_1") (pintype "passive"))
    )
    (net (code "340") (name "/MISO") (class "Default")
      (node (ref "IC1") (pin "12") (pinfunction "DOUT_12") (pintype "output"))
      (node (ref "IC10") (pin "12") (pinfunction "DOUT_12") (pintype "output"))
      (node (ref "IC11") (pin "12") (pinfunction "DOUT_12") (pintype "output"))
      (node (ref "IC12") (pin "12") (pinfunction "DOUT_12") (pintype "output"))
      (node (ref "IC18") (pin "14") (pinfunction "SO_14") (pintype "output"))
      (node (ref "IC19") (pin "14") (pinfunction "SO_14") (pintype "output"))
      (node (ref "IC2") (pin "12") (pinfunction "DOUT_12") (pintype "output"))
      (node (ref "IC20") (pin "14") (pinfunction "SO_14") (pintype "output"))
      (node (ref "IC21") (pin "14") (pinfunction "SO_14") (pintype "output"))
      (node (ref "IC22") (pin "14") (pinfunction "SO_14") (pintype "output"))
      (node (ref "IC23") (pin "14") (pinfunction "SO_14") (pintype "output"))
      (node (ref "IC24") (pin "14") (pinfunction "SO_14") (pintype "output"))
      (node (ref "IC25") (pin "14") (pinfunction "SO_14") (pintype "output"))
      (node (ref "IC26") (pin "12") (pinfunction "DOUT_12") (pintype "output"))
      (node (ref "IC3") (pin "12") (pinfunction "DOUT_12") (pintype "output"))
      (node (ref "IC4") (pin "12") (pinfunction "DOUT_12") (pintype "output"))
      (node (ref "IC5") (pin "12") (pinfunction "DOUT_12") (pintype "output"))
      (node (ref "IC6") (pin "12") (pinfunction "DOUT_12") (pintype "output"))
      (node (ref "IC7") (pin "12") (pinfunction "DOUT_12") (pintype "output"))
      (node (ref "IC8") (pin "12") (pinfunction "DOUT_12") (pintype "output"))
      (node (ref "IC9") (pin "12") (pinfunction "DOUT_12") (pintype "output"))
      (node (ref "ISP") (pin "1") (pinfunction "1_1") (pintype "passive"))
      (node (ref "U1") (pin "18") (pinfunction "PB4(MISO)_18") (pintype "bidirectional"))
    )
    (net (code "341") (name "/MOSI") (class "Default")
      (node (ref "IC1") (pin "11") (pinfunction "DIN_11") (pintype "input"))
      (node (ref "IC10") (pin "11") (pinfunction "DIN_11") (pintype "input"))
      (node (ref "IC11") (pin "11") (pinfunction "DIN_11") (pintype "input"))
      (node (ref "IC12") (pin "11") (pinfunction "DIN_11") (pintype "input"))
      (node (ref "IC18") (pin "13") (pinfunction "SI_13") (pintype "input"))
      (node (ref "IC19") (pin "13") (pinfunction "SI_13") (pintype "input"))
      (node (ref "IC2") (pin "11") (pinfunction "DIN_11") (pintype "input"))
      (node (ref "IC20") (pin "13") (pinfunction "SI_13") (pintype "input"))
      (node (ref "IC21") (pin "13") (pinfunction "SI_13") (pintype "input"))
      (node (ref "IC22") (pin "13") (pinfunction "SI_13") (pintype "input"))
      (node (ref "IC23") (pin "13") (pinfunction "SI_13") (pintype "input"))
      (node (ref "IC24") (pin "13") (pinfunction "SI_13") (pintype "input"))
      (node (ref "IC25") (pin "13") (pinfunction "SI_13") (pintype "input"))
      (node (ref "IC26") (pin "11") (pinfunction "DIN_11") (pintype "input"))
      (node (ref "IC3") (pin "11") (pinfunction "DIN_11") (pintype "input"))
      (node (ref "IC4") (pin "11") (pinfunction "DIN_11") (pintype "input"))
      (node (ref "IC5") (pin "11") (pinfunction "DIN_11") (pintype "input"))
      (node (ref "IC6") (pin "11") (pinfunction "DIN_11") (pintype "input"))
      (node (ref "IC7") (pin "11") (pinfunction "DIN_11") (pintype "input"))
      (node (ref "IC8") (pin "11") (pinfunction "DIN_11") (pintype "input"))
      (node (ref "IC9") (pin "11") (pinfunction "DIN_11") (pintype "input"))
      (node (ref "ISP") (pin "4") (pinfunction "4_4") (pintype "passive"))
      (node (ref "U1") (pin "17") (pinfunction "PB3(MOSI/OC2)_17") (pintype "bidirectional"))
    )
    (net (code "342") (name "/RED") (class "Default")
      (node (ref "JP2") (pin "6") (pinfunction "6_6") (pintype "passive"))
      (node (ref "U1") (pin "6") (pinfunction "PD4(XCK/T0)_6") (pintype "bidirectional"))
    )
    (net (code "343") (name "/RST") (class "Default")
      (node (ref "ISP") (pin "5") (pinfunction "5_5") (pintype "passive"))
      (node (ref "U1") (pin "1") (pinfunction "PC6(/RESET)_1") (pintype "bidirectional"))
    )
    (net (code "344") (name "/RX") (class "Default")
      (node (ref "JP2") (pin "7") (pinfunction "7_7") (pintype "passive"))
      (node (ref "JP3") (pin "1") (pinfunction "1_1") (pintype "passive"))
      (node (ref "U1") (pin "2") (pinfunction "PD0(RXD)_2") (pintype "bidirectional"))
    )
    (net (code "345") (name "/SBU1") (class "Default")
      (node (ref "JP1") (pin "7") (pinfunction "7_7") (pintype "passive"))
    )
    (net (code "346") (name "/SBU2") (class "Default")
      (node (ref "JP1") (pin "3") (pinfunction "3_3") (pintype "passive"))
    )
    (net (code "347") (name "/SCK") (class "Default")
      (node (ref "IC1") (pin "13") (pinfunction "CLK_13") (pintype "input"))
      (node (ref "IC10") (pin "13") (pinfunction "CLK_13") (pintype "input"))
      (node (ref "IC11") (pin "13") (pinfunction "CLK_13") (pintype "input"))
      (node (ref "IC12") (pin "13") (pinfunction "CLK_13") (pintype "input"))
      (node (ref "IC18") (pin "12") (pinfunction "SCK_12") (pintype "input"))
      (node (ref "IC19") (pin "12") (pinfunction "SCK_12") (pintype "input"))
      (node (ref "IC2") (pin "13") (pinfunction "CLK_13") (pintype "input"))
      (node (ref "IC20") (pin "12") (pinfunction "SCK_12") (pintype "input"))
      (node (ref "IC21") (pin "12") (pinfunction "SCK_12") (pintype "input"))
      (node (ref "IC22") (pin "12") (pinfunction "SCK_12") (pintype "input"))
      (node (ref "IC23") (pin "12") (pinfunction "SCK_12") (pintype "input"))
      (node (ref "IC24") (pin "12") (pinfunction "SCK_12") (pintype "input"))
      (node (ref "IC25") (pin "12") (pinfunction "SCK_12") (pintype "input"))
      (node (ref "IC26") (pin "13") (pinfunction "CLK_13") (pintype "input"))
      (node (ref "IC3") (pin "13") (pinfunction "CLK_13") (pintype "input"))
      (node (ref "IC4") (pin "13") (pinfunction "CLK_13") (pintype "input"))
      (node (ref "IC5") (pin "13") (pinfunction "CLK_13") (pintype "input"))
      (node (ref "IC6") (pin "13") (pinfunction "CLK_13") (pintype "input"))
      (node (ref "IC7") (pin "13") (pinfunction "CLK_13") (pintype "input"))
      (node (ref "IC8") (pin "13") (pinfunction "CLK_13") (pintype "input"))
      (node (ref "IC9") (pin "13") (pinfunction "CLK_13") (pintype "input"))
      (node (ref "ISP") (pin "3") (pinfunction "3_3") (pintype "passive"))
      (node (ref "U1") (pin "19") (pinfunction "PB5(SCK)_19") (pintype "bidirectional"))
    )
    (net (code "348") (name "/SPEAKER") (class "Default")
      (node (ref "JP2") (pin "10") (pinfunction "10_10") (pintype "passive"))
    )
    (net (code "349") (name "/TX") (class "Default")
      (node (ref "JP2") (pin "5") (pinfunction "5_5") (pintype "passive"))
      (node (ref "JP3") (pin "2") (pinfunction "2_2") (pintype "passive"))
      (node (ref "U1") (pin "3") (pinfunction "PD1(TXD)_3") (pintype "bidirectional"))
    )
    (net (code "350") (name "/VCC") (class "Default")
      (node (ref "C1") (pin "2") (pinfunction "2_2") (pintype "passive"))
      (node (ref "C2") (pin "2") (pinfunction "2_2") (pintype "passive"))
      (node (ref "C3") (pin "2") (pinfunction "2_2") (pintype "passive"))
      (node (ref "C4") (pin "2") (pinfunction "2_2") (pintype "passive"))
      (node (ref "C5") (pin "2") (pinfunction "2_2") (pintype "passive"))
      (node (ref "C6") (pin "2") (pinfunction "2_2") (pintype "passive"))
      (node (ref "CELL0") (pin "1") (pinfunction "1_1") (pintype "passive"))
      (node (ref "CELL1") (pin "1") (pinfunction "1_1") (pintype "passive"))
      (node (ref "CELL10") (pin "1") (pinfunction "1_1") (pintype "passive"))
      (node (ref "CELL100") (pin "1") (pinfunction "1_1") (pintype "passive"))
      (node (ref "CELL101") (pin "1") (pinfunction "1_1") (pintype "passive"))
      (node (ref "CELL102") (pin "1") (pinfunction "1_1") (pintype "passive"))
      (node (ref "CELL103") (pin "1") (pinfunction "1_1") (pintype "passive"))
      (node (ref "CELL11") (pin "1") (pinfunction "1_1") (pintype "passive"))
      (node (ref "CELL12") (pin "1") (pinfunction "1_1") (pintype "passive"))
      (node (ref "CELL13") (pin "1") (pinfunction "1_1") (pintype "passive"))
      (node (ref "CELL14") (pin "1") (pinfunction "1_1") (pintype "passive"))
      (node (ref "CELL15") (pin "1") (pinfunction "1_1") (pintype "passive"))
      (node (ref "CELL16") (pin "1") (pinfunction "1_1") (pintype "passive"))
      (node (ref "CELL17") (pin "1") (pinfunction "1_1") (pintype "passive"))
      (node (ref "CELL18") (pin "1") (pinfunction "1_1") (pintype "passive"))
      (node (ref "CELL19") (pin "1") (pinfunction "1_1") (pintype "passive"))
      (node (ref "CELL2") (pin "1") (pinfunction "1_1") (pintype "passive"))
      (node (ref "CELL20") (pin "1") (pinfunction "1_1") (pintype "passive"))
      (node (ref "CELL21") (pin "1") (pinfunction "1_1") (pintype "passive"))
      (node (ref "CELL22") (pin "1") (pinfunction "1_1") (pintype "passive"))
      (node (ref "CELL23") (pin "1") (pinfunction "1_1") (pintype "passive"))
      (node (ref "CELL24") (pin "1") (pinfunction "1_1") (pintype "passive"))
      (node (ref "CELL25") (pin "1") (pinfunction "1_1") (pintype "passive"))
      (node (ref "CELL26") (pin "1") (pinfunction "1_1") (pintype "passive"))
      (node (ref "CELL27") (pin "1") (pinfunction "1_1") (pintype "passive"))
      (node (ref "CELL28") (pin "1") (pinfunction "1_1") (pintype "passive"))
      (node (ref "CELL29") (pin "1") (pinfunction "1_1") (pintype "passive"))
      (node (ref "CELL3") (pin "1") (pinfunction "1_1") (pintype "passive"))
      (node (ref "CELL30") (pin "1") (pinfunction "1_1") (pintype "passive"))
      (node (ref "CELL31") (pin "1") (pinfunction "1_1") (pintype "passive"))
      (node (ref "CELL32") (pin "1") (pinfunction "1_1") (pintype "passive"))
      (node (ref "CELL33") (pin "1") (pinfunction "1_1") (pintype "passive"))
      (node (ref "CELL34") (pin "1") (pinfunction "1_1") (pintype "passive"))
      (node (ref "CELL35") (pin "1") (pinfunction "1_1") (pintype "passive"))
      (node (ref "CELL36") (pin "1") (pinfunction "1_1") (pintype "passive"))
      (node (ref "CELL37") (pin "1") (pinfunction "1_1") (pintype "passive"))
      (node (ref "CELL38") (pin "1") (pinfunction "1_1") (pintype "passive"))
      (node (ref "CELL39") (pin "1") (pinfunction "1_1") (pintype "passive"))
      (node (ref "CELL4") (pin "1") (pinfunction "1_1") (pintype "passive"))
      (node (ref "CELL40") (pin "1") (pinfunction "1_1") (pintype "passive"))
      (node (ref "CELL41") (pin "1") (pinfunction "1_1") (pintype "passive"))
      (node (ref "CELL42") (pin "1") (pinfunction "1_1") (pintype "passive"))
      (node (ref "CELL43") (pin "1") (pinfunction "1_1") (pintype "passive"))
      (node (ref "CELL44") (pin "1") (pinfunction "1_1") (pintype "passive"))
      (node (ref "CELL45") (pin "1") (pinfunction "1_1") (pintype "passive"))
      (node (ref "CELL46") (pin "1") (pinfunction "1_1") (pintype "passive"))
      (node (ref "CELL47") (pin "1") (pinfunction "1_1") (pintype "passive"))
      (node (ref "CELL48") (pin "1") (pinfunction "1_1") (pintype "passive"))
      (node (ref "CELL49") (pin "1") (pinfunction "1_1") (pintype "passive"))
      (node (ref "CELL5") (pin "1") (pinfunction "1_1") (pintype "passive"))
      (node (ref "CELL50") (pin "1") (pinfunction "1_1") (pintype "passive"))
      (node (ref "CELL51") (pin "1") (pinfunction "1_1") (pintype "passive"))
      (node (ref "CELL52") (pin "1") (pinfunction "1_1") (pintype "passive"))
      (node (ref "CELL53") (pin "1") (pinfunction "1_1") (pintype "passive"))
      (node (ref "CELL54") (pin "1") (pinfunction "1_1") (pintype "passive"))
      (node (ref "CELL55") (pin "1") (pinfunction "1_1") (pintype "passive"))
      (node (ref "CELL56") (pin "1") (pinfunction "1_1") (pintype "passive"))
      (node (ref "CELL57") (pin "1") (pinfunction "1_1") (pintype "passive"))
      (node (ref "CELL58") (pin "1") (pinfunction "1_1") (pintype "passive"))
      (node (ref "CELL59") (pin "1") (pinfunction "1_1") (pintype "passive"))
      (node (ref "CELL6") (pin "1") (pinfunction "1_1") (pintype "passive"))
      (node (ref "CELL60") (pin "1") (pinfunction "1_1") (pintype "passive"))
      (node (ref "CELL61") (pin "1") (pinfunction "1_1") (pintype "passive"))
      (node (ref "CELL62") (pin "1") (pinfunction "1_1") (pintype "passive"))
      (node (ref "CELL63") (pin "1") (pinfunction "1_1") (pintype "passive"))
      (node (ref "CELL64") (pin "1") (pinfunction "1_1") (pintype "passive"))
      (node (ref "CELL65") (pin "1") (pinfunction "1_1") (pintype "passive"))
      (node (ref "CELL66") (pin "1") (pinfunction "1_1") (pintype "passive"))
      (node (ref "CELL67") (pin "1") (pinfunction "1_1") (pintype "passive"))
      (node (ref "CELL68") (pin "1") (pinfunction "1_1") (pintype "passive"))
      (node (ref "CELL69") (pin "1") (pinfunction "1_1") (pintype "passive"))
      (node (ref "CELL7") (pin "1") (pinfunction "1_1") (pintype "passive"))
      (node (ref "CELL70") (pin "1") (pinfunction "1_1") (pintype "passive"))
      (node (ref "CELL71") (pin "1") (pinfunction "1_1") (pintype "passive"))
      (node (ref "CELL72") (pin "1") (pinfunction "1_1") (pintype "passive"))
      (node (ref "CELL73") (pin "1") (pinfunction "1_1") (pintype "passive"))
      (node (ref "CELL74") (pin "1") (pinfunction "1_1") (pintype "passive"))
      (node (ref "CELL75") (pin "1") (pinfunction "1_1") (pintype "passive"))
      (node (ref "CELL76") (pin "1") (pinfunction "1_1") (pintype "passive"))
      (node (ref "CELL77") (pin "1") (pinfunction "1_1") (pintype "passive"))
      (node (ref "CELL78") (pin "1") (pinfunction "1_1") (pintype "passive"))
      (node (ref "CELL79") (pin "1") (pinfunction "1_1") (pintype "passive"))
      (node (ref "CELL8") (pin "1") (pinfunction "1_1") (pintype "passive"))
      (node (ref "CELL80") (pin "1") (pinfunction "1_1") (pintype "passive"))
      (node (ref "CELL81") (pin "1") (pinfunction "1_1") (pintype "passive"))
      (node (ref "CELL82") (pin "1") (pinfunction "1_1") (pintype "passive"))
      (node (ref "CELL83") (pin "1") (pinfunction "1_1") (pintype "passive"))
      (node (ref "CELL84") (pin "1") (pinfunction "1_1") (pintype "passive"))
      (node (ref "CELL85") (pin "1") (pinfunction "1_1") (pintype "passive"))
      (node (ref "CELL86") (pin "1") (pinfunction "1_1") (pintype "passive"))
      (node (ref "CELL87") (pin "1") (pinfunction "1_1") (pintype "passive"))
      (node (ref "CELL88") (pin "1") (pinfunction "1_1") (pintype "passive"))
      (node (ref "CELL89") (pin "1") (pinfunction "1_1") (pintype "passive"))
      (node (ref "CELL9") (pin "1") (pinfunction "1_1") (pintype "passive"))
      (node (ref "CELL90") (pin "1") (pinfunction "1_1") (pintype "passive"))
      (node (ref "CELL91") (pin "1") (pinfunction "1_1") (pintype "passive"))
      (node (ref "CELL92") (pin "1") (pinfunction "1_1") (pintype "passive"))
      (node (ref "CELL93") (pin "1") (pinfunction "1_1") (pintype "passive"))
      (node (ref "CELL94") (pin "1") (pinfunction "1_1") (pintype "passive"))
      (node (ref "CELL95") (pin "1") (pinfunction "1_1") (pintype "passive"))
      (node (ref "CELL96") (pin "1") (pinfunction "1_1") (pintype "passive"))
      (node (ref "CELL97") (pin "1") (pinfunction "1_1") (pintype "passive"))
      (node (ref "CELL98") (pin "1") (pinfunction "1_1") (pintype "passive"))
      (node (ref "CELL99") (pin "1") (pinfunction "1_1") (pintype "passive"))
      (node (ref "IC1") (pin "15") (pinfunction "VREF_15") (pintype "input"))
      (node (ref "IC1") (pin "16") (pinfunction "VDD_16") (pintype "power_in"))
      (node (ref "IC10") (pin "15") (pinfunction "VREF_15") (pintype "input"))
      (node (ref "IC10") (pin "16") (pinfunction "VDD_16") (pintype "power_in"))
      (node (ref "IC11") (pin "15") (pinfunction "VREF_15") (pintype "input"))
      (node (ref "IC11") (pin "16") (pinfunction "VDD_16") (pintype "power_in"))
      (node (ref "IC12") (pin "15") (pinfunction "VREF_15") (pintype "input"))
      (node (ref "IC12") (pin "16") (pinfunction "VDD_16") (pintype "power_in"))
      (node (ref "IC13") (pin "32") (pinfunction "VCC_32") (pintype "power_in"))
      (node (ref "IC14") (pin "32") (pinfunction "VCC_32") (pintype "power_in"))
      (node (ref "IC15") (pin "32") (pinfunction "VCC_32") (pintype "power_in"))
      (node (ref "IC16") (pin "32") (pinfunction "VCC_32") (pintype "power_in"))
      (node (ref "IC17") (pin "32") (pinfunction "VCC_32") (pintype "power_in"))
      (node (ref "IC18") (pin "18") (pinfunction "~{RESET}_18") (pintype "input"))
      (node (ref "IC18") (pin "9") (pinfunction "VDD_9") (pintype "power_in"))
      (node (ref "IC19") (pin "15") (pinfunction "A0_15") (pintype "input"))
      (node (ref "IC19") (pin "18") (pinfunction "~{RESET}_18") (pintype "input"))
      (node (ref "IC19") (pin "9") (pinfunction "VDD_9") (pintype "power_in"))
      (node (ref "IC2") (pin "15") (pinfunction "VREF_15") (pintype "input"))
      (node (ref "IC2") (pin "16") (pinfunction "VDD_16") (pintype "power_in"))
      (node (ref "IC20") (pin "16") (pinfunction "A1_16") (pintype "input"))
      (node (ref "IC20") (pin "18") (pinfunction "~{RESET}_18") (pintype "input"))
      (node (ref "IC20") (pin "9") (pinfunction "VDD_9") (pintype "power_in"))
      (node (ref "IC21") (pin "15") (pinfunction "A0_15") (pintype "input"))
      (node (ref "IC21") (pin "16") (pinfunction "A1_16") (pintype "input"))
      (node (ref "IC21") (pin "18") (pinfunction "~{RESET}_18") (pintype "input"))
      (node (ref "IC21") (pin "9") (pinfunction "VDD_9") (pintype "power_in"))
      (node (ref "IC22") (pin "17") (pinfunction "A2_17") (pintype "input"))
      (node (ref "IC22") (pin "18") (pinfunction "~{RESET}_18") (pintype "input"))
      (node (ref "IC22") (pin "9") (pinfunction "VDD_9") (pintype "power_in"))
      (node (ref "IC23") (pin "15") (pinfunction "A0_15") (pintype "input"))
      (node (ref "IC23") (pin "17") (pinfunction "A2_17") (pintype "input"))
      (node (ref "IC23") (pin "18") (pinfunction "~{RESET}_18") (pintype "input"))
      (node (ref "IC23") (pin "9") (pinfunction "VDD_9") (pintype "power_in"))
      (node (ref "IC24") (pin "16") (pinfunction "A1_16") (pintype "input"))
      (node (ref "IC24") (pin "17") (pinfunction "A2_17") (pintype "input"))
      (node (ref "IC24") (pin "18") (pinfunction "~{RESET}_18") (pintype "input"))
      (node (ref "IC24") (pin "9") (pinfunction "VDD_9") (pintype "power_in"))
      (node (ref "IC25") (pin "15") (pinfunction "A0_15") (pintype "input"))
      (node (ref "IC25") (pin "16") (pinfunction "A1_16") (pintype "input"))
      (node (ref "IC25") (pin "17") (pinfunction "A2_17") (pintype "input"))
      (node (ref "IC25") (pin "18") (pinfunction "~{RESET}_18") (pintype "input"))
      (node (ref "IC25") (pin "9") (pinfunction "VDD_9") (pintype "power_in"))
      (node (ref "IC26") (pin "15") (pinfunction "VREF_15") (pintype "input"))
      (node (ref "IC26") (pin "16") (pinfunction "VDD_16") (pintype "power_in"))
      (node (ref "IC3") (pin "15") (pinfunction "VREF_15") (pintype "input"))
      (node (ref "IC3") (pin "16") (pinfunction "VDD_16") (pintype "power_in"))
      (node (ref "IC4") (pin "15") (pinfunction "VREF_15") (pintype "input"))
      (node (ref "IC4") (pin "16") (pinfunction "VDD_16") (pintype "power_in"))
      (node (ref "IC5") (pin "15") (pinfunction "VREF_15") (pintype "input"))
      (node (ref "IC5") (pin "16") (pinfunction "VDD_16") (pintype "power_in"))
      (node (ref "IC6") (pin "15") (pinfunction "VREF_15") (pintype "input"))
      (node (ref "IC6") (pin "16") (pinfunction "VDD_16") (pintype "power_in"))
      (node (ref "IC7") (pin "15") (pinfunction "VREF_15") (pintype "input"))
      (node (ref "IC7") (pin "16") (pinfunction "VDD_16") (pintype "power_in"))
      (node (ref "IC8") (pin "15") (pinfunction "VREF_15") (pintype "input"))
      (node (ref "IC8") (pin "16") (pinfunction "VDD_16") (pintype "power_in"))
      (node (ref "IC9") (pin "15") (pinfunction "VREF_15") (pintype "input"))
      (node (ref "IC9") (pin "16") (pinfunction "VDD_16") (pintype "power_in"))
      (node (ref "JP1") (pin "2") (pinfunction "2_2") (pintype "passive"))
      (node (ref "JP2") (pin "1") (pinfunction "1_1") (pintype "passive"))
      (node (ref "R1") (pin "2") (pinfunction "2_2") (pintype "passive"))
      (node (ref "R7") (pin "1") (pinfunction "1_1") (pintype "passive"))
      (node (ref "U1") (pin "20") (pinfunction "AVCC_20") (pintype "bidirectional"))
      (node (ref "U1") (pin "21") (pinfunction "AREF_21") (pintype "bidirectional"))
      (node (ref "U1") (pin "7") (pinfunction "VCC_7") (pintype "bidirectional"))
    )
    (net (code "351") (name "Net-(IC13A-IREF)") (class "Default")
      (node (ref "IC13") (pin "31") (pinfunction "IREF_31") (pintype "bidirectional"))
      (node (ref "R2") (pin "1") (pinfunction "1_1") (pintype "passive"))
    )
    (net (code "352") (name "Net-(IC13A-SOUT)") (class "Default")
      (node (ref "IC13") (pin "29") (pinfunction "SOUT_29") (pintype "output"))
      (node (ref "IC14") (pin "4") (pinfunction "SIN_4") (pintype "input"))
    )
    (net (code "353") (name "Net-(IC14A-IREF)") (class "Default")
      (node (ref "IC14") (pin "31") (pinfunction "IREF_31") (pintype "bidirectional"))
      (node (ref "R3") (pin "1") (pinfunction "1_1") (pintype "passive"))
    )
    (net (code "354") (name "Net-(IC14A-SOUT)") (class "Default")
      (node (ref "IC14") (pin "29") (pinfunction "SOUT_29") (pintype "output"))
      (node (ref "IC15") (pin "4") (pinfunction "SIN_4") (pintype "input"))
    )
    (net (code "355") (name "Net-(IC15A-IREF)") (class "Default")
      (node (ref "IC15") (pin "31") (pinfunction "IREF_31") (pintype "bidirectional"))
      (node (ref "R4") (pin "1") (pinfunction "1_1") (pintype "passive"))
    )
    (net (code "356") (name "Net-(IC15A-SOUT)") (class "Default")
      (node (ref "IC15") (pin "29") (pinfunction "SOUT_29") (pintype "output"))
      (node (ref "IC16") (pin "4") (pinfunction "SIN_4") (pintype "input"))
    )
    (net (code "357") (name "Net-(IC16A-IREF)") (class "Default")
      (node (ref "IC16") (pin "31") (pinfunction "IREF_31") (pintype "bidirectional"))
      (node (ref "R5") (pin "1") (pinfunction "1_1") (pintype "passive"))
    )
    (net (code "358") (name "Net-(IC16A-SOUT)") (class "Default")
      (node (ref "IC16") (pin "29") (pinfunction "SOUT_29") (pintype "output"))
      (node (ref "IC17") (pin "4") (pinfunction "SIN_4") (pintype "input"))
    )
    (net (code "359") (name "Net-(IC17A-IREF)") (class "Default")
      (node (ref "IC17") (pin "31") (pinfunction "IREF_31") (pintype "bidirectional"))
      (node (ref "R6") (pin "1") (pinfunction "1_1") (pintype "passive"))
    )
    (net (code "360") (name "Net-(U1-PB6(XTAL1{slash}TOSC1))") (class "Default")
      (node (ref "C7") (pin "2") (pinfunction "2_2") (pintype "passive"))
      (node (ref "Q1") (pin "2") (pinfunction "2_2") (pintype "passive"))
      (node (ref "U1") (pin "9") (pinfunction "PB6(XTAL1/TOSC1)_9") (pintype "bidirectional"))
    )
    (net (code "361") (name "Net-(U1-PB7(XTAL2{slash}TOSC2))") (class "Default")
      (node (ref "C8") (pin "2") (pinfunction "2_2") (pintype "passive"))
      (node (ref "Q1") (pin "1") (pinfunction "1_1") (pintype "passive"))
      (node (ref "U1") (pin "10") (pinfunction "PB7(XTAL2/TOSC2)_10") (pintype "bidirectional"))
    )
    (net (code "362") (name "unconnected-(IC17A-OUT8-Pad13)") (class "Default")
      (node (ref "IC17") (pin "13") (pinfunction "OUT8_13") (pintype "open_collector"))
    )
    (net (code "363") (name "unconnected-(IC17A-OUT9-Pad14)") (class "Default")
      (node (ref "IC17") (pin "14") (pinfunction "OUT9_14") (pintype "open_collector"))
    )
    (net (code "364") (name "unconnected-(IC17A-OUT10-Pad15)") (class "Default")
      (node (ref "IC17") (pin "15") (pinfunction "OUT10_15") (pintype "open_collector"))
    )
    (net (code "365") (name "unconnected-(IC17A-OUT11-Pad16)") (class "Default")
      (node (ref "IC17") (pin "16") (pinfunction "OUT11_16") (pintype "open_collector"))
    )
    (net (code "366") (name "unconnected-(IC17A-OUT12-Pad17)") (class "Default")
      (node (ref "IC17") (pin "17") (pinfunction "OUT12_17") (pintype "open_collector"))
    )
    (net (code "367") (name "unconnected-(IC17A-OUT13-Pad18)") (class "Default")
      (node (ref "IC17") (pin "18") (pinfunction "OUT13_18") (pintype "open_collector"))
    )
    (net (code "368") (name "unconnected-(IC17A-OUT14-Pad19)") (class "Default")
      (node (ref "IC17") (pin "19") (pinfunction "OUT14_19") (pintype "open_collector"))
    )
    (net (code "369") (name "unconnected-(IC17A-OUT15-Pad20)") (class "Default")
      (node (ref "IC17") (pin "20") (pinfunction "OUT15_20") (pintype "open_collector"))
    )
    (net (code "370") (name "unconnected-(IC17A-OUT16-Pad21)") (class "Default")
      (node (ref "IC17") (pin "21") (pinfunction "OUT16_21") (pintype "open_collector"))
    )
    (net (code "371") (name "unconnected-(IC17A-OUT17-Pad22)") (class "Default")
      (node (ref "IC17") (pin "22") (pinfunction "OUT17_22") (pintype "open_collector"))
    )
    (net (code "372") (name "unconnected-(IC17A-OUT18-Pad23)") (class "Default")
      (node (ref "IC17") (pin "23") (pinfunction "OUT18_23") (pintype "open_collector"))
    )
    (net (code "373") (name "unconnected-(IC17A-OUT19-Pad24)") (class "Default")
      (node (ref "IC17") (pin "24") (pinfunction "OUT19_24") (pintype "open_collector"))
    )
    (net (code "374") (name "unconnected-(IC17A-OUT20-Pad25)") (class "Default")
      (node (ref "IC17") (pin "25") (pinfunction "OUT20_25") (pintype "open_collector"))
    )
    (net (code "375") (name "unconnected-(IC17A-OUT21-Pad26)") (class "Default")
      (node (ref "IC17") (pin "26") (pinfunction "OUT21_26") (pintype "open_collector"))
    )
    (net (code "376") (name "unconnected-(IC17A-OUT22-Pad27)") (class "Default")
      (node (ref "IC17") (pin "27") (pinfunction "OUT22_27") (pintype "open_collector"))
    )
    (net (code "377") (name "unconnected-(IC17A-OUT23-Pad28)") (class "Default")
      (node (ref "IC17") (pin "28") (pinfunction "OUT23_28") (pintype "open_collector"))
    )
    (net (code "378") (name "unconnected-(IC17A-SOUT-Pad29)") (class "Default")
      (node (ref "IC17") (pin "29") (pinfunction "SOUT_29") (pintype "output"))
    )
    (net (code "379") (name "unconnected-(IC18-GPB5-Pad6)") (class "Default")
      (node (ref "IC18") (pin "6") (pinfunction "GPB5_6") (pintype "bidirectional"))
    )
    (net (code "380") (name "unconnected-(IC18-GPB6-Pad7)") (class "Default")
      (node (ref "IC18") (pin "7") (pinfunction "GPB6_7") (pintype "bidirectional"))
    )
    (net (code "381") (name "unconnected-(IC18-GPB7-Pad8)") (class "Default")
      (node (ref "IC18") (pin "8") (pinfunction "GPB7_8") (pintype "bidirectional"))
    )
    (net (code "382") (name "unconnected-(IC18-INTA-Pad20)") (class "Default")
      (node (ref "IC18") (pin "20") (pinfunction "INTA_20") (pintype "output"))
    )
    (net (code "383") (name "unconnected-(IC18-INTB-Pad19)") (class "Default")
      (node (ref "IC18") (pin "19") (pinfunction "INTB_19") (pintype "output"))
    )
    (net (code "384") (name "unconnected-(IC19-INTB-Pad19)") (class "Default")
      (node (ref "IC19") (pin "19") (pinfunction "INTB_19") (pintype "output"))
    )
    (net (code "385") (name "unconnected-(IC20-INTB-Pad19)") (class "Default")
      (node (ref "IC20") (pin "19") (pinfunction "INTB_19") (pintype "output"))
    )
    (net (code "386") (name "unconnected-(IC21-INTB-Pad19)") (class "Default")
      (node (ref "IC21") (pin "19") (pinfunction "INTB_19") (pintype "output"))
    )
    (net (code "387") (name "unconnected-(IC22-INTB-Pad19)") (class "Default")
      (node (ref "IC22") (pin "19") (pinfunction "INTB_19") (pintype "output"))
    )
    (net (code "388") (name "unconnected-(IC23-INTB-Pad19)") (class "Default")
      (node (ref "IC23") (pin "19") (pinfunction "INTB_19") (pintype "output"))
    )
    (net (code "389") (name "unconnected-(IC24-INTB-Pad19)") (class "Default")
      (node (ref "IC24") (pin "19") (pinfunction "INTB_19") (pintype "output"))
    )
    (net (code "390") (name "unconnected-(IC25-GPB0-Pad1)") (class "Default")
      (node (ref "IC25") (pin "1") (pinfunction "GPB0_1") (pintype "bidirectional"))
    )
    (net (code "391") (name "unconnected-(IC25-GPB1-Pad2)") (class "Default")
      (node (ref "IC25") (pin "2") (pinfunction "GPB1_2") (pintype "bidirectional"))
    )
    (net (code "392") (name "unconnected-(IC25-GPB2-Pad3)") (class "Default")
      (node (ref "IC25") (pin "3") (pinfunction "GPB2_3") (pintype "bidirectional"))
    )
    (net (code "393") (name "unconnected-(IC25-GPB3-Pad4)") (class "Default")
      (node (ref "IC25") (pin "4") (pinfunction "GPB3_4") (pintype "bidirectional"))
    )
    (net (code "394") (name "unconnected-(IC25-GPB4-Pad5)") (class "Default")
      (node (ref "IC25") (pin "5") (pinfunction "GPB4_5") (pintype "bidirectional"))
    )
    (net (code "395") (name "unconnected-(IC25-GPB5-Pad6)") (class "Default")
      (node (ref "IC25") (pin "6") (pinfunction "GPB5_6") (pintype "bidirectional"))
    )
    (net (code "396") (name "unconnected-(IC25-GPB6-Pad7)") (class "Default")
      (node (ref "IC25") (pin "7") (pinfunction "GPB6_7") (pintype "bidirectional"))
    )
    (net (code "397") (name "unconnected-(IC25-GPB7-Pad8)") (class "Default")
      (node (ref "IC25") (pin "8") (pinfunction "GPB7_8") (pintype "bidirectional"))
    )
    (net (code "398") (name "unconnected-(IC25-INTB-Pad19)") (class "Default")
      (node (ref "IC25") (pin "19") (pinfunction "INTB_19") (pintype "output"))
    )
    (net (code "399") (name "unconnected-(ISP-Pad2)") (class "Default")
      (node (ref "ISP") (pin "2") (pinfunction "2_2") (pintype "passive"))
    )
    (net (code "400") (name "unconnected-(JP2-Pad2)") (class "Default")
      (node (ref "JP2") (pin "2") (pinfunction "2_2") (pintype "passive"))
    )
    (net (code "401") (name "unconnected-(JP2-Pad3)") (class "Default")
      (node (ref "JP2") (pin "3") (pinfunction "3_3") (pintype "passive"))
    )
    (net (code "402") (name "unconnected-(JP2-Pad9)") (class "Default")
      (node (ref "JP2") (pin "9") (pinfunction "9_9") (pintype "passive"))
    )
    (net (code "403") (name "unconnected-(JP2-Pad12)") (class "Default")
      (node (ref "JP2") (pin "12") (pinfunction "12_12") (pintype "passive"))
    )
    (net (code "404") (name "unconnected-(JP2-Pad13)") (class "Default")
      (node (ref "JP2") (pin "13") (pinfunction "13_13") (pintype "passive"))
    )
    (net (code "405") (name "unconnected-(JP2-Pad14)") (class "Default")
      (node (ref "JP2") (pin "14") (pinfunction "14_14") (pintype "passive"))
    )
    (net (code "406") (name "unconnected-(JP2-Pad15)") (class "Default")
      (node (ref "JP2") (pin "15") (pinfunction "15_15") (pintype "passive"))
    )
    (net (code "407") (name "unconnected-(JP2-Pad16)") (class "Default")
      (node (ref "JP2") (pin "16") (pinfunction "16_16") (pintype "passive"))
    )
    (net (code "408") (name "unconnected-(JP2-Pad17)") (class "Default")
      (node (ref "JP2") (pin "17") (pinfunction "17_17") (pintype "passive"))
    )
    (net (code "409") (name "unconnected-(JP2-Pad18)") (class "Default")
      (node (ref "JP2") (pin "18") (pinfunction "18_18") (pintype "passive"))
    )
    (net (code "410") (name "unconnected-(JP2-Pad19)") (class "Default")
      (node (ref "JP2") (pin "19") (pinfunction "19_19") (pintype "passive"))
    )
    (net (code "411") (name "unconnected-(U1-PB0(ICP)-Pad14)") (class "Default")
      (node (ref "U1") (pin "14") (pinfunction "PB0(ICP)_14") (pintype "bidirectional"))
    )
    (net (code "412") (name "unconnected-(U1-PB1(OC1A)-Pad15)") (class "Default")
      (node (ref "U1") (pin "15") (pinfunction "PB1(OC1A)_15") (pintype "bidirectional"))
    )
    (net (code "413") (name "unconnected-(U1-PC4(ADC4{slash}SDA)-Pad27)") (class "Default")
      (node (ref "U1") (pin "27") (pinfunction "PC4(ADC4/SDA)_27") (pintype "bidirectional"))
    )
    (net (code "414") (name "unconnected-(U1-PC5(ADC5{slash}SCL)-Pad28)") (class "Default")
      (node (ref "U1") (pin "28") (pinfunction "PC5(ADC5/SCL)_28") (pintype "bidirectional"))
    )
    (net (code "415") (name "unconnected-(U1-PD6(AIN0)-Pad12)") (class "Default")
      (node (ref "U1") (pin "12") (pinfunction "PD6(AIN0)_12") (pintype "bidirectional"))
    )
    (net (code "416") (name "unconnected-(U1-PD7(AIN1)-Pad13)") (class "Default")
      (node (ref "U1") (pin "13") (pinfunction "PD7(AIN1)_13") (pintype "bidirectional"))
    )
  )
)
